# bornhack_stoplicht_ws2812_smd_405_cap_r1.net
KiCad netlist of a schematic drawn in EAGLE
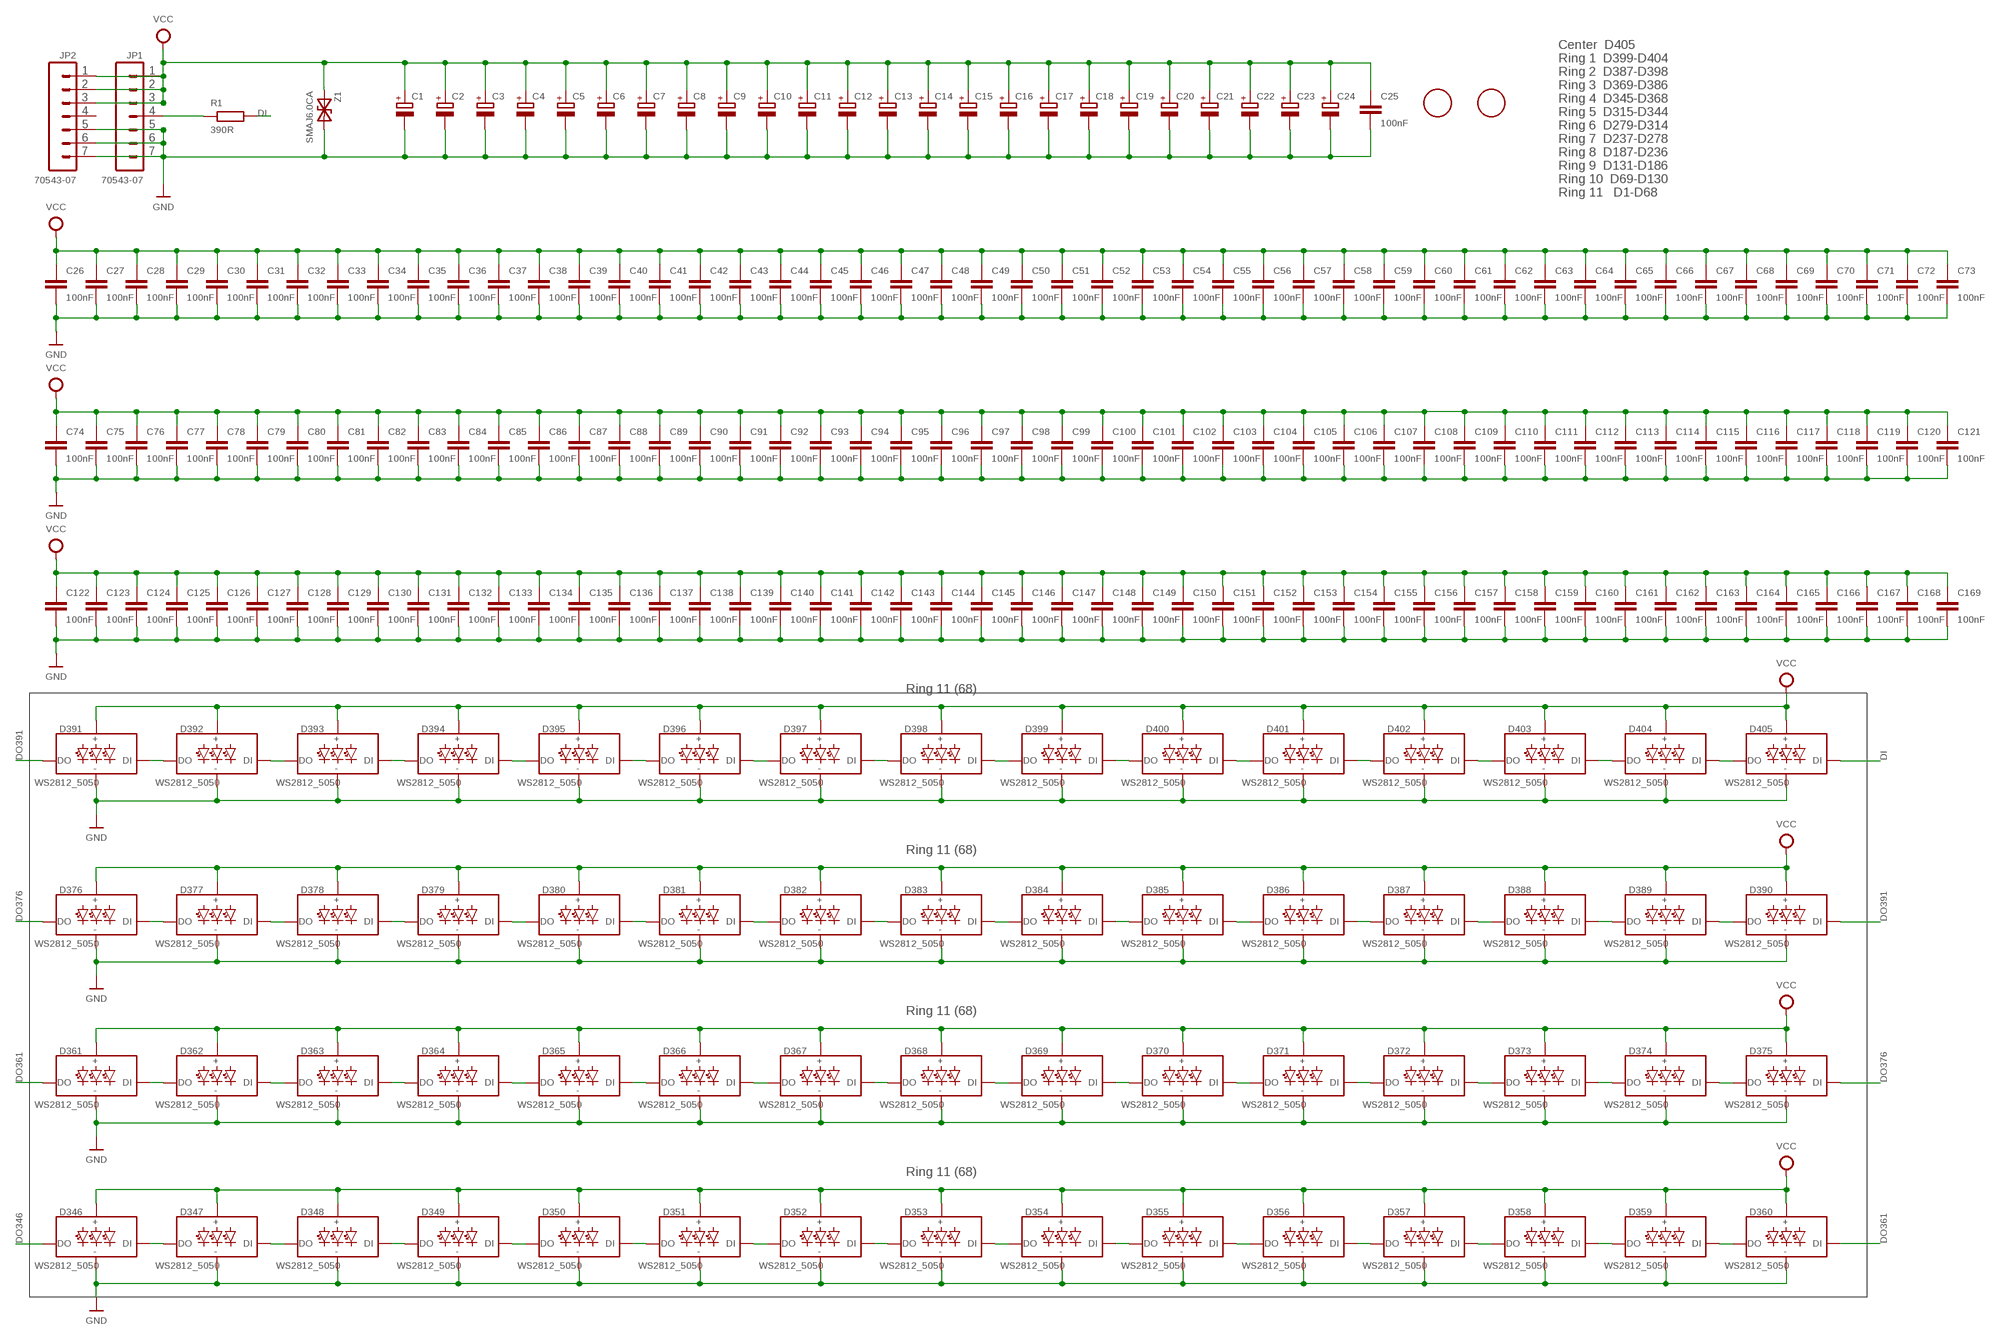
[diagram p0: schematic, sheet 1]
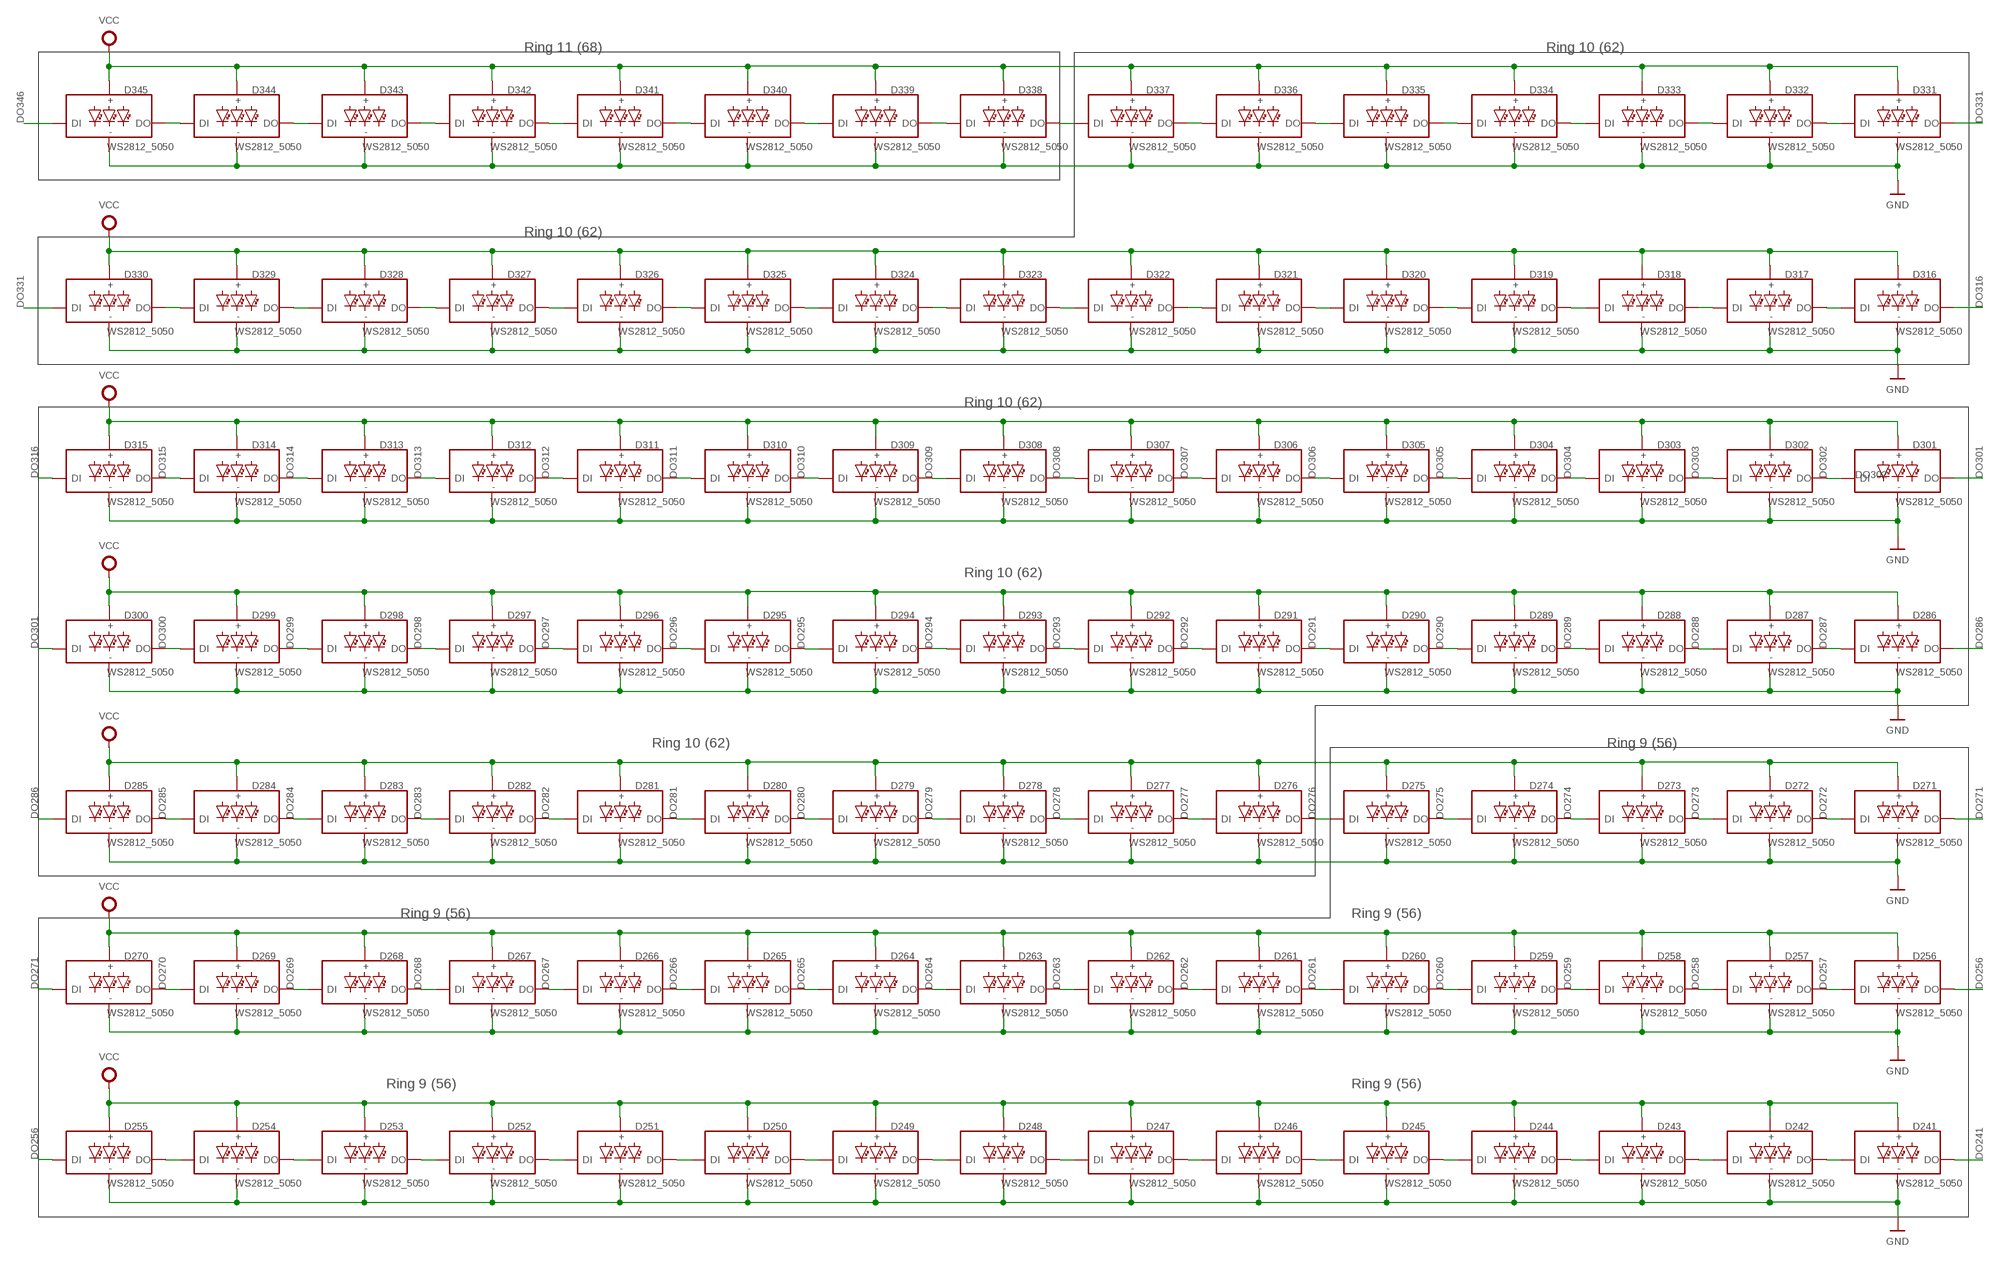
[diagram p1: schematic, sheet 2]
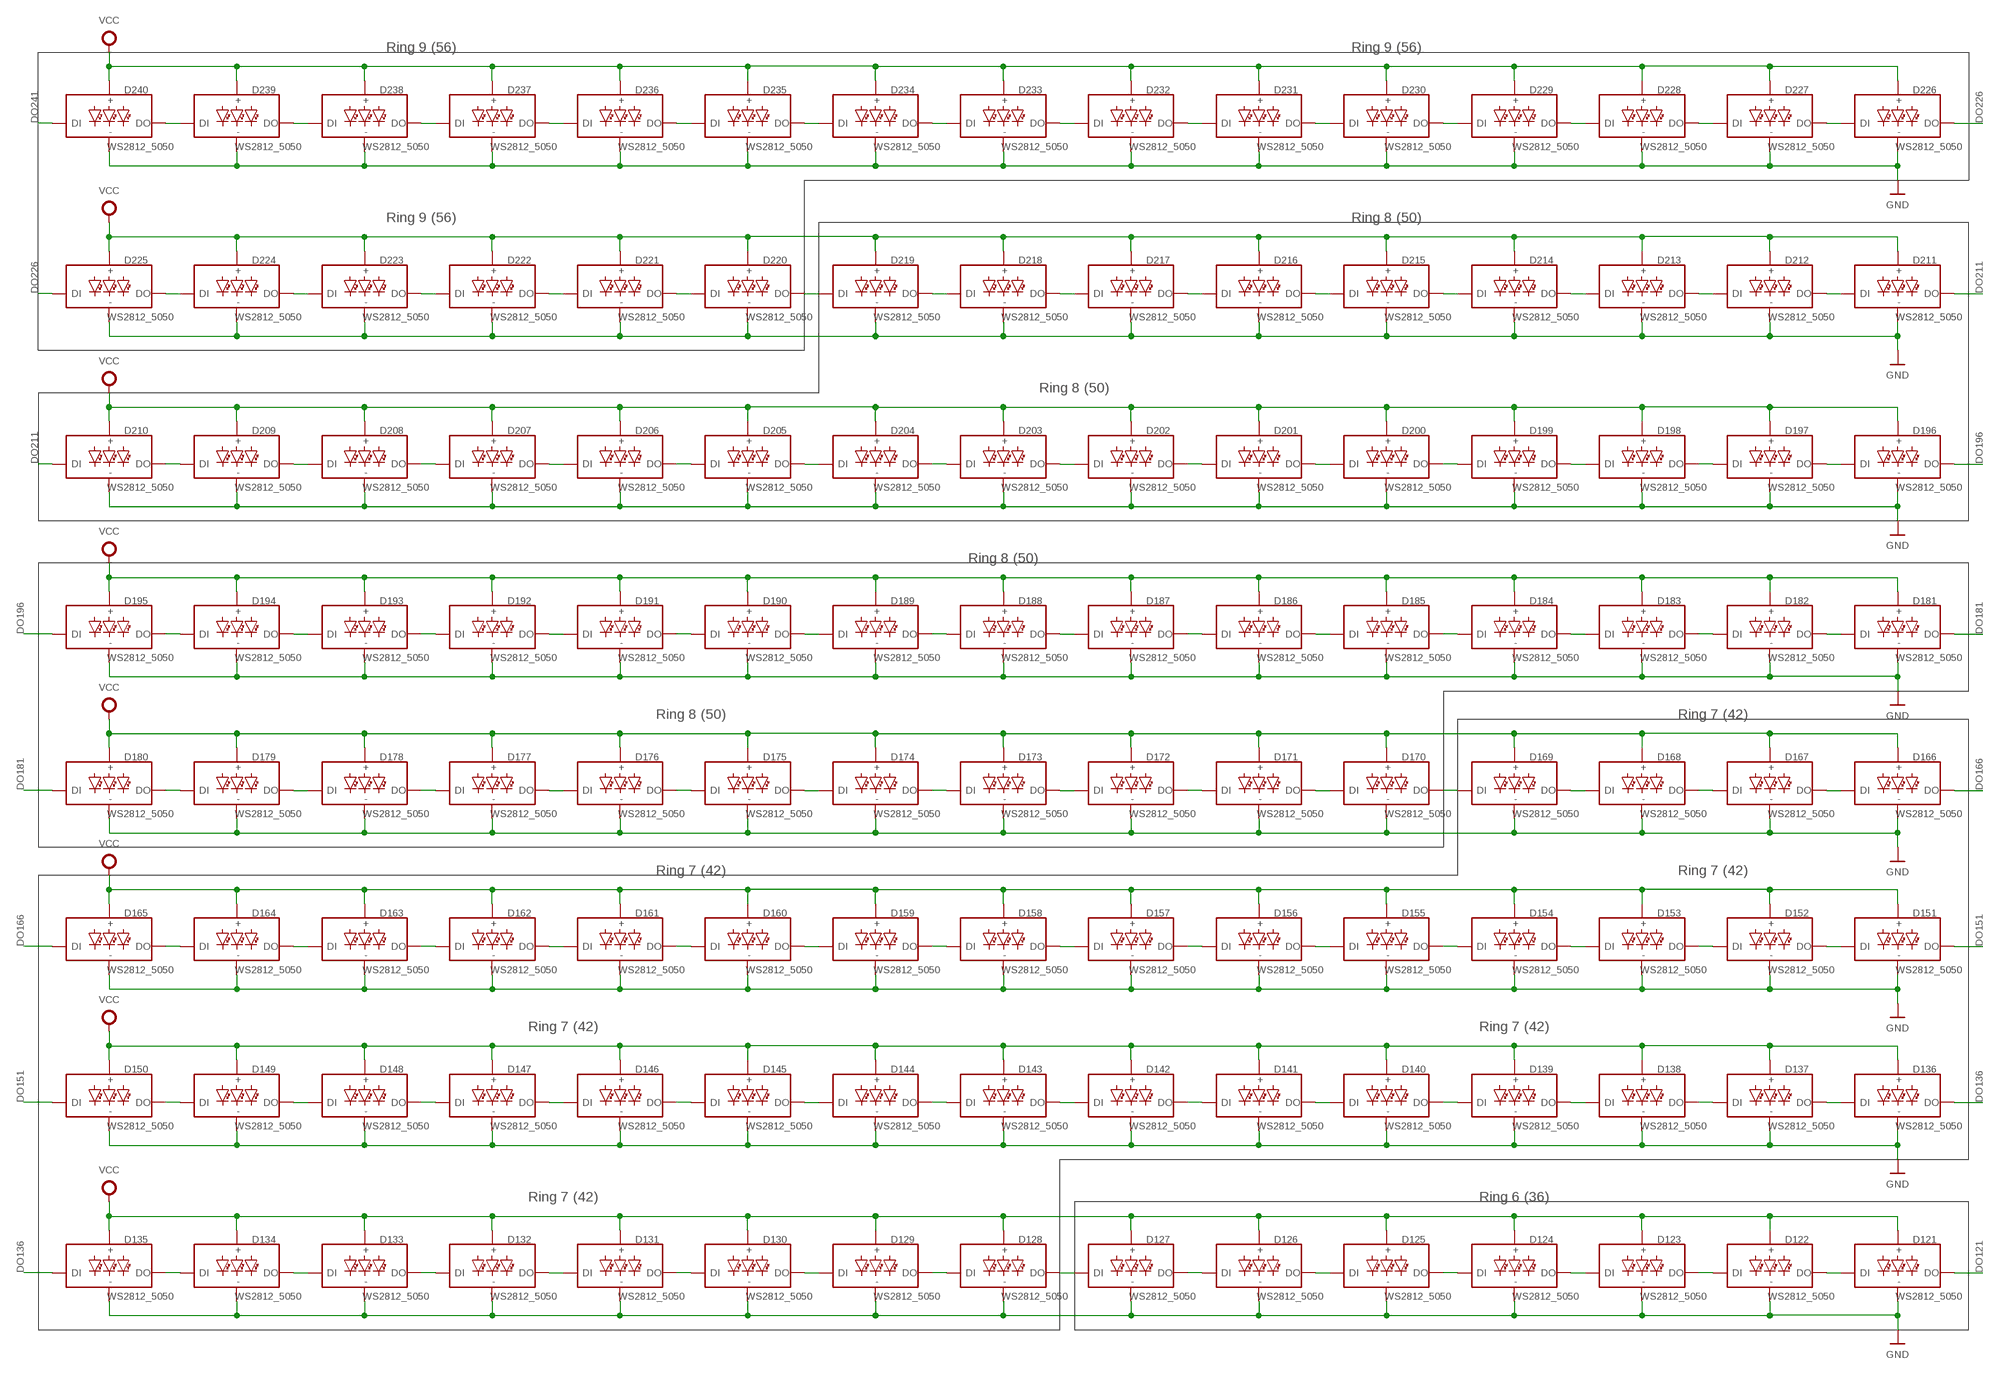
[diagram p2: schematic, sheet 3]
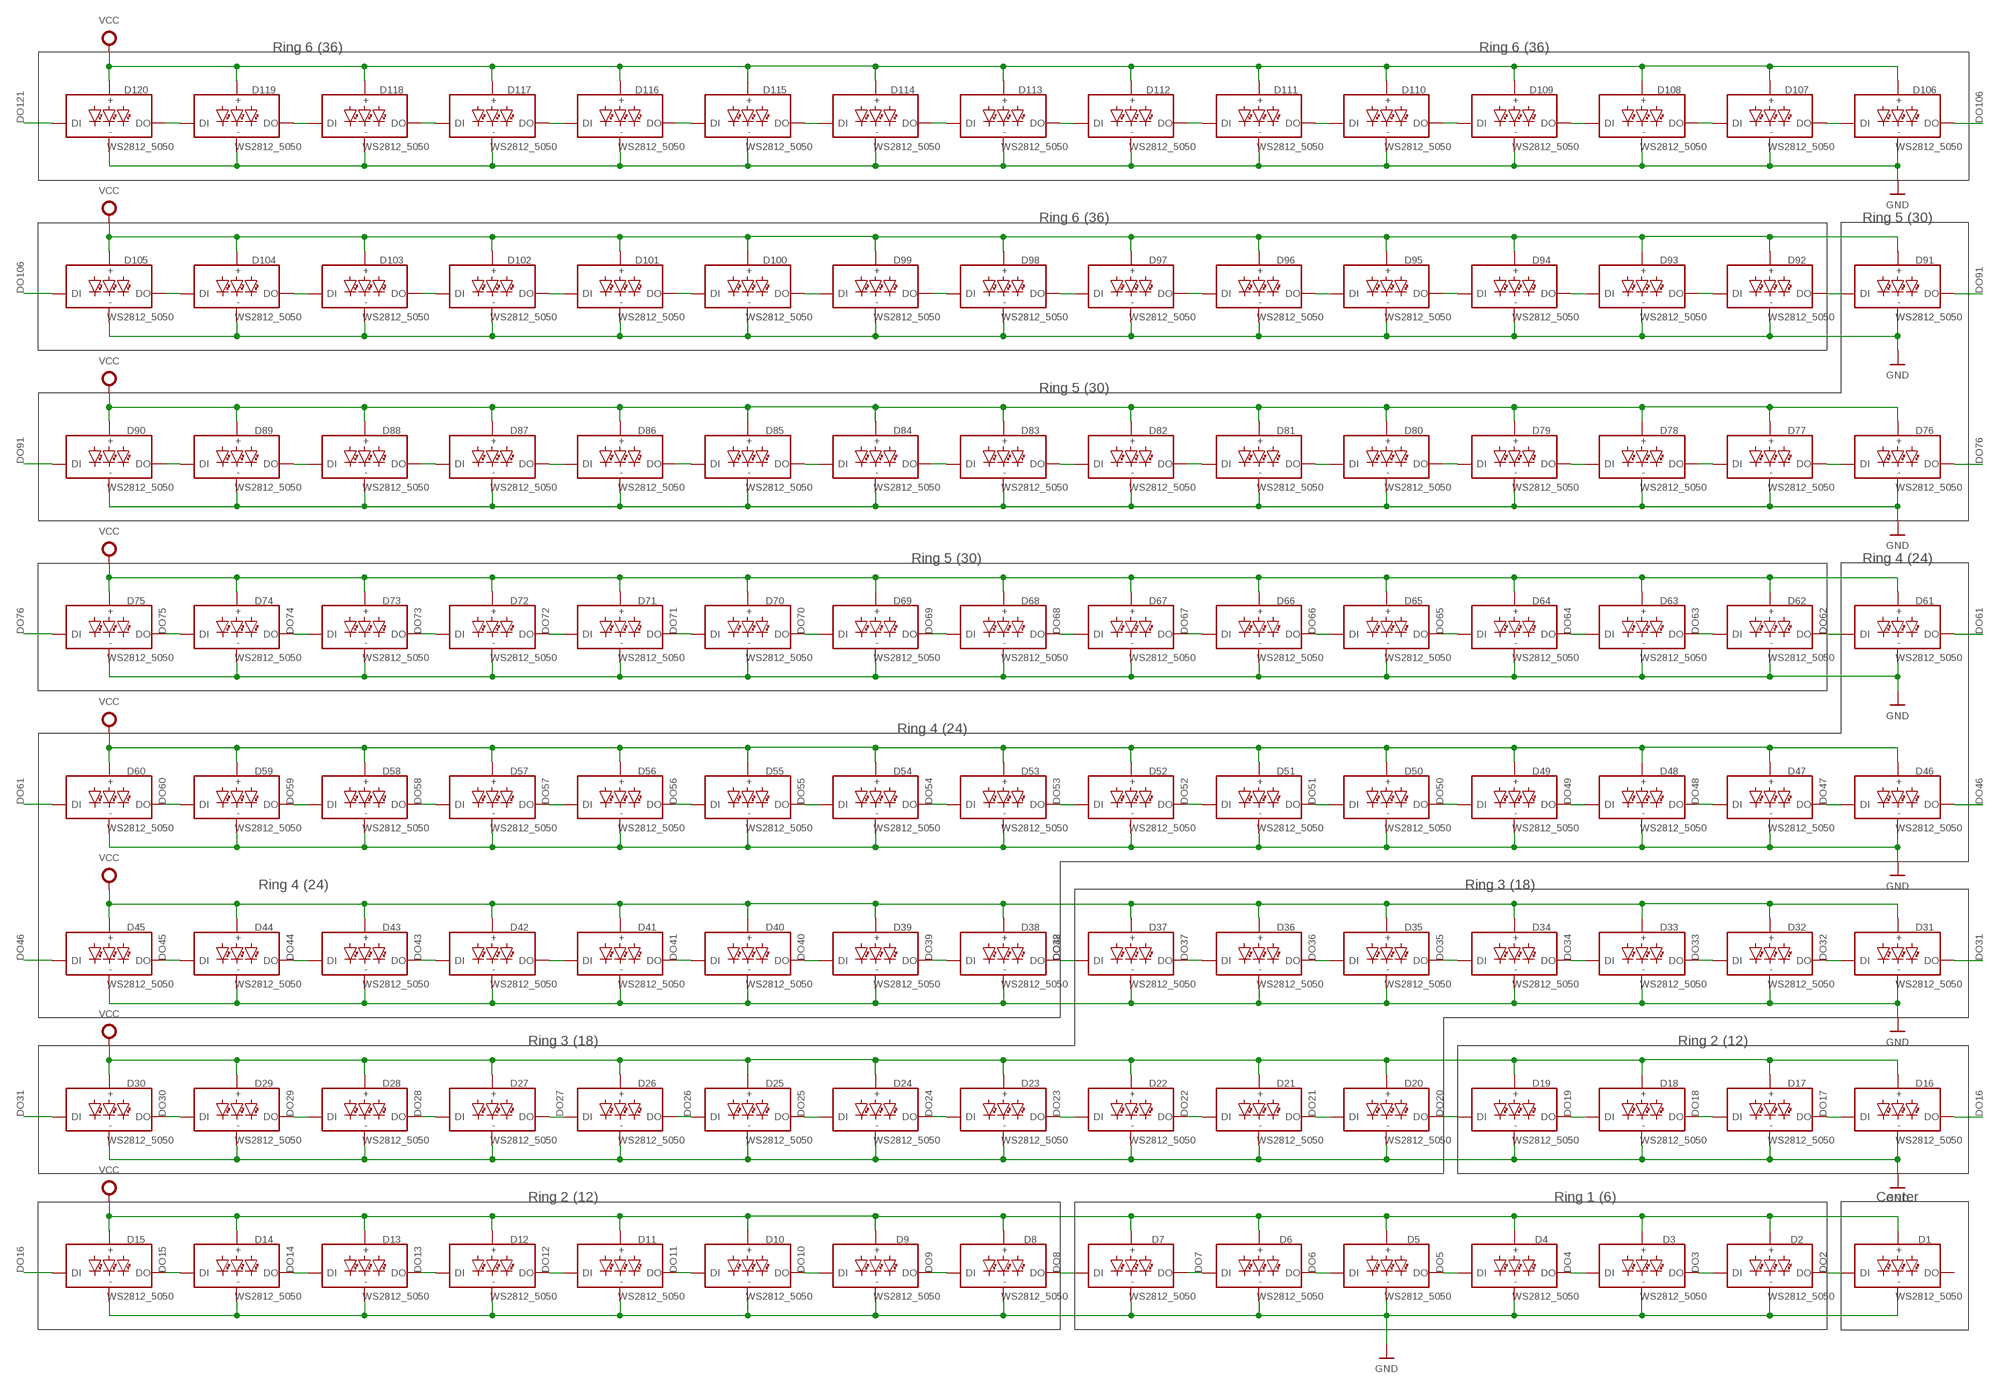
[diagram p3: schematic, sheet 4]

(export (version "E")
  (design (tool "Eeschema 10.0.6"))
  (components
    (comp (ref "D121")
      (value "WS2812_5050")
      (footprint "eagle-import:WS2812-5X5-4PIN")
      (libsource (lib "eagle-import") (part "led-rs_WS2812_5050"))
    )
    (comp (ref "D122")
      (value "WS2812_5050")
      (footprint "eagle-import:WS2812-5X5-4PIN")
      (libsource (lib "eagle-import") (part "led-rs_WS2812_5050"))
    )
    (comp (ref "D123")
      (value "WS2812_5050")
      (footprint "eagle-import:WS2812-5X5-4PIN")
      (libsource (lib "eagle-import") (part "led-rs_WS2812_5050"))
    )
    (comp (ref "D124")
      (value "WS2812_5050")
      (footprint "eagle-import:WS2812-5X5-4PIN")
      (libsource (lib "eagle-import") (part "led-rs_WS2812_5050"))
    )
    (comp (ref "D125")
      (value "WS2812_5050")
      (footprint "eagle-import:WS2812-5X5-4PIN")
      (libsource (lib "eagle-import") (part "led-rs_WS2812_5050"))
    )
    (comp (ref "D126")
      (value "WS2812_5050")
      (footprint "eagle-import:WS2812-5X5-4PIN")
      (libsource (lib "eagle-import") (part "led-rs_WS2812_5050"))
    )
    (comp (ref "D127")
      (value "WS2812_5050")
      (footprint "eagle-import:WS2812-5X5-4PIN")
      (libsource (lib "eagle-import") (part "led-rs_WS2812_5050"))
    )
    (comp (ref "D128")
      (value "WS2812_5050")
      (footprint "eagle-import:WS2812-5X5-4PIN")
      (libsource (lib "eagle-import") (part "led-rs_WS2812_5050"))
    )
    (comp (ref "D129")
      (value "WS2812_5050")
      (footprint "eagle-import:WS2812-5X5-4PIN")
      (libsource (lib "eagle-import") (part "led-rs_WS2812_5050"))
    )
    (comp (ref "D130")
      (value "WS2812_5050")
      (footprint "eagle-import:WS2812-5X5-4PIN")
      (libsource (lib "eagle-import") (part "led-rs_WS2812_5050"))
    )
    (comp (ref "D131")
      (value "WS2812_5050")
      (footprint "eagle-import:WS2812-5X5-4PIN")
      (libsource (lib "eagle-import") (part "led-rs_WS2812_5050"))
    )
    (comp (ref "D132")
      (value "WS2812_5050")
      (footprint "eagle-import:WS2812-5X5-4PIN")
      (libsource (lib "eagle-import") (part "led-rs_WS2812_5050"))
    )
    (comp (ref "D133")
      (value "WS2812_5050")
      (footprint "eagle-import:WS2812-5X5-4PIN")
      (libsource (lib "eagle-import") (part "led-rs_WS2812_5050"))
    )
    (comp (ref "D134")
      (value "WS2812_5050")
      (footprint "eagle-import:WS2812-5X5-4PIN")
      (libsource (lib "eagle-import") (part "led-rs_WS2812_5050"))
    )
    (comp (ref "D135")
      (value "WS2812_5050")
      (footprint "eagle-import:WS2812-5X5-4PIN")
      (libsource (lib "eagle-import") (part "led-rs_WS2812_5050"))
    )
    (comp (ref "D136")
      (value "WS2812_5050")
      (footprint "eagle-import:WS2812-5X5-4PIN")
      (libsource (lib "eagle-import") (part "led-rs_WS2812_5050"))
    )
    (comp (ref "D137")
      (value "WS2812_5050")
      (footprint "eagle-import:WS2812-5X5-4PIN")
      (libsource (lib "eagle-import") (part "led-rs_WS2812_5050"))
    )
    (comp (ref "D138")
      (value "WS2812_5050")
      (footprint "eagle-import:WS2812-5X5-4PIN")
      (libsource (lib "eagle-import") (part "led-rs_WS2812_5050"))
    )
    (comp (ref "D139")
      (value "WS2812_5050")
      (footprint "eagle-import:WS2812-5X5-4PIN")
      (libsource (lib "eagle-import") (part "led-rs_WS2812_5050"))
    )
    (comp (ref "D140")
      (value "WS2812_5050")
      (footprint "eagle-import:WS2812-5X5-4PIN")
      (libsource (lib "eagle-import") (part "led-rs_WS2812_5050"))
    )
    (comp (ref "D141")
      (value "WS2812_5050")
      (footprint "eagle-import:WS2812-5X5-4PIN")
      (libsource (lib "eagle-import") (part "led-rs_WS2812_5050"))
    )
    (comp (ref "D142")
      (value "WS2812_5050")
      (footprint "eagle-import:WS2812-5X5-4PIN")
      (libsource (lib "eagle-import") (part "led-rs_WS2812_5050"))
    )
    (comp (ref "D143")
      (value "WS2812_5050")
      (footprint "eagle-import:WS2812-5X5-4PIN")
      (libsource (lib "eagle-import") (part "led-rs_WS2812_5050"))
    )
    (comp (ref "D144")
      (value "WS2812_5050")
      (footprint "eagle-import:WS2812-5X5-4PIN")
      (libsource (lib "eagle-import") (part "led-rs_WS2812_5050"))
    )
    (comp (ref "D145")
      (value "WS2812_5050")
      (footprint "eagle-import:WS2812-5X5-4PIN")
      (libsource (lib "eagle-import") (part "led-rs_WS2812_5050"))
    )
    (comp (ref "D146")
      (value "WS2812_5050")
      (footprint "eagle-import:WS2812-5X5-4PIN")
      (libsource (lib "eagle-import") (part "led-rs_WS2812_5050"))
    )
    (comp (ref "D147")
      (value "WS2812_5050")
      (footprint "eagle-import:WS2812-5X5-4PIN")
      (libsource (lib "eagle-import") (part "led-rs_WS2812_5050"))
    )
    (comp (ref "D148")
      (value "WS2812_5050")
      (footprint "eagle-import:WS2812-5X5-4PIN")
      (libsource (lib "eagle-import") (part "led-rs_WS2812_5050"))
    )
    (comp (ref "D149")
      (value "WS2812_5050")
      (footprint "eagle-import:WS2812-5X5-4PIN")
      (libsource (lib "eagle-import") (part "led-rs_WS2812_5050"))
    )
    (comp (ref "D150")
      (value "WS2812_5050")
      (footprint "eagle-import:WS2812-5X5-4PIN")
      (libsource (lib "eagle-import") (part "led-rs_WS2812_5050"))
    )
    (comp (ref "D151")
      (value "WS2812_5050")
      (footprint "eagle-import:WS2812-5X5-4PIN")
      (libsource (lib "eagle-import") (part "led-rs_WS2812_5050"))
    )
    (comp (ref "D152")
      (value "WS2812_5050")
      (footprint "eagle-import:WS2812-5X5-4PIN")
      (libsource (lib "eagle-import") (part "led-rs_WS2812_5050"))
    )
    (comp (ref "D153")
      (value "WS2812_5050")
      (footprint "eagle-import:WS2812-5X5-4PIN")
      (libsource (lib "eagle-import") (part "led-rs_WS2812_5050"))
    )
    (comp (ref "D154")
      (value "WS2812_5050")
      (footprint "eagle-import:WS2812-5X5-4PIN")
      (libsource (lib "eagle-import") (part "led-rs_WS2812_5050"))
    )
    (comp (ref "D155")
      (value "WS2812_5050")
      (footprint "eagle-import:WS2812-5X5-4PIN")
      (libsource (lib "eagle-import") (part "led-rs_WS2812_5050"))
    )
    (comp (ref "D156")
      (value "WS2812_5050")
      (footprint "eagle-import:WS2812-5X5-4PIN")
      (libsource (lib "eagle-import") (part "led-rs_WS2812_5050"))
    )
    (comp (ref "D157")
      (value "WS2812_5050")
      (footprint "eagle-import:WS2812-5X5-4PIN")
      (libsource (lib "eagle-import") (part "led-rs_WS2812_5050"))
    )
    (comp (ref "D158")
      (value "WS2812_5050")
      (footprint "eagle-import:WS2812-5X5-4PIN")
      (libsource (lib "eagle-import") (part "led-rs_WS2812_5050"))
    )
    (comp (ref "D159")
      (value "WS2812_5050")
      (footprint "eagle-import:WS2812-5X5-4PIN")
      (libsource (lib "eagle-import") (part "led-rs_WS2812_5050"))
    )
    (comp (ref "D160")
      (value "WS2812_5050")
      (footprint "eagle-import:WS2812-5X5-4PIN")
      (libsource (lib "eagle-import") (part "led-rs_WS2812_5050"))
    )
    (comp (ref "D161")
      (value "WS2812_5050")
      (footprint "eagle-import:WS2812-5X5-4PIN")
      (libsource (lib "eagle-import") (part "led-rs_WS2812_5050"))
    )
    (comp (ref "D162")
      (value "WS2812_5050")
      (footprint "eagle-import:WS2812-5X5-4PIN")
      (libsource (lib "eagle-import") (part "led-rs_WS2812_5050"))
    )
    (comp (ref "D163")
      (value "WS2812_5050")
      (footprint "eagle-import:WS2812-5X5-4PIN")
      (libsource (lib "eagle-import") (part "led-rs_WS2812_5050"))
    )
    (comp (ref "D164")
      (value "WS2812_5050")
      (footprint "eagle-import:WS2812-5X5-4PIN")
      (libsource (lib "eagle-import") (part "led-rs_WS2812_5050"))
    )
    (comp (ref "D165")
      (value "WS2812_5050")
      (footprint "eagle-import:WS2812-5X5-4PIN")
      (libsource (lib "eagle-import") (part "led-rs_WS2812_5050"))
    )
    (comp (ref "D166")
      (value "WS2812_5050")
      (footprint "eagle-import:WS2812-5X5-4PIN")
      (libsource (lib "eagle-import") (part "led-rs_WS2812_5050"))
    )
    (comp (ref "D167")
      (value "WS2812_5050")
      (footprint "eagle-import:WS2812-5X5-4PIN")
      (libsource (lib "eagle-import") (part "led-rs_WS2812_5050"))
    )
    (comp (ref "D168")
      (value "WS2812_5050")
      (footprint "eagle-import:WS2812-5X5-4PIN")
      (libsource (lib "eagle-import") (part "led-rs_WS2812_5050"))
    )
    (comp (ref "D169")
      (value "WS2812_5050")
      (footprint "eagle-import:WS2812-5X5-4PIN")
      (libsource (lib "eagle-import") (part "led-rs_WS2812_5050"))
    )
    (comp (ref "D170")
      (value "WS2812_5050")
      (footprint "eagle-import:WS2812-5X5-4PIN")
      (libsource (lib "eagle-import") (part "led-rs_WS2812_5050"))
    )
    (comp (ref "D171")
      (value "WS2812_5050")
      (footprint "eagle-import:WS2812-5X5-4PIN")
      (libsource (lib "eagle-import") (part "led-rs_WS2812_5050"))
    )
    (comp (ref "D172")
      (value "WS2812_5050")
      (footprint "eagle-import:WS2812-5X5-4PIN")
      (libsource (lib "eagle-import") (part "led-rs_WS2812_5050"))
    )
    (comp (ref "D173")
      (value "WS2812_5050")
      (footprint "eagle-import:WS2812-5X5-4PIN")
      (libsource (lib "eagle-import") (part "led-rs_WS2812_5050"))
    )
    (comp (ref "D174")
      (value "WS2812_5050")
      (footprint "eagle-import:WS2812-5X5-4PIN")
      (libsource (lib "eagle-import") (part "led-rs_WS2812_5050"))
    )
    (comp (ref "D175")
      (value "WS2812_5050")
      (footprint "eagle-import:WS2812-5X5-4PIN")
      (libsource (lib "eagle-import") (part "led-rs_WS2812_5050"))
    )
    (comp (ref "D176")
      (value "WS2812_5050")
      (footprint "eagle-import:WS2812-5X5-4PIN")
      (libsource (lib "eagle-import") (part "led-rs_WS2812_5050"))
    )
    (comp (ref "D177")
      (value "WS2812_5050")
      (footprint "eagle-import:WS2812-5X5-4PIN")
      (libsource (lib "eagle-import") (part "led-rs_WS2812_5050"))
    )
    (comp (ref "D178")
      (value "WS2812_5050")
      (footprint "eagle-import:WS2812-5X5-4PIN")
      (libsource (lib "eagle-import") (part "led-rs_WS2812_5050"))
    )
    (comp (ref "D179")
      (value "WS2812_5050")
      (footprint "eagle-import:WS2812-5X5-4PIN")
      (libsource (lib "eagle-import") (part "led-rs_WS2812_5050"))
    )
    (comp (ref "D180")
      (value "WS2812_5050")
      (footprint "eagle-import:WS2812-5X5-4PIN")
      (libsource (lib "eagle-import") (part "led-rs_WS2812_5050"))
    )
    (comp (ref "D181")
      (value "WS2812_5050")
      (footprint "eagle-import:WS2812-5X5-4PIN")
      (libsource (lib "eagle-import") (part "led-rs_WS2812_5050"))
    )
    (comp (ref "D182")
      (value "WS2812_5050")
      (footprint "eagle-import:WS2812-5X5-4PIN")
      (libsource (lib "eagle-import") (part "led-rs_WS2812_5050"))
    )
    (comp (ref "D183")
      (value "WS2812_5050")
      (footprint "eagle-import:WS2812-5X5-4PIN")
      (libsource (lib "eagle-import") (part "led-rs_WS2812_5050"))
    )
    (comp (ref "D184")
      (value "WS2812_5050")
      (footprint "eagle-import:WS2812-5X5-4PIN")
      (libsource (lib "eagle-import") (part "led-rs_WS2812_5050"))
    )
    (comp (ref "D185")
      (value "WS2812_5050")
      (footprint "eagle-import:WS2812-5X5-4PIN")
      (libsource (lib "eagle-import") (part "led-rs_WS2812_5050"))
    )
    (comp (ref "D186")
      (value "WS2812_5050")
      (footprint "eagle-import:WS2812-5X5-4PIN")
      (libsource (lib "eagle-import") (part "led-rs_WS2812_5050"))
    )
    (comp (ref "D187")
      (value "WS2812_5050")
      (footprint "eagle-import:WS2812-5X5-4PIN")
      (libsource (lib "eagle-import") (part "led-rs_WS2812_5050"))
    )
    (comp (ref "D188")
      (value "WS2812_5050")
      (footprint "eagle-import:WS2812-5X5-4PIN")
      (libsource (lib "eagle-import") (part "led-rs_WS2812_5050"))
    )
    (comp (ref "D189")
      (value "WS2812_5050")
      (footprint "eagle-import:WS2812-5X5-4PIN")
      (libsource (lib "eagle-import") (part "led-rs_WS2812_5050"))
    )
    (comp (ref "D190")
      (value "WS2812_5050")
      (footprint "eagle-import:WS2812-5X5-4PIN")
      (libsource (lib "eagle-import") (part "led-rs_WS2812_5050"))
    )
    (comp (ref "D191")
      (value "WS2812_5050")
      (footprint "eagle-import:WS2812-5X5-4PIN")
      (libsource (lib "eagle-import") (part "led-rs_WS2812_5050"))
    )
    (comp (ref "D192")
      (value "WS2812_5050")
      (footprint "eagle-import:WS2812-5X5-4PIN")
      (libsource (lib "eagle-import") (part "led-rs_WS2812_5050"))
    )
    (comp (ref "D193")
      (value "WS2812_5050")
      (footprint "eagle-import:WS2812-5X5-4PIN")
      (libsource (lib "eagle-import") (part "led-rs_WS2812_5050"))
    )
    (comp (ref "D194")
      (value "WS2812_5050")
      (footprint "eagle-import:WS2812-5X5-4PIN")
      (libsource (lib "eagle-import") (part "led-rs_WS2812_5050"))
    )
    (comp (ref "D195")
      (value "WS2812_5050")
      (footprint "eagle-import:WS2812-5X5-4PIN")
      (libsource (lib "eagle-import") (part "led-rs_WS2812_5050"))
    )
    (comp (ref "D196")
      (value "WS2812_5050")
      (footprint "eagle-import:WS2812-5X5-4PIN")
      (libsource (lib "eagle-import") (part "led-rs_WS2812_5050"))
    )
    (comp (ref "D197")
      (value "WS2812_5050")
      (footprint "eagle-import:WS2812-5X5-4PIN")
      (libsource (lib "eagle-import") (part "led-rs_WS2812_5050"))
    )
    (comp (ref "D198")
      (value "WS2812_5050")
      (footprint "eagle-import:WS2812-5X5-4PIN")
      (libsource (lib "eagle-import") (part "led-rs_WS2812_5050"))
    )
    (comp (ref "D199")
      (value "WS2812_5050")
      (footprint "eagle-import:WS2812-5X5-4PIN")
      (libsource (lib "eagle-import") (part "led-rs_WS2812_5050"))
    )
    (comp (ref "D200")
      (value "WS2812_5050")
      (footprint "eagle-import:WS2812-5X5-4PIN")
      (libsource (lib "eagle-import") (part "led-rs_WS2812_5050"))
    )
    (comp (ref "D201")
      (value "WS2812_5050")
      (footprint "eagle-import:WS2812-5X5-4PIN")
      (libsource (lib "eagle-import") (part "led-rs_WS2812_5050"))
    )
    (comp (ref "D202")
      (value "WS2812_5050")
      (footprint "eagle-import:WS2812-5X5-4PIN")
      (libsource (lib "eagle-import") (part "led-rs_WS2812_5050"))
    )
    (comp (ref "D203")
      (value "WS2812_5050")
      (footprint "eagle-import:WS2812-5X5-4PIN")
      (libsource (lib "eagle-import") (part "led-rs_WS2812_5050"))
    )
    (comp (ref "D204")
      (value "WS2812_5050")
      (footprint "eagle-import:WS2812-5X5-4PIN")
      (libsource (lib "eagle-import") (part "led-rs_WS2812_5050"))
    )
    (comp (ref "D205")
      (value "WS2812_5050")
      (footprint "eagle-import:WS2812-5X5-4PIN")
      (libsource (lib "eagle-import") (part "led-rs_WS2812_5050"))
    )
    (comp (ref "D206")
      (value "WS2812_5050")
      (footprint "eagle-import:WS2812-5X5-4PIN")
      (libsource (lib "eagle-import") (part "led-rs_WS2812_5050"))
    )
    (comp (ref "D207")
      (value "WS2812_5050")
      (footprint "eagle-import:WS2812-5X5-4PIN")
      (libsource (lib "eagle-import") (part "led-rs_WS2812_5050"))
    )
    (comp (ref "D208")
      (value "WS2812_5050")
      (footprint "eagle-import:WS2812-5X5-4PIN")
      (libsource (lib "eagle-import") (part "led-rs_WS2812_5050"))
    )
    (comp (ref "D209")
      (value "WS2812_5050")
      (footprint "eagle-import:WS2812-5X5-4PIN")
      (libsource (lib "eagle-import") (part "led-rs_WS2812_5050"))
    )
    (comp (ref "D210")
      (value "WS2812_5050")
      (footprint "eagle-import:WS2812-5X5-4PIN")
      (libsource (lib "eagle-import") (part "led-rs_WS2812_5050"))
    )
    (comp (ref "D211")
      (value "WS2812_5050")
      (footprint "eagle-import:WS2812-5X5-4PIN")
      (libsource (lib "eagle-import") (part "led-rs_WS2812_5050"))
    )
    (comp (ref "D212")
      (value "WS2812_5050")
      (footprint "eagle-import:WS2812-5X5-4PIN")
      (libsource (lib "eagle-import") (part "led-rs_WS2812_5050"))
    )
    (comp (ref "D213")
      (value "WS2812_5050")
      (footprint "eagle-import:WS2812-5X5-4PIN")
      (libsource (lib "eagle-import") (part "led-rs_WS2812_5050"))
    )
    (comp (ref "D214")
      (value "WS2812_5050")
      (footprint "eagle-import:WS2812-5X5-4PIN")
      (libsource (lib "eagle-import") (part "led-rs_WS2812_5050"))
    )
    (comp (ref "D215")
      (value "WS2812_5050")
      (footprint "eagle-import:WS2812-5X5-4PIN")
      (libsource (lib "eagle-import") (part "led-rs_WS2812_5050"))
    )
    (comp (ref "D216")
      (value "WS2812_5050")
      (footprint "eagle-import:WS2812-5X5-4PIN")
      (libsource (lib "eagle-import") (part "led-rs_WS2812_5050"))
    )
    (comp (ref "D217")
      (value "WS2812_5050")
      (footprint "eagle-import:WS2812-5X5-4PIN")
      (libsource (lib "eagle-import") (part "led-rs_WS2812_5050"))
    )
    (comp (ref "D218")
      (value "WS2812_5050")
      (footprint "eagle-import:WS2812-5X5-4PIN")
      (libsource (lib "eagle-import") (part "led-rs_WS2812_5050"))
    )
    (comp (ref "D219")
      (value "WS2812_5050")
      (footprint "eagle-import:WS2812-5X5-4PIN")
      (libsource (lib "eagle-import") (part "led-rs_WS2812_5050"))
    )
    (comp (ref "D220")
      (value "WS2812_5050")
      (footprint "eagle-import:WS2812-5X5-4PIN")
      (libsource (lib "eagle-import") (part "led-rs_WS2812_5050"))
    )
    (comp (ref "D221")
      (value "WS2812_5050")
      (footprint "eagle-import:WS2812-5X5-4PIN")
      (libsource (lib "eagle-import") (part "led-rs_WS2812_5050"))
    )
    (comp (ref "D222")
      (value "WS2812_5050")
      (footprint "eagle-import:WS2812-5X5-4PIN")
      (libsource (lib "eagle-import") (part "led-rs_WS2812_5050"))
    )
    (comp (ref "D223")
      (value "WS2812_5050")
      (footprint "eagle-import:WS2812-5X5-4PIN")
      (libsource (lib "eagle-import") (part "led-rs_WS2812_5050"))
    )
    (comp (ref "D224")
      (value "WS2812_5050")
      (footprint "eagle-import:WS2812-5X5-4PIN")
      (libsource (lib "eagle-import") (part "led-rs_WS2812_5050"))
    )
    (comp (ref "D225")
      (value "WS2812_5050")
      (footprint "eagle-import:WS2812-5X5-4PIN")
      (libsource (lib "eagle-import") (part "led-rs_WS2812_5050"))
    )
    (comp (ref "D226")
      (value "WS2812_5050")
      (footprint "eagle-import:WS2812-5X5-4PIN")
      (libsource (lib "eagle-import") (part "led-rs_WS2812_5050"))
    )
    (comp (ref "D227")
      (value "WS2812_5050")
      (footprint "eagle-import:WS2812-5X5-4PIN")
      (libsource (lib "eagle-import") (part "led-rs_WS2812_5050"))
    )
    (comp (ref "D228")
      (value "WS2812_5050")
      (footprint "eagle-import:WS2812-5X5-4PIN")
      (libsource (lib "eagle-import") (part "led-rs_WS2812_5050"))
    )
    (comp (ref "D229")
      (value "WS2812_5050")
      (footprint "eagle-import:WS2812-5X5-4PIN")
      (libsource (lib "eagle-import") (part "led-rs_WS2812_5050"))
    )
    (comp (ref "D230")
      (value "WS2812_5050")
      (footprint "eagle-import:WS2812-5X5-4PIN")
      (libsource (lib "eagle-import") (part "led-rs_WS2812_5050"))
    )
    (comp (ref "D231")
      (value "WS2812_5050")
      (footprint "eagle-import:WS2812-5X5-4PIN")
      (libsource (lib "eagle-import") (part "led-rs_WS2812_5050"))
    )
    (comp (ref "D232")
      (value "WS2812_5050")
      (footprint "eagle-import:WS2812-5X5-4PIN")
      (libsource (lib "eagle-import") (part "led-rs_WS2812_5050"))
    )
    (comp (ref "D233")
      (value "WS2812_5050")
      (footprint "eagle-import:WS2812-5X5-4PIN")
      (libsource (lib "eagle-import") (part "led-rs_WS2812_5050"))
    )
    (comp (ref "D234")
      (value "WS2812_5050")
      (footprint "eagle-import:WS2812-5X5-4PIN")
      (libsource (lib "eagle-import") (part "led-rs_WS2812_5050"))
    )
    (comp (ref "D235")
      (value "WS2812_5050")
      (footprint "eagle-import:WS2812-5X5-4PIN")
      (libsource (lib "eagle-import") (part "led-rs_WS2812_5050"))
    )
    (comp (ref "D236")
      (value "WS2812_5050")
      (footprint "eagle-import:WS2812-5X5-4PIN")
      (libsource (lib "eagle-import") (part "led-rs_WS2812_5050"))
    )
    (comp (ref "D237")
      (value "WS2812_5050")
      (footprint "eagle-import:WS2812-5X5-4PIN")
      (libsource (lib "eagle-import") (part "led-rs_WS2812_5050"))
    )
    (comp (ref "D238")
      (value "WS2812_5050")
      (footprint "eagle-import:WS2812-5X5-4PIN")
      (libsource (lib "eagle-import") (part "led-rs_WS2812_5050"))
    )
    (comp (ref "D239")
      (value "WS2812_5050")
      (footprint "eagle-import:WS2812-5X5-4PIN")
      (libsource (lib "eagle-import") (part "led-rs_WS2812_5050"))
    )
    (comp (ref "D240")
      (value "WS2812_5050")
      (footprint "eagle-import:WS2812-5X5-4PIN")
      (libsource (lib "eagle-import") (part "led-rs_WS2812_5050"))
    )
    (comp (ref "D241")
      (value "WS2812_5050")
      (footprint "eagle-import:WS2812-5X5-4PIN")
      (libsource (lib "eagle-import") (part "led-rs_WS2812_5050"))
    )
    (comp (ref "D242")
      (value "WS2812_5050")
      (footprint "eagle-import:WS2812-5X5-4PIN")
      (libsource (lib "eagle-import") (part "led-rs_WS2812_5050"))
    )
    (comp (ref "D243")
      (value "WS2812_5050")
      (footprint "eagle-import:WS2812-5X5-4PIN")
      (libsource (lib "eagle-import") (part "led-rs_WS2812_5050"))
    )
    (comp (ref "D244")
      (value "WS2812_5050")
      (footprint "eagle-import:WS2812-5X5-4PIN")
      (libsource (lib "eagle-import") (part "led-rs_WS2812_5050"))
    )
    (comp (ref "D245")
      (value "WS2812_5050")
      (footprint "eagle-import:WS2812-5X5-4PIN")
      (libsource (lib "eagle-import") (part "led-rs_WS2812_5050"))
    )
    (comp (ref "D246")
      (value "WS2812_5050")
      (footprint "eagle-import:WS2812-5X5-4PIN")
      (libsource (lib "eagle-import") (part "led-rs_WS2812_5050"))
    )
    (comp (ref "D247")
      (value "WS2812_5050")
      (footprint "eagle-import:WS2812-5X5-4PIN")
      (libsource (lib "eagle-import") (part "led-rs_WS2812_5050"))
    )
    (comp (ref "D248")
      (value "WS2812_5050")
      (footprint "eagle-import:WS2812-5X5-4PIN")
      (libsource (lib "eagle-import") (part "led-rs_WS2812_5050"))
    )
    (comp (ref "D249")
      (value "WS2812_5050")
      (footprint "eagle-import:WS2812-5X5-4PIN")
      (libsource (lib "eagle-import") (part "led-rs_WS2812_5050"))
    )
    (comp (ref "D250")
      (value "WS2812_5050")
      (footprint "eagle-import:WS2812-5X5-4PIN")
      (libsource (lib "eagle-import") (part "led-rs_WS2812_5050"))
    )
    (comp (ref "D251")
      (value "WS2812_5050")
      (footprint "eagle-import:WS2812-5X5-4PIN")
      (libsource (lib "eagle-import") (part "led-rs_WS2812_5050"))
    )
    (comp (ref "D252")
      (value "WS2812_5050")
      (footprint "eagle-import:WS2812-5X5-4PIN")
      (libsource (lib "eagle-import") (part "led-rs_WS2812_5050"))
    )
    (comp (ref "D253")
      (value "WS2812_5050")
      (footprint "eagle-import:WS2812-5X5-4PIN")
      (libsource (lib "eagle-import") (part "led-rs_WS2812_5050"))
    )
    (comp (ref "D254")
      (value "WS2812_5050")
      (footprint "eagle-import:WS2812-5X5-4PIN")
      (libsource (lib "eagle-import") (part "led-rs_WS2812_5050"))
    )
    (comp (ref "D255")
      (value "WS2812_5050")
      (footprint "eagle-import:WS2812-5X5-4PIN")
      (libsource (lib "eagle-import") (part "led-rs_WS2812_5050"))
    )
    (comp (ref "D256")
      (value "WS2812_5050")
      (footprint "eagle-import:WS2812-5X5-4PIN")
      (libsource (lib "eagle-import") (part "led-rs_WS2812_5050"))
    )
    (comp (ref "D257")
      (value "WS2812_5050")
      (footprint "eagle-import:WS2812-5X5-4PIN")
      (libsource (lib "eagle-import") (part "led-rs_WS2812_5050"))
    )
    (comp (ref "D258")
      (value "WS2812_5050")
      (footprint "eagle-import:WS2812-5X5-4PIN")
      (libsource (lib "eagle-import") (part "led-rs_WS2812_5050"))
    )
    (comp (ref "D259")
      (value "WS2812_5050")
      (footprint "eagle-import:WS2812-5X5-4PIN")
      (libsource (lib "eagle-import") (part "led-rs_WS2812_5050"))
    )
    (comp (ref "D260")
      (value "WS2812_5050")
      (footprint "eagle-import:WS2812-5X5-4PIN")
      (libsource (lib "eagle-import") (part "led-rs_WS2812_5050"))
    )
    (comp (ref "D261")
      (value "WS2812_5050")
      (footprint "eagle-import:WS2812-5X5-4PIN")
      (libsource (lib "eagle-import") (part "led-rs_WS2812_5050"))
    )
    (comp (ref "D262")
      (value "WS2812_5050")
      (footprint "eagle-import:WS2812-5X5-4PIN")
      (libsource (lib "eagle-import") (part "led-rs_WS2812_5050"))
    )
    (comp (ref "D263")
      (value "WS2812_5050")
      (footprint "eagle-import:WS2812-5X5-4PIN")
      (libsource (lib "eagle-import") (part "led-rs_WS2812_5050"))
    )
    (comp (ref "D264")
      (value "WS2812_5050")
      (footprint "eagle-import:WS2812-5X5-4PIN")
      (libsource (lib "eagle-import") (part "led-rs_WS2812_5050"))
    )
    (comp (ref "D265")
      (value "WS2812_5050")
      (footprint "eagle-import:WS2812-5X5-4PIN")
      (libsource (lib "eagle-import") (part "led-rs_WS2812_5050"))
    )
    (comp (ref "D266")
      (value "WS2812_5050")
      (footprint "eagle-import:WS2812-5X5-4PIN")
      (libsource (lib "eagle-import") (part "led-rs_WS2812_5050"))
    )
    (comp (ref "D267")
      (value "WS2812_5050")
      (footprint "eagle-import:WS2812-5X5-4PIN")
      (libsource (lib "eagle-import") (part "led-rs_WS2812_5050"))
    )
    (comp (ref "D268")
      (value "WS2812_5050")
      (footprint "eagle-import:WS2812-5X5-4PIN")
      (libsource (lib "eagle-import") (part "led-rs_WS2812_5050"))
    )
    (comp (ref "D269")
      (value "WS2812_5050")
      (footprint "eagle-import:WS2812-5X5-4PIN")
      (libsource (lib "eagle-import") (part "led-rs_WS2812_5050"))
    )
    (comp (ref "D270")
      (value "WS2812_5050")
      (footprint "eagle-import:WS2812-5X5-4PIN")
      (libsource (lib "eagle-import") (part "led-rs_WS2812_5050"))
    )
    (comp (ref "D271")
      (value "WS2812_5050")
      (footprint "eagle-import:WS2812-5X5-4PIN")
      (libsource (lib "eagle-import") (part "led-rs_WS2812_5050"))
    )
    (comp (ref "D272")
      (value "WS2812_5050")
      (footprint "eagle-import:WS2812-5X5-4PIN")
      (libsource (lib "eagle-import") (part "led-rs_WS2812_5050"))
    )
    (comp (ref "D273")
      (value "WS2812_5050")
      (footprint "eagle-import:WS2812-5X5-4PIN")
      (libsource (lib "eagle-import") (part "led-rs_WS2812_5050"))
    )
    (comp (ref "D274")
      (value "WS2812_5050")
      (footprint "eagle-import:WS2812-5X5-4PIN")
      (libsource (lib "eagle-import") (part "led-rs_WS2812_5050"))
    )
    (comp (ref "D275")
      (value "WS2812_5050")
      (footprint "eagle-import:WS2812-5X5-4PIN")
      (libsource (lib "eagle-import") (part "led-rs_WS2812_5050"))
    )
    (comp (ref "D276")
      (value "WS2812_5050")
      (footprint "eagle-import:WS2812-5X5-4PIN")
      (libsource (lib "eagle-import") (part "led-rs_WS2812_5050"))
    )
    (comp (ref "D277")
      (value "WS2812_5050")
      (footprint "eagle-import:WS2812-5X5-4PIN")
      (libsource (lib "eagle-import") (part "led-rs_WS2812_5050"))
    )
    (comp (ref "D278")
      (value "WS2812_5050")
      (footprint "eagle-import:WS2812-5X5-4PIN")
      (libsource (lib "eagle-import") (part "led-rs_WS2812_5050"))
    )
    (comp (ref "D279")
      (value "WS2812_5050")
      (footprint "eagle-import:WS2812-5X5-4PIN")
      (libsource (lib "eagle-import") (part "led-rs_WS2812_5050"))
    )
    (comp (ref "D280")
      (value "WS2812_5050")
      (footprint "eagle-import:WS2812-5X5-4PIN")
      (libsource (lib "eagle-import") (part "led-rs_WS2812_5050"))
    )
    (comp (ref "D281")
      (value "WS2812_5050")
      (footprint "eagle-import:WS2812-5X5-4PIN")
      (libsource (lib "eagle-import") (part "led-rs_WS2812_5050"))
    )
    (comp (ref "D282")
      (value "WS2812_5050")
      (footprint "eagle-import:WS2812-5X5-4PIN")
      (libsource (lib "eagle-import") (part "led-rs_WS2812_5050"))
    )
    (comp (ref "D283")
      (value "WS2812_5050")
      (footprint "eagle-import:WS2812-5X5-4PIN")
      (libsource (lib "eagle-import") (part "led-rs_WS2812_5050"))
    )
    (comp (ref "D284")
      (value "WS2812_5050")
      (footprint "eagle-import:WS2812-5X5-4PIN")
      (libsource (lib "eagle-import") (part "led-rs_WS2812_5050"))
    )
    (comp (ref "D285")
      (value "WS2812_5050")
      (footprint "eagle-import:WS2812-5X5-4PIN")
      (libsource (lib "eagle-import") (part "led-rs_WS2812_5050"))
    )
    (comp (ref "D286")
      (value "WS2812_5050")
      (footprint "eagle-import:WS2812-5X5-4PIN")
      (libsource (lib "eagle-import") (part "led-rs_WS2812_5050"))
    )
    (comp (ref "D287")
      (value "WS2812_5050")
      (footprint "eagle-import:WS2812-5X5-4PIN")
      (libsource (lib "eagle-import") (part "led-rs_WS2812_5050"))
    )
    (comp (ref "D288")
      (value "WS2812_5050")
      (footprint "eagle-import:WS2812-5X5-4PIN")
      (libsource (lib "eagle-import") (part "led-rs_WS2812_5050"))
    )
    (comp (ref "D289")
      (value "WS2812_5050")
      (footprint "eagle-import:WS2812-5X5-4PIN")
      (libsource (lib "eagle-import") (part "led-rs_WS2812_5050"))
    )
    (comp (ref "D290")
      (value "WS2812_5050")
      (footprint "eagle-import:WS2812-5X5-4PIN")
      (libsource (lib "eagle-import") (part "led-rs_WS2812_5050"))
    )
    (comp (ref "D291")
      (value "WS2812_5050")
      (footprint "eagle-import:WS2812-5X5-4PIN")
      (libsource (lib "eagle-import") (part "led-rs_WS2812_5050"))
    )
    (comp (ref "D292")
      (value "WS2812_5050")
      (footprint "eagle-import:WS2812-5X5-4PIN")
      (libsource (lib "eagle-import") (part "led-rs_WS2812_5050"))
    )
    (comp (ref "D293")
      (value "WS2812_5050")
      (footprint "eagle-import:WS2812-5X5-4PIN")
      (libsource (lib "eagle-import") (part "led-rs_WS2812_5050"))
    )
    (comp (ref "D294")
      (value "WS2812_5050")
      (footprint "eagle-import:WS2812-5X5-4PIN")
      (libsource (lib "eagle-import") (part "led-rs_WS2812_5050"))
    )
    (comp (ref "D295")
      (value "WS2812_5050")
      (footprint "eagle-import:WS2812-5X5-4PIN")
      (libsource (lib "eagle-import") (part "led-rs_WS2812_5050"))
    )
    (comp (ref "D296")
      (value "WS2812_5050")
      (footprint "eagle-import:WS2812-5X5-4PIN")
      (libsource (lib "eagle-import") (part "led-rs_WS2812_5050"))
    )
    (comp (ref "D297")
      (value "WS2812_5050")
      (footprint "eagle-import:WS2812-5X5-4PIN")
      (libsource (lib "eagle-import") (part "led-rs_WS2812_5050"))
    )
    (comp (ref "D298")
      (value "WS2812_5050")
      (footprint "eagle-import:WS2812-5X5-4PIN")
      (libsource (lib "eagle-import") (part "led-rs_WS2812_5050"))
    )
    (comp (ref "D299")
      (value "WS2812_5050")
      (footprint "eagle-import:WS2812-5X5-4PIN")
      (libsource (lib "eagle-import") (part "led-rs_WS2812_5050"))
    )
    (comp (ref "D300")
      (value "WS2812_5050")
      (footprint "eagle-import:WS2812-5X5-4PIN")
      (libsource (lib "eagle-import") (part "led-rs_WS2812_5050"))
    )
    (comp (ref "D301")
      (value "WS2812_5050")
      (footprint "eagle-import:WS2812-5X5-4PIN")
      (libsource (lib "eagle-import") (part "led-rs_WS2812_5050"))
    )
    (comp (ref "D302")
      (value "WS2812_5050")
      (footprint "eagle-import:WS2812-5X5-4PIN")
      (libsource (lib "eagle-import") (part "led-rs_WS2812_5050"))
    )
    (comp (ref "D303")
      (value "WS2812_5050")
      (footprint "eagle-import:WS2812-5X5-4PIN")
      (libsource (lib "eagle-import") (part "led-rs_WS2812_5050"))
    )
    (comp (ref "D304")
      (value "WS2812_5050")
      (footprint "eagle-import:WS2812-5X5-4PIN")
      (libsource (lib "eagle-import") (part "led-rs_WS2812_5050"))
    )
    (comp (ref "D305")
      (value "WS2812_5050")
      (footprint "eagle-import:WS2812-5X5-4PIN")
      (libsource (lib "eagle-import") (part "led-rs_WS2812_5050"))
    )
    (comp (ref "D306")
      (value "WS2812_5050")
      (footprint "eagle-import:WS2812-5X5-4PIN")
      (libsource (lib "eagle-import") (part "led-rs_WS2812_5050"))
    )
    (comp (ref "D307")
      (value "WS2812_5050")
      (footprint "eagle-import:WS2812-5X5-4PIN")
      (libsource (lib "eagle-import") (part "led-rs_WS2812_5050"))
    )
    (comp (ref "D308")
      (value "WS2812_5050")
      (footprint "eagle-import:WS2812-5X5-4PIN")
      (libsource (lib "eagle-import") (part "led-rs_WS2812_5050"))
    )
    (comp (ref "D309")
      (value "WS2812_5050")
      (footprint "eagle-import:WS2812-5X5-4PIN")
      (libsource (lib "eagle-import") (part "led-rs_WS2812_5050"))
    )
    (comp (ref "D310")
      (value "WS2812_5050")
      (footprint "eagle-import:WS2812-5X5-4PIN")
      (libsource (lib "eagle-import") (part "led-rs_WS2812_5050"))
    )
    (comp (ref "D311")
      (value "WS2812_5050")
      (footprint "eagle-import:WS2812-5X5-4PIN")
      (libsource (lib "eagle-import") (part "led-rs_WS2812_5050"))
    )
    (comp (ref "D312")
      (value "WS2812_5050")
      (footprint "eagle-import:WS2812-5X5-4PIN")
      (libsource (lib "eagle-import") (part "led-rs_WS2812_5050"))
    )
    (comp (ref "D313")
      (value "WS2812_5050")
      (footprint "eagle-import:WS2812-5X5-4PIN")
      (libsource (lib "eagle-import") (part "led-rs_WS2812_5050"))
    )
    (comp (ref "D314")
      (value "WS2812_5050")
      (footprint "eagle-import:WS2812-5X5-4PIN")
      (libsource (lib "eagle-import") (part "led-rs_WS2812_5050"))
    )
    (comp (ref "D315")
      (value "WS2812_5050")
      (footprint "eagle-import:WS2812-5X5-4PIN")
      (libsource (lib "eagle-import") (part "led-rs_WS2812_5050"))
    )
    (comp (ref "D316")
      (value "WS2812_5050")
      (footprint "eagle-import:WS2812-5X5-4PIN")
      (libsource (lib "eagle-import") (part "led-rs_WS2812_5050"))
    )
    (comp (ref "D317")
      (value "WS2812_5050")
      (footprint "eagle-import:WS2812-5X5-4PIN")
      (libsource (lib "eagle-import") (part "led-rs_WS2812_5050"))
    )
    (comp (ref "D318")
      (value "WS2812_5050")
      (footprint "eagle-import:WS2812-5X5-4PIN")
      (libsource (lib "eagle-import") (part "led-rs_WS2812_5050"))
    )
    (comp (ref "D319")
      (value "WS2812_5050")
      (footprint "eagle-import:WS2812-5X5-4PIN")
      (libsource (lib "eagle-import") (part "led-rs_WS2812_5050"))
    )
    (comp (ref "D320")
      (value "WS2812_5050")
      (footprint "eagle-import:WS2812-5X5-4PIN")
      (libsource (lib "eagle-import") (part "led-rs_WS2812_5050"))
    )
    (comp (ref "D321")
      (value "WS2812_5050")
      (footprint "eagle-import:WS2812-5X5-4PIN")
      (libsource (lib "eagle-import") (part "led-rs_WS2812_5050"))
    )
    (comp (ref "D322")
      (value "WS2812_5050")
      (footprint "eagle-import:WS2812-5X5-4PIN")
      (libsource (lib "eagle-import") (part "led-rs_WS2812_5050"))
    )
    (comp (ref "D323")
      (value "WS2812_5050")
      (footprint "eagle-import:WS2812-5X5-4PIN")
      (libsource (lib "eagle-import") (part "led-rs_WS2812_5050"))
    )
    (comp (ref "D324")
      (value "WS2812_5050")
      (footprint "eagle-import:WS2812-5X5-4PIN")
      (libsource (lib "eagle-import") (part "led-rs_WS2812_5050"))
    )
    (comp (ref "D325")
      (value "WS2812_5050")
      (footprint "eagle-import:WS2812-5X5-4PIN")
      (libsource (lib "eagle-import") (part "led-rs_WS2812_5050"))
    )
    (comp (ref "D326")
      (value "WS2812_5050")
      (footprint "eagle-import:WS2812-5X5-4PIN")
      (libsource (lib "eagle-import") (part "led-rs_WS2812_5050"))
    )
    (comp (ref "D327")
      (value "WS2812_5050")
      (footprint "eagle-import:WS2812-5X5-4PIN")
      (libsource (lib "eagle-import") (part "led-rs_WS2812_5050"))
    )
    (comp (ref "D328")
      (value "WS2812_5050")
      (footprint "eagle-import:WS2812-5X5-4PIN")
      (libsource (lib "eagle-import") (part "led-rs_WS2812_5050"))
    )
    (comp (ref "D329")
      (value "WS2812_5050")
      (footprint "eagle-import:WS2812-5X5-4PIN")
      (libsource (lib "eagle-import") (part "led-rs_WS2812_5050"))
    )
    (comp (ref "D330")
      (value "WS2812_5050")
      (footprint "eagle-import:WS2812-5X5-4PIN")
      (libsource (lib "eagle-import") (part "led-rs_WS2812_5050"))
    )
    (comp (ref "D331")
      (value "WS2812_5050")
      (footprint "eagle-import:WS2812-5X5-4PIN")
      (libsource (lib "eagle-import") (part "led-rs_WS2812_5050"))
    )
    (comp (ref "D332")
      (value "WS2812_5050")
      (footprint "eagle-import:WS2812-5X5-4PIN")
      (libsource (lib "eagle-import") (part "led-rs_WS2812_5050"))
    )
    (comp (ref "D333")
      (value "WS2812_5050")
      (footprint "eagle-import:WS2812-5X5-4PIN")
      (libsource (lib "eagle-import") (part "led-rs_WS2812_5050"))
    )
    (comp (ref "D334")
      (value "WS2812_5050")
      (footprint "eagle-import:WS2812-5X5-4PIN")
      (libsource (lib "eagle-import") (part "led-rs_WS2812_5050"))
    )
    (comp (ref "D335")
      (value "WS2812_5050")
      (footprint "eagle-import:WS2812-5X5-4PIN")
      (libsource (lib "eagle-import") (part "led-rs_WS2812_5050"))
    )
    (comp (ref "D336")
      (value "WS2812_5050")
      (footprint "eagle-import:WS2812-5X5-4PIN")
      (libsource (lib "eagle-import") (part "led-rs_WS2812_5050"))
    )
    (comp (ref "D337")
      (value "WS2812_5050")
      (footprint "eagle-import:WS2812-5X5-4PIN")
      (libsource (lib "eagle-import") (part "led-rs_WS2812_5050"))
    )
    (comp (ref "D338")
      (value "WS2812_5050")
      (footprint "eagle-import:WS2812-5X5-4PIN")
      (libsource (lib "eagle-import") (part "led-rs_WS2812_5050"))
    )
    (comp (ref "D339")
      (value "WS2812_5050")
      (footprint "eagle-import:WS2812-5X5-4PIN")
      (libsource (lib "eagle-import") (part "led-rs_WS2812_5050"))
    )
    (comp (ref "D340")
      (value "WS2812_5050")
      (footprint "eagle-import:WS2812-5X5-4PIN")
      (libsource (lib "eagle-import") (part "led-rs_WS2812_5050"))
    )
    (comp (ref "D341")
      (value "WS2812_5050")
      (footprint "eagle-import:WS2812-5X5-4PIN")
      (libsource (lib "eagle-import") (part "led-rs_WS2812_5050"))
    )
    (comp (ref "D342")
      (value "WS2812_5050")
      (footprint "eagle-import:WS2812-5X5-4PIN")
      (libsource (lib "eagle-import") (part "led-rs_WS2812_5050"))
    )
    (comp (ref "D343")
      (value "WS2812_5050")
      (footprint "eagle-import:WS2812-5X5-4PIN")
      (libsource (lib "eagle-import") (part "led-rs_WS2812_5050"))
    )
    (comp (ref "D344")
      (value "WS2812_5050")
      (footprint "eagle-import:WS2812-5X5-4PIN")
      (libsource (lib "eagle-import") (part "led-rs_WS2812_5050"))
    )
    (comp (ref "D345")
      (value "WS2812_5050")
      (footprint "eagle-import:WS2812-5X5-4PIN")
      (libsource (lib "eagle-import") (part "led-rs_WS2812_5050"))
    )
    (comp (ref "D1")
      (value "WS2812_5050")
      (footprint "eagle-import:WS2812-5X5-4PIN")
      (libsource (lib "eagle-import") (part "led-rs_WS2812_5050"))
    )
    (comp (ref "D2")
      (value "WS2812_5050")
      (footprint "eagle-import:WS2812-5X5-4PIN")
      (libsource (lib "eagle-import") (part "led-rs_WS2812_5050"))
    )
    (comp (ref "D3")
      (value "WS2812_5050")
      (footprint "eagle-import:WS2812-5X5-4PIN")
      (libsource (lib "eagle-import") (part "led-rs_WS2812_5050"))
    )
    (comp (ref "D4")
      (value "WS2812_5050")
      (footprint "eagle-import:WS2812-5X5-4PIN")
      (libsource (lib "eagle-import") (part "led-rs_WS2812_5050"))
    )
    (comp (ref "D5")
      (value "WS2812_5050")
      (footprint "eagle-import:WS2812-5X5-4PIN")
      (libsource (lib "eagle-import") (part "led-rs_WS2812_5050"))
    )
    (comp (ref "D6")
      (value "WS2812_5050")
      (footprint "eagle-import:WS2812-5X5-4PIN")
      (libsource (lib "eagle-import") (part "led-rs_WS2812_5050"))
    )
    (comp (ref "D7")
      (value "WS2812_5050")
      (footprint "eagle-import:WS2812-5X5-4PIN")
      (libsource (lib "eagle-import") (part "led-rs_WS2812_5050"))
    )
    (comp (ref "D8")
      (value "WS2812_5050")
      (footprint "eagle-import:WS2812-5X5-4PIN")
      (libsource (lib "eagle-import") (part "led-rs_WS2812_5050"))
    )
    (comp (ref "D9")
      (value "WS2812_5050")
      (footprint "eagle-import:WS2812-5X5-4PIN")
      (libsource (lib "eagle-import") (part "led-rs_WS2812_5050"))
    )
    (comp (ref "D10")
      (value "WS2812_5050")
      (footprint "eagle-import:WS2812-5X5-4PIN")
      (libsource (lib "eagle-import") (part "led-rs_WS2812_5050"))
    )
    (comp (ref "D11")
      (value "WS2812_5050")
      (footprint "eagle-import:WS2812-5X5-4PIN")
      (libsource (lib "eagle-import") (part "led-rs_WS2812_5050"))
    )
    (comp (ref "D12")
      (value "WS2812_5050")
      (footprint "eagle-import:WS2812-5X5-4PIN")
      (libsource (lib "eagle-import") (part "led-rs_WS2812_5050"))
    )
    (comp (ref "D13")
      (value "WS2812_5050")
      (footprint "eagle-import:WS2812-5X5-4PIN")
      (libsource (lib "eagle-import") (part "led-rs_WS2812_5050"))
    )
    (comp (ref "D14")
      (value "WS2812_5050")
      (footprint "eagle-import:WS2812-5X5-4PIN")
      (libsource (lib "eagle-import") (part "led-rs_WS2812_5050"))
    )
    (comp (ref "D15")
      (value "WS2812_5050")
      (footprint "eagle-import:WS2812-5X5-4PIN")
      (libsource (lib "eagle-import") (part "led-rs_WS2812_5050"))
    )
    (comp (ref "D16")
      (value "WS2812_5050")
      (footprint "eagle-import:WS2812-5X5-4PIN")
      (libsource (lib "eagle-import") (part "led-rs_WS2812_5050"))
    )
    (comp (ref "D17")
      (value "WS2812_5050")
      (footprint "eagle-import:WS2812-5X5-4PIN")
      (libsource (lib "eagle-import") (part "led-rs_WS2812_5050"))
    )
    (comp (ref "D18")
      (value "WS2812_5050")
      (footprint "eagle-import:WS2812-5X5-4PIN")
      (libsource (lib "eagle-import") (part "led-rs_WS2812_5050"))
    )
    (comp (ref "D19")
      (value "WS2812_5050")
      (footprint "eagle-import:WS2812-5X5-4PIN")
      (libsource (lib "eagle-import") (part "led-rs_WS2812_5050"))
    )
    (comp (ref "D20")
      (value "WS2812_5050")
      (footprint "eagle-import:WS2812-5X5-4PIN")
      (libsource (lib "eagle-import") (part "led-rs_WS2812_5050"))
    )
    (comp (ref "D21")
      (value "WS2812_5050")
      (footprint "eagle-import:WS2812-5X5-4PIN")
      (libsource (lib "eagle-import") (part "led-rs_WS2812_5050"))
    )
    (comp (ref "D22")
      (value "WS2812_5050")
      (footprint "eagle-import:WS2812-5X5-4PIN")
      (libsource (lib "eagle-import") (part "led-rs_WS2812_5050"))
    )
    (comp (ref "D23")
      (value "WS2812_5050")
      (footprint "eagle-import:WS2812-5X5-4PIN")
      (libsource (lib "eagle-import") (part "led-rs_WS2812_5050"))
    )
    (comp (ref "D24")
      (value "WS2812_5050")
      (footprint "eagle-import:WS2812-5X5-4PIN")
      (libsource (lib "eagle-import") (part "led-rs_WS2812_5050"))
    )
    (comp (ref "D25")
      (value "WS2812_5050")
      (footprint "eagle-import:WS2812-5X5-4PIN")
      (libsource (lib "eagle-import") (part "led-rs_WS2812_5050"))
    )
    (comp (ref "D26")
      (value "WS2812_5050")
      (footprint "eagle-import:WS2812-5X5-4PIN")
      (libsource (lib "eagle-import") (part "led-rs_WS2812_5050"))
    )
    (comp (ref "D27")
      (value "WS2812_5050")
      (footprint "eagle-import:WS2812-5X5-4PIN")
      (libsource (lib "eagle-import") (part "led-rs_WS2812_5050"))
    )
    (comp (ref "D28")
      (value "WS2812_5050")
      (footprint "eagle-import:WS2812-5X5-4PIN")
      (libsource (lib "eagle-import") (part "led-rs_WS2812_5050"))
    )
    (comp (ref "D29")
      (value "WS2812_5050")
      (footprint "eagle-import:WS2812-5X5-4PIN")
      (libsource (lib "eagle-import") (part "led-rs_WS2812_5050"))
    )
    (comp (ref "D30")
      (value "WS2812_5050")
      (footprint "eagle-import:WS2812-5X5-4PIN")
      (libsource (lib "eagle-import") (part "led-rs_WS2812_5050"))
    )
    (comp (ref "D31")
      (value "WS2812_5050")
      (footprint "eagle-import:WS2812-5X5-4PIN")
      (libsource (lib "eagle-import") (part "led-rs_WS2812_5050"))
    )
    (comp (ref "D32")
      (value "WS2812_5050")
      (footprint "eagle-import:WS2812-5X5-4PIN")
      (libsource (lib "eagle-import") (part "led-rs_WS2812_5050"))
    )
    (comp (ref "D33")
      (value "WS2812_5050")
      (footprint "eagle-import:WS2812-5X5-4PIN")
      (libsource (lib "eagle-import") (part "led-rs_WS2812_5050"))
    )
    (comp (ref "D34")
      (value "WS2812_5050")
      (footprint "eagle-import:WS2812-5X5-4PIN")
      (libsource (lib "eagle-import") (part "led-rs_WS2812_5050"))
    )
    (comp (ref "D35")
      (value "WS2812_5050")
      (footprint "eagle-import:WS2812-5X5-4PIN")
      (libsource (lib "eagle-import") (part "led-rs_WS2812_5050"))
    )
    (comp (ref "D36")
      (value "WS2812_5050")
      (footprint "eagle-import:WS2812-5X5-4PIN")
      (libsource (lib "eagle-import") (part "led-rs_WS2812_5050"))
    )
    (comp (ref "D37")
      (value "WS2812_5050")
      (footprint "eagle-import:WS2812-5X5-4PIN")
      (libsource (lib "eagle-import") (part "led-rs_WS2812_5050"))
    )
    (comp (ref "D38")
      (value "WS2812_5050")
      (footprint "eagle-import:WS2812-5X5-4PIN")
      (libsource (lib "eagle-import") (part "led-rs_WS2812_5050"))
    )
    (comp (ref "D39")
      (value "WS2812_5050")
      (footprint "eagle-import:WS2812-5X5-4PIN")
      (libsource (lib "eagle-import") (part "led-rs_WS2812_5050"))
    )
    (comp (ref "D40")
      (value "WS2812_5050")
      (footprint "eagle-import:WS2812-5X5-4PIN")
      (libsource (lib "eagle-import") (part "led-rs_WS2812_5050"))
    )
    (comp (ref "D41")
      (value "WS2812_5050")
      (footprint "eagle-import:WS2812-5X5-4PIN")
      (libsource (lib "eagle-import") (part "led-rs_WS2812_5050"))
    )
    (comp (ref "D42")
      (value "WS2812_5050")
      (footprint "eagle-import:WS2812-5X5-4PIN")
      (libsource (lib "eagle-import") (part "led-rs_WS2812_5050"))
    )
    (comp (ref "D43")
      (value "WS2812_5050")
      (footprint "eagle-import:WS2812-5X5-4PIN")
      (libsource (lib "eagle-import") (part "led-rs_WS2812_5050"))
    )
    (comp (ref "D44")
      (value "WS2812_5050")
      (footprint "eagle-import:WS2812-5X5-4PIN")
      (libsource (lib "eagle-import") (part "led-rs_WS2812_5050"))
    )
    (comp (ref "D45")
      (value "WS2812_5050")
      (footprint "eagle-import:WS2812-5X5-4PIN")
      (libsource (lib "eagle-import") (part "led-rs_WS2812_5050"))
    )
    (comp (ref "D46")
      (value "WS2812_5050")
      (footprint "eagle-import:WS2812-5X5-4PIN")
      (libsource (lib "eagle-import") (part "led-rs_WS2812_5050"))
    )
    (comp (ref "D47")
      (value "WS2812_5050")
      (footprint "eagle-import:WS2812-5X5-4PIN")
      (libsource (lib "eagle-import") (part "led-rs_WS2812_5050"))
    )
    (comp (ref "D48")
      (value "WS2812_5050")
      (footprint "eagle-import:WS2812-5X5-4PIN")
      (libsource (lib "eagle-import") (part "led-rs_WS2812_5050"))
    )
    (comp (ref "D49")
      (value "WS2812_5050")
      (footprint "eagle-import:WS2812-5X5-4PIN")
      (libsource (lib "eagle-import") (part "led-rs_WS2812_5050"))
    )
    (comp (ref "D50")
      (value "WS2812_5050")
      (footprint "eagle-import:WS2812-5X5-4PIN")
      (libsource (lib "eagle-import") (part "led-rs_WS2812_5050"))
    )
    (comp (ref "D51")
      (value "WS2812_5050")
      (footprint "eagle-import:WS2812-5X5-4PIN")
      (libsource (lib "eagle-import") (part "led-rs_WS2812_5050"))
    )
    (comp (ref "D52")
      (value "WS2812_5050")
      (footprint "eagle-import:WS2812-5X5-4PIN")
      (libsource (lib "eagle-import") (part "led-rs_WS2812_5050"))
    )
    (comp (ref "D53")
      (value "WS2812_5050")
      (footprint "eagle-import:WS2812-5X5-4PIN")
      (libsource (lib "eagle-import") (part "led-rs_WS2812_5050"))
    )
    (comp (ref "D54")
      (value "WS2812_5050")
      (footprint "eagle-import:WS2812-5X5-4PIN")
      (libsource (lib "eagle-import") (part "led-rs_WS2812_5050"))
    )
    (comp (ref "D55")
      (value "WS2812_5050")
      (footprint "eagle-import:WS2812-5X5-4PIN")
      (libsource (lib "eagle-import") (part "led-rs_WS2812_5050"))
    )
    (comp (ref "D56")
      (value "WS2812_5050")
      (footprint "eagle-import:WS2812-5X5-4PIN")
      (libsource (lib "eagle-import") (part "led-rs_WS2812_5050"))
    )
    (comp (ref "D57")
      (value "WS2812_5050")
      (footprint "eagle-import:WS2812-5X5-4PIN")
      (libsource (lib "eagle-import") (part "led-rs_WS2812_5050"))
    )
    (comp (ref "D58")
      (value "WS2812_5050")
      (footprint "eagle-import:WS2812-5X5-4PIN")
      (libsource (lib "eagle-import") (part "led-rs_WS2812_5050"))
    )
    (comp (ref "D59")
      (value "WS2812_5050")
      (footprint "eagle-import:WS2812-5X5-4PIN")
      (libsource (lib "eagle-import") (part "led-rs_WS2812_5050"))
    )
    (comp (ref "D60")
      (value "WS2812_5050")
      (footprint "eagle-import:WS2812-5X5-4PIN")
      (libsource (lib "eagle-import") (part "led-rs_WS2812_5050"))
    )
    (comp (ref "D61")
      (value "WS2812_5050")
      (footprint "eagle-import:WS2812-5X5-4PIN")
      (libsource (lib "eagle-import") (part "led-rs_WS2812_5050"))
    )
    (comp (ref "D62")
      (value "WS2812_5050")
      (footprint "eagle-import:WS2812-5X5-4PIN")
      (libsource (lib "eagle-import") (part "led-rs_WS2812_5050"))
    )
    (comp (ref "D63")
      (value "WS2812_5050")
      (footprint "eagle-import:WS2812-5X5-4PIN")
      (libsource (lib "eagle-import") (part "led-rs_WS2812_5050"))
    )
    (comp (ref "D64")
      (value "WS2812_5050")
      (footprint "eagle-import:WS2812-5X5-4PIN")
      (libsource (lib "eagle-import") (part "led-rs_WS2812_5050"))
    )
    (comp (ref "D65")
      (value "WS2812_5050")
      (footprint "eagle-import:WS2812-5X5-4PIN")
      (libsource (lib "eagle-import") (part "led-rs_WS2812_5050"))
    )
    (comp (ref "D66")
      (value "WS2812_5050")
      (footprint "eagle-import:WS2812-5X5-4PIN")
      (libsource (lib "eagle-import") (part "led-rs_WS2812_5050"))
    )
    (comp (ref "D67")
      (value "WS2812_5050")
      (footprint "eagle-import:WS2812-5X5-4PIN")
      (libsource (lib "eagle-import") (part "led-rs_WS2812_5050"))
    )
    (comp (ref "D68")
      (value "WS2812_5050")
      (footprint "eagle-import:WS2812-5X5-4PIN")
      (libsource (lib "eagle-import") (part "led-rs_WS2812_5050"))
    )
    (comp (ref "D69")
      (value "WS2812_5050")
      (footprint "eagle-import:WS2812-5X5-4PIN")
      (libsource (lib "eagle-import") (part "led-rs_WS2812_5050"))
    )
    (comp (ref "D70")
      (value "WS2812_5050")
      (footprint "eagle-import:WS2812-5X5-4PIN")
      (libsource (lib "eagle-import") (part "led-rs_WS2812_5050"))
    )
    (comp (ref "D71")
      (value "WS2812_5050")
      (footprint "eagle-import:WS2812-5X5-4PIN")
      (libsource (lib "eagle-import") (part "led-rs_WS2812_5050"))
    )
    (comp (ref "D72")
      (value "WS2812_5050")
      (footprint "eagle-import:WS2812-5X5-4PIN")
      (libsource (lib "eagle-import") (part "led-rs_WS2812_5050"))
    )
    (comp (ref "D73")
      (value "WS2812_5050")
      (footprint "eagle-import:WS2812-5X5-4PIN")
      (libsource (lib "eagle-import") (part "led-rs_WS2812_5050"))
    )
    (comp (ref "D74")
      (value "WS2812_5050")
      (footprint "eagle-import:WS2812-5X5-4PIN")
      (libsource (lib "eagle-import") (part "led-rs_WS2812_5050"))
    )
    (comp (ref "D75")
      (value "WS2812_5050")
      (footprint "eagle-import:WS2812-5X5-4PIN")
      (libsource (lib "eagle-import") (part "led-rs_WS2812_5050"))
    )
    (comp (ref "D76")
      (value "WS2812_5050")
      (footprint "eagle-import:WS2812-5X5-4PIN")
      (libsource (lib "eagle-import") (part "led-rs_WS2812_5050"))
    )
    (comp (ref "D77")
      (value "WS2812_5050")
      (footprint "eagle-import:WS2812-5X5-4PIN")
      (libsource (lib "eagle-import") (part "led-rs_WS2812_5050"))
    )
    (comp (ref "D78")
      (value "WS2812_5050")
      (footprint "eagle-import:WS2812-5X5-4PIN")
      (libsource (lib "eagle-import") (part "led-rs_WS2812_5050"))
    )
    (comp (ref "D79")
      (value "WS2812_5050")
      (footprint "eagle-import:WS2812-5X5-4PIN")
      (libsource (lib "eagle-import") (part "led-rs_WS2812_5050"))
    )
    (comp (ref "D80")
      (value "WS2812_5050")
      (footprint "eagle-import:WS2812-5X5-4PIN")
      (libsource (lib "eagle-import") (part "led-rs_WS2812_5050"))
    )
    (comp (ref "D81")
      (value "WS2812_5050")
      (footprint "eagle-import:WS2812-5X5-4PIN")
      (libsource (lib "eagle-import") (part "led-rs_WS2812_5050"))
    )
    (comp (ref "D82")
      (value "WS2812_5050")
      (footprint "eagle-import:WS2812-5X5-4PIN")
      (libsource (lib "eagle-import") (part "led-rs_WS2812_5050"))
    )
    (comp (ref "D83")
      (value "WS2812_5050")
      (footprint "eagle-import:WS2812-5X5-4PIN")
      (libsource (lib "eagle-import") (part "led-rs_WS2812_5050"))
    )
    (comp (ref "D84")
      (value "WS2812_5050")
      (footprint "eagle-import:WS2812-5X5-4PIN")
      (libsource (lib "eagle-import") (part "led-rs_WS2812_5050"))
    )
    (comp (ref "D85")
      (value "WS2812_5050")
      (footprint "eagle-import:WS2812-5X5-4PIN")
      (libsource (lib "eagle-import") (part "led-rs_WS2812_5050"))
    )
    (comp (ref "D86")
      (value "WS2812_5050")
      (footprint "eagle-import:WS2812-5X5-4PIN")
      (libsource (lib "eagle-import") (part "led-rs_WS2812_5050"))
    )
    (comp (ref "D87")
      (value "WS2812_5050")
      (footprint "eagle-import:WS2812-5X5-4PIN")
      (libsource (lib "eagle-import") (part "led-rs_WS2812_5050"))
    )
    (comp (ref "D88")
      (value "WS2812_5050")
      (footprint "eagle-import:WS2812-5X5-4PIN")
      (libsource (lib "eagle-import") (part "led-rs_WS2812_5050"))
    )
    (comp (ref "D89")
      (value "WS2812_5050")
      (footprint "eagle-import:WS2812-5X5-4PIN")
      (libsource (lib "eagle-import") (part "led-rs_WS2812_5050"))
    )
    (comp (ref "D90")
      (value "WS2812_5050")
      (footprint "eagle-import:WS2812-5X5-4PIN")
      (libsource (lib "eagle-import") (part "led-rs_WS2812_5050"))
    )
    (comp (ref "D91")
      (value "WS2812_5050")
      (footprint "eagle-import:WS2812-5X5-4PIN")
      (libsource (lib "eagle-import") (part "led-rs_WS2812_5050"))
    )
    (comp (ref "D92")
      (value "WS2812_5050")
      (footprint "eagle-import:WS2812-5X5-4PIN")
      (libsource (lib "eagle-import") (part "led-rs_WS2812_5050"))
    )
    (comp (ref "D93")
      (value "WS2812_5050")
      (footprint "eagle-import:WS2812-5X5-4PIN")
      (libsource (lib "eagle-import") (part "led-rs_WS2812_5050"))
    )
    (comp (ref "D94")
      (value "WS2812_5050")
      (footprint "eagle-import:WS2812-5X5-4PIN")
      (libsource (lib "eagle-import") (part "led-rs_WS2812_5050"))
    )
    (comp (ref "D95")
      (value "WS2812_5050")
      (footprint "eagle-import:WS2812-5X5-4PIN")
      (libsource (lib "eagle-import") (part "led-rs_WS2812_5050"))
    )
    (comp (ref "D96")
      (value "WS2812_5050")
      (footprint "eagle-import:WS2812-5X5-4PIN")
      (libsource (lib "eagle-import") (part "led-rs_WS2812_5050"))
    )
    (comp (ref "D97")
      (value "WS2812_5050")
      (footprint "eagle-import:WS2812-5X5-4PIN")
      (libsource (lib "eagle-import") (part "led-rs_WS2812_5050"))
    )
    (comp (ref "D98")
      (value "WS2812_5050")
      (footprint "eagle-import:WS2812-5X5-4PIN")
      (libsource (lib "eagle-import") (part "led-rs_WS2812_5050"))
    )
    (comp (ref "D99")
      (value "WS2812_5050")
      (footprint "eagle-import:WS2812-5X5-4PIN")
      (libsource (lib "eagle-import") (part "led-rs_WS2812_5050"))
    )
    (comp (ref "D100")
      (value "WS2812_5050")
      (footprint "eagle-import:WS2812-5X5-4PIN")
      (libsource (lib "eagle-import") (part "led-rs_WS2812_5050"))
    )
    (comp (ref "D101")
      (value "WS2812_5050")
      (footprint "eagle-import:WS2812-5X5-4PIN")
      (libsource (lib "eagle-import") (part "led-rs_WS2812_5050"))
    )
    (comp (ref "D102")
      (value "WS2812_5050")
      (footprint "eagle-import:WS2812-5X5-4PIN")
      (libsource (lib "eagle-import") (part "led-rs_WS2812_5050"))
    )
    (comp (ref "D103")
      (value "WS2812_5050")
      (footprint "eagle-import:WS2812-5X5-4PIN")
      (libsource (lib "eagle-import") (part "led-rs_WS2812_5050"))
    )
    (comp (ref "D104")
      (value "WS2812_5050")
      (footprint "eagle-import:WS2812-5X5-4PIN")
      (libsource (lib "eagle-import") (part "led-rs_WS2812_5050"))
    )
    (comp (ref "D105")
      (value "WS2812_5050")
      (footprint "eagle-import:WS2812-5X5-4PIN")
      (libsource (lib "eagle-import") (part "led-rs_WS2812_5050"))
    )
    (comp (ref "D106")
      (value "WS2812_5050")
      (footprint "eagle-import:WS2812-5X5-4PIN")
      (libsource (lib "eagle-import") (part "led-rs_WS2812_5050"))
    )
    (comp (ref "D107")
      (value "WS2812_5050")
      (footprint "eagle-import:WS2812-5X5-4PIN")
      (libsource (lib "eagle-import") (part "led-rs_WS2812_5050"))
    )
    (comp (ref "D108")
      (value "WS2812_5050")
      (footprint "eagle-import:WS2812-5X5-4PIN")
      (libsource (lib "eagle-import") (part "led-rs_WS2812_5050"))
    )
    (comp (ref "D109")
      (value "WS2812_5050")
      (footprint "eagle-import:WS2812-5X5-4PIN")
      (libsource (lib "eagle-import") (part "led-rs_WS2812_5050"))
    )
    (comp (ref "D110")
      (value "WS2812_5050")
      (footprint "eagle-import:WS2812-5X5-4PIN")
      (libsource (lib "eagle-import") (part "led-rs_WS2812_5050"))
    )
    (comp (ref "D111")
      (value "WS2812_5050")
      (footprint "eagle-import:WS2812-5X5-4PIN")
      (libsource (lib "eagle-import") (part "led-rs_WS2812_5050"))
    )
    (comp (ref "D112")
      (value "WS2812_5050")
      (footprint "eagle-import:WS2812-5X5-4PIN")
      (libsource (lib "eagle-import") (part "led-rs_WS2812_5050"))
    )
    (comp (ref "D113")
      (value "WS2812_5050")
      (footprint "eagle-import:WS2812-5X5-4PIN")
      (libsource (lib "eagle-import") (part "led-rs_WS2812_5050"))
    )
    (comp (ref "D114")
      (value "WS2812_5050")
      (footprint "eagle-import:WS2812-5X5-4PIN")
      (libsource (lib "eagle-import") (part "led-rs_WS2812_5050"))
    )
    (comp (ref "D115")
      (value "WS2812_5050")
      (footprint "eagle-import:WS2812-5X5-4PIN")
      (libsource (lib "eagle-import") (part "led-rs_WS2812_5050"))
    )
    (comp (ref "D116")
      (value "WS2812_5050")
      (footprint "eagle-import:WS2812-5X5-4PIN")
      (libsource (lib "eagle-import") (part "led-rs_WS2812_5050"))
    )
    (comp (ref "D117")
      (value "WS2812_5050")
      (footprint "eagle-import:WS2812-5X5-4PIN")
      (libsource (lib "eagle-import") (part "led-rs_WS2812_5050"))
    )
    (comp (ref "D118")
      (value "WS2812_5050")
      (footprint "eagle-import:WS2812-5X5-4PIN")
      (libsource (lib "eagle-import") (part "led-rs_WS2812_5050"))
    )
    (comp (ref "D119")
      (value "WS2812_5050")
      (footprint "eagle-import:WS2812-5X5-4PIN")
      (libsource (lib "eagle-import") (part "led-rs_WS2812_5050"))
    )
    (comp (ref "D120")
      (value "WS2812_5050")
      (footprint "eagle-import:WS2812-5X5-4PIN")
      (libsource (lib "eagle-import") (part "led-rs_WS2812_5050"))
    )
    (comp (ref "C1")
      (value "CPOL-EUE2.5-6")
      (footprint "eagle-import:E2,5-6")
      (libsource (lib "eagle-import") (part "CPOL-EUE2.5-6"))
    )
    (comp (ref "C2")
      (value "CPOL-EUE2.5-6")
      (footprint "eagle-import:E2,5-6")
      (libsource (lib "eagle-import") (part "CPOL-EUE2.5-6"))
    )
    (comp (ref "C3")
      (value "CPOL-EUE2.5-6")
      (footprint "eagle-import:E2,5-6")
      (libsource (lib "eagle-import") (part "CPOL-EUE2.5-6"))
    )
    (comp (ref "C4")
      (value "CPOL-EUE2.5-6")
      (footprint "eagle-import:E2,5-6")
      (libsource (lib "eagle-import") (part "CPOL-EUE2.5-6"))
    )
    (comp (ref "C5")
      (value "CPOL-EUE2.5-6")
      (footprint "eagle-import:E2,5-6")
      (libsource (lib "eagle-import") (part "CPOL-EUE2.5-6"))
    )
    (comp (ref "C6")
      (value "CPOL-EUE2.5-6")
      (footprint "eagle-import:E2,5-6")
      (libsource (lib "eagle-import") (part "CPOL-EUE2.5-6"))
    )
    (comp (ref "C7")
      (value "CPOL-EUE2.5-6")
      (footprint "eagle-import:E2,5-6")
      (libsource (lib "eagle-import") (part "CPOL-EUE2.5-6"))
    )
    (comp (ref "C8")
      (value "CPOL-EUE2.5-6")
      (footprint "eagle-import:E2,5-6")
      (libsource (lib "eagle-import") (part "CPOL-EUE2.5-6"))
    )
    (comp (ref "C9")
      (value "CPOL-EUE2.5-6")
      (footprint "eagle-import:E2,5-6")
      (libsource (lib "eagle-import") (part "CPOL-EUE2.5-6"))
    )
    (comp (ref "C10")
      (value "CPOL-EUE2.5-6")
      (footprint "eagle-import:E2,5-6")
      (libsource (lib "eagle-import") (part "CPOL-EUE2.5-6"))
    )
    (comp (ref "C11")
      (value "CPOL-EUE2.5-6")
      (footprint "eagle-import:E2,5-6")
      (libsource (lib "eagle-import") (part "CPOL-EUE2.5-6"))
    )
    (comp (ref "C12")
      (value "CPOL-EUE2.5-6")
      (footprint "eagle-import:E2,5-6")
      (libsource (lib "eagle-import") (part "CPOL-EUE2.5-6"))
    )
    (comp (ref "C13")
      (value "CPOL-EUE2.5-6")
      (footprint "eagle-import:E2,5-6")
      (libsource (lib "eagle-import") (part "CPOL-EUE2.5-6"))
    )
    (comp (ref "C14")
      (value "CPOL-EUE2.5-6")
      (footprint "eagle-import:E2,5-6")
      (libsource (lib "eagle-import") (part "CPOL-EUE2.5-6"))
    )
    (comp (ref "C15")
      (value "CPOL-EUE2.5-6")
      (footprint "eagle-import:E2,5-6")
      (libsource (lib "eagle-import") (part "CPOL-EUE2.5-6"))
    )
    (comp (ref "C16")
      (value "CPOL-EUE2.5-6")
      (footprint "eagle-import:E2,5-6")
      (libsource (lib "eagle-import") (part "CPOL-EUE2.5-6"))
    )
    (comp (ref "C17")
      (value "CPOL-EUE2.5-6")
      (footprint "eagle-import:E2,5-6")
      (libsource (lib "eagle-import") (part "CPOL-EUE2.5-6"))
    )
    (comp (ref "C18")
      (value "CPOL-EUE2.5-6")
      (footprint "eagle-import:E2,5-6")
      (libsource (lib "eagle-import") (part "CPOL-EUE2.5-6"))
    )
    (comp (ref "C19")
      (value "CPOL-EUE2.5-6")
      (footprint "eagle-import:E2,5-6")
      (libsource (lib "eagle-import") (part "CPOL-EUE2.5-6"))
    )
    (comp (ref "C20")
      (value "CPOL-EUE2.5-6")
      (footprint "eagle-import:E2,5-6")
      (libsource (lib "eagle-import") (part "CPOL-EUE2.5-6"))
    )
    (comp (ref "C21")
      (value "CPOL-EUE2.5-6")
      (footprint "eagle-import:E2,5-6")
      (libsource (lib "eagle-import") (part "CPOL-EUE2.5-6"))
    )
    (comp (ref "C22")
      (value "CPOL-EUE2.5-6")
      (footprint "eagle-import:E2,5-6")
      (libsource (lib "eagle-import") (part "CPOL-EUE2.5-6"))
    )
    (comp (ref "C23")
      (value "CPOL-EUE2.5-6")
      (footprint "eagle-import:E2,5-6")
      (libsource (lib "eagle-import") (part "CPOL-EUE2.5-6"))
    )
    (comp (ref "C24")
      (value "CPOL-EUE2.5-6")
      (footprint "eagle-import:E2,5-6")
      (libsource (lib "eagle-import") (part "CPOL-EUE2.5-6"))
    )
    (comp (ref "C25")
      (value "100nF")
      (footprint "eagle-import:C0603K")
      (libsource (lib "eagle-import") (part "C-EUC0603K"))
    )
    (comp (ref "C26")
      (value "100nF")
      (footprint "eagle-import:C0603K")
      (libsource (lib "eagle-import") (part "C-EUC0603K"))
    )
    (comp (ref "C27")
      (value "100nF")
      (footprint "eagle-import:C0603K")
      (libsource (lib "eagle-import") (part "C-EUC0603K"))
    )
    (comp (ref "C28")
      (value "100nF")
      (footprint "eagle-import:C0603K")
      (libsource (lib "eagle-import") (part "C-EUC0603K"))
    )
    (comp (ref "C29")
      (value "100nF")
      (footprint "eagle-import:C0603K")
      (libsource (lib "eagle-import") (part "C-EUC0603K"))
    )
    (comp (ref "C30")
      (value "100nF")
      (footprint "eagle-import:C0603K")
      (libsource (lib "eagle-import") (part "C-EUC0603K"))
    )
    (comp (ref "C31")
      (value "100nF")
      (footprint "eagle-import:C0603K")
      (libsource (lib "eagle-import") (part "C-EUC0603K"))
    )
    (comp (ref "C32")
      (value "100nF")
      (footprint "eagle-import:C0603K")
      (libsource (lib "eagle-import") (part "C-EUC0603K"))
    )
    (comp (ref "C33")
      (value "100nF")
      (footprint "eagle-import:C0603K")
      (libsource (lib "eagle-import") (part "C-EUC0603K"))
    )
    (comp (ref "C34")
      (value "100nF")
      (footprint "eagle-import:C0603K")
      (libsource (lib "eagle-import") (part "C-EUC0603K"))
    )
    (comp (ref "C35")
      (value "100nF")
      (footprint "eagle-import:C0603K")
      (libsource (lib "eagle-import") (part "C-EUC0603K"))
    )
    (comp (ref "C36")
      (value "100nF")
      (footprint "eagle-import:C0603K")
      (libsource (lib "eagle-import") (part "C-EUC0603K"))
    )
    (comp (ref "C37")
      (value "100nF")
      (footprint "eagle-import:C0603K")
      (libsource (lib "eagle-import") (part "C-EUC0603K"))
    )
    (comp (ref "C38")
      (value "100nF")
      (footprint "eagle-import:C0603K")
      (libsource (lib "eagle-import") (part "C-EUC0603K"))
    )
    (comp (ref "C39")
      (value "100nF")
      (footprint "eagle-import:C0603K")
      (libsource (lib "eagle-import") (part "C-EUC0603K"))
    )
    (comp (ref "C40")
      (value "100nF")
      (footprint "eagle-import:C0603K")
      (libsource (lib "eagle-import") (part "C-EUC0603K"))
    )
    (comp (ref "C41")
      (value "100nF")
      (footprint "eagle-import:C0603K")
      (libsource (lib "eagle-import") (part "C-EUC0603K"))
    )
    (comp (ref "C42")
      (value "100nF")
      (footprint "eagle-import:C0603K")
      (libsource (lib "eagle-import") (part "C-EUC0603K"))
    )
    (comp (ref "C43")
      (value "100nF")
      (footprint "eagle-import:C0603K")
      (libsource (lib "eagle-import") (part "C-EUC0603K"))
    )
    (comp (ref "C44")
      (value "100nF")
      (footprint "eagle-import:C0603K")
      (libsource (lib "eagle-import") (part "C-EUC0603K"))
    )
    (comp (ref "C45")
      (value "100nF")
      (footprint "eagle-import:C0603K")
      (libsource (lib "eagle-import") (part "C-EUC0603K"))
    )
    (comp (ref "C46")
      (value "100nF")
      (footprint "eagle-import:C0603K")
      (libsource (lib "eagle-import") (part "C-EUC0603K"))
    )
    (comp (ref "C47")
      (value "100nF")
      (footprint "eagle-import:C0603K")
      (libsource (lib "eagle-import") (part "C-EUC0603K"))
    )
    (comp (ref "C48")
      (value "100nF")
      (footprint "eagle-import:C0603K")
      (libsource (lib "eagle-import") (part "C-EUC0603K"))
    )
    (comp (ref "C49")
      (value "100nF")
      (footprint "eagle-import:C0603K")
      (libsource (lib "eagle-import") (part "C-EUC0603K"))
    )
    (comp (ref "C50")
      (value "100nF")
      (footprint "eagle-import:C0603K")
      (libsource (lib "eagle-import") (part "C-EUC0603K"))
    )
    (comp (ref "C51")
      (value "100nF")
      (footprint "eagle-import:C0603K")
      (libsource (lib "eagle-import") (part "C-EUC0603K"))
    )
    (comp (ref "C52")
      (value "100nF")
      (footprint "eagle-import:C0603K")
      (libsource (lib "eagle-import") (part "C-EUC0603K"))
    )
    (comp (ref "C53")
      (value "100nF")
      (footprint "eagle-import:C0603K")
      (libsource (lib "eagle-import") (part "C-EUC0603K"))
    )
    (comp (ref "C54")
      (value "100nF")
      (footprint "eagle-import:C0603K")
      (libsource (lib "eagle-import") (part "C-EUC0603K"))
    )
    (comp (ref "C55")
      (value "100nF")
      (footprint "eagle-import:C0603K")
      (libsource (lib "eagle-import") (part "C-EUC0603K"))
    )
    (comp (ref "C56")
      (value "100nF")
      (footprint "eagle-import:C0603K")
      (libsource (lib "eagle-import") (part "C-EUC0603K"))
    )
    (comp (ref "C57")
      (value "100nF")
      (footprint "eagle-import:C0603K")
      (libsource (lib "eagle-import") (part "C-EUC0603K"))
    )
    (comp (ref "C58")
      (value "100nF")
      (footprint "eagle-import:C0603K")
      (libsource (lib "eagle-import") (part "C-EUC0603K"))
    )
    (comp (ref "C59")
      (value "100nF")
      (footprint "eagle-import:C0603K")
      (libsource (lib "eagle-import") (part "C-EUC0603K"))
    )
    (comp (ref "C60")
      (value "100nF")
      (footprint "eagle-import:C0603K")
      (libsource (lib "eagle-import") (part "C-EUC0603K"))
    )
    (comp (ref "C61")
      (value "100nF")
      (footprint "eagle-import:C0603K")
      (libsource (lib "eagle-import") (part "C-EUC0603K"))
    )
    (comp (ref "C62")
      (value "100nF")
      (footprint "eagle-import:C0603K")
      (libsource (lib "eagle-import") (part "C-EUC0603K"))
    )
    (comp (ref "C63")
      (value "100nF")
      (footprint "eagle-import:C0603K")
      (libsource (lib "eagle-import") (part "C-EUC0603K"))
    )
    (comp (ref "C64")
      (value "100nF")
      (footprint "eagle-import:C0603K")
      (libsource (lib "eagle-import") (part "C-EUC0603K"))
    )
    (comp (ref "C65")
      (value "100nF")
      (footprint "eagle-import:C0603K")
      (libsource (lib "eagle-import") (part "C-EUC0603K"))
    )
    (comp (ref "C66")
      (value "100nF")
      (footprint "eagle-import:C0603K")
      (libsource (lib "eagle-import") (part "C-EUC0603K"))
    )
    (comp (ref "C67")
      (value "100nF")
      (footprint "eagle-import:C0603K")
      (libsource (lib "eagle-import") (part "C-EUC0603K"))
    )
    (comp (ref "C68")
      (value "100nF")
      (footprint "eagle-import:C0603K")
      (libsource (lib "eagle-import") (part "C-EUC0603K"))
    )
    (comp (ref "C69")
      (value "100nF")
      (footprint "eagle-import:C0603K")
      (libsource (lib "eagle-import") (part "C-EUC0603K"))
    )
    (comp (ref "C70")
      (value "100nF")
      (footprint "eagle-import:C0603K")
      (libsource (lib "eagle-import") (part "C-EUC0603K"))
    )
    (comp (ref "C71")
      (value "100nF")
      (footprint "eagle-import:C0603K")
      (libsource (lib "eagle-import") (part "C-EUC0603K"))
    )
    (comp (ref "C72")
      (value "100nF")
      (footprint "eagle-import:C0603K")
      (libsource (lib "eagle-import") (part "C-EUC0603K"))
    )
    (comp (ref "C73")
      (value "100nF")
      (footprint "eagle-import:C0603K")
      (libsource (lib "eagle-import") (part "C-EUC0603K"))
    )
    (comp (ref "C74")
      (value "100nF")
      (footprint "eagle-import:C0603K")
      (libsource (lib "eagle-import") (part "C-EUC0603K"))
    )
    (comp (ref "C75")
      (value "100nF")
      (footprint "eagle-import:C0603K")
      (libsource (lib "eagle-import") (part "C-EUC0603K"))
    )
    (comp (ref "C76")
      (value "100nF")
      (footprint "eagle-import:C0603K")
      (libsource (lib "eagle-import") (part "C-EUC0603K"))
    )
    (comp (ref "C77")
      (value "100nF")
      (footprint "eagle-import:C0603K")
      (libsource (lib "eagle-import") (part "C-EUC0603K"))
    )
    (comp (ref "C78")
      (value "100nF")
      (footprint "eagle-import:C0603K")
      (libsource (lib "eagle-import") (part "C-EUC0603K"))
    )
    (comp (ref "C79")
      (value "100nF")
      (footprint "eagle-import:C0603K")
      (libsource (lib "eagle-import") (part "C-EUC0603K"))
    )
    (comp (ref "C80")
      (value "100nF")
      (footprint "eagle-import:C0603K")
      (libsource (lib "eagle-import") (part "C-EUC0603K"))
    )
    (comp (ref "C81")
      (value "100nF")
      (footprint "eagle-import:C0603K")
      (libsource (lib "eagle-import") (part "C-EUC0603K"))
    )
    (comp (ref "C82")
      (value "100nF")
      (footprint "eagle-import:C0603K")
      (libsource (lib "eagle-import") (part "C-EUC0603K"))
    )
    (comp (ref "C83")
      (value "100nF")
      (footprint "eagle-import:C0603K")
      (libsource (lib "eagle-import") (part "C-EUC0603K"))
    )
    (comp (ref "C84")
      (value "100nF")
      (footprint "eagle-import:C0603K")
      (libsource (lib "eagle-import") (part "C-EUC0603K"))
    )
    (comp (ref "C85")
      (value "100nF")
      (footprint "eagle-import:C0603K")
      (libsource (lib "eagle-import") (part "C-EUC0603K"))
    )
    (comp (ref "C86")
      (value "100nF")
      (footprint "eagle-import:C0603K")
      (libsource (lib "eagle-import") (part "C-EUC0603K"))
    )
    (comp (ref "C87")
      (value "100nF")
      (footprint "eagle-import:C0603K")
      (libsource (lib "eagle-import") (part "C-EUC0603K"))
    )
    (comp (ref "C88")
      (value "100nF")
      (footprint "eagle-import:C0603K")
      (libsource (lib "eagle-import") (part "C-EUC0603K"))
    )
    (comp (ref "C89")
      (value "100nF")
      (footprint "eagle-import:C0603K")
      (libsource (lib "eagle-import") (part "C-EUC0603K"))
    )
    (comp (ref "C90")
      (value "100nF")
      (footprint "eagle-import:C0603K")
      (libsource (lib "eagle-import") (part "C-EUC0603K"))
    )
    (comp (ref "C91")
      (value "100nF")
      (footprint "eagle-import:C0603K")
      (libsource (lib "eagle-import") (part "C-EUC0603K"))
    )
    (comp (ref "C92")
      (value "100nF")
      (footprint "eagle-import:C0603K")
      (libsource (lib "eagle-import") (part "C-EUC0603K"))
    )
    (comp (ref "C93")
      (value "100nF")
      (footprint "eagle-import:C0603K")
      (libsource (lib "eagle-import") (part "C-EUC0603K"))
    )
    (comp (ref "C94")
      (value "100nF")
      (footprint "eagle-import:C0603K")
      (libsource (lib "eagle-import") (part "C-EUC0603K"))
    )
    (comp (ref "C95")
      (value "100nF")
      (footprint "eagle-import:C0603K")
      (libsource (lib "eagle-import") (part "C-EUC0603K"))
    )
    (comp (ref "C96")
      (value "100nF")
      (footprint "eagle-import:C0603K")
      (libsource (lib "eagle-import") (part "C-EUC0603K"))
    )
    (comp (ref "C97")
      (value "100nF")
      (footprint "eagle-import:C0603K")
      (libsource (lib "eagle-import") (part "C-EUC0603K"))
    )
    (comp (ref "C98")
      (value "100nF")
      (footprint "eagle-import:C0603K")
      (libsource (lib "eagle-import") (part "C-EUC0603K"))
    )
    (comp (ref "C99")
      (value "100nF")
      (footprint "eagle-import:C0603K")
      (libsource (lib "eagle-import") (part "C-EUC0603K"))
    )
    (comp (ref "C100")
      (value "100nF")
      (footprint "eagle-import:C0603K")
      (libsource (lib "eagle-import") (part "C-EUC0603K"))
    )
    (comp (ref "C101")
      (value "100nF")
      (footprint "eagle-import:C0603K")
      (libsource (lib "eagle-import") (part "C-EUC0603K"))
    )
    (comp (ref "C102")
      (value "100nF")
      (footprint "eagle-import:C0603K")
      (libsource (lib "eagle-import") (part "C-EUC0603K"))
    )
    (comp (ref "C103")
      (value "100nF")
      (footprint "eagle-import:C0603K")
      (libsource (lib "eagle-import") (part "C-EUC0603K"))
    )
    (comp (ref "C104")
      (value "100nF")
      (footprint "eagle-import:C0603K")
      (libsource (lib "eagle-import") (part "C-EUC0603K"))
    )
    (comp (ref "C105")
      (value "100nF")
      (footprint "eagle-import:C0603K")
      (libsource (lib "eagle-import") (part "C-EUC0603K"))
    )
    (comp (ref "C106")
      (value "100nF")
      (footprint "eagle-import:C0603K")
      (libsource (lib "eagle-import") (part "C-EUC0603K"))
    )
    (comp (ref "C107")
      (value "100nF")
      (footprint "eagle-import:C0603K")
      (libsource (lib "eagle-import") (part "C-EUC0603K"))
    )
    (comp (ref "C108")
      (value "100nF")
      (footprint "eagle-import:C0603K")
      (libsource (lib "eagle-import") (part "C-EUC0603K"))
    )
    (comp (ref "C109")
      (value "100nF")
      (footprint "eagle-import:C0603K")
      (libsource (lib "eagle-import") (part "C-EUC0603K"))
    )
    (comp (ref "C110")
      (value "100nF")
      (footprint "eagle-import:C0603K")
      (libsource (lib "eagle-import") (part "C-EUC0603K"))
    )
    (comp (ref "C111")
      (value "100nF")
      (footprint "eagle-import:C0603K")
      (libsource (lib "eagle-import") (part "C-EUC0603K"))
    )
    (comp (ref "C112")
      (value "100nF")
      (footprint "eagle-import:C0603K")
      (libsource (lib "eagle-import") (part "C-EUC0603K"))
    )
    (comp (ref "C113")
      (value "100nF")
      (footprint "eagle-import:C0603K")
      (libsource (lib "eagle-import") (part "C-EUC0603K"))
    )
    (comp (ref "C114")
      (value "100nF")
      (footprint "eagle-import:C0603K")
      (libsource (lib "eagle-import") (part "C-EUC0603K"))
    )
    (comp (ref "C115")
      (value "100nF")
      (footprint "eagle-import:C0603K")
      (libsource (lib "eagle-import") (part "C-EUC0603K"))
    )
    (comp (ref "C116")
      (value "100nF")
      (footprint "eagle-import:C0603K")
      (libsource (lib "eagle-import") (part "C-EUC0603K"))
    )
    (comp (ref "C117")
      (value "100nF")
      (footprint "eagle-import:C0603K")
      (libsource (lib "eagle-import") (part "C-EUC0603K"))
    )
    (comp (ref "C118")
      (value "100nF")
      (footprint "eagle-import:C0603K")
      (libsource (lib "eagle-import") (part "C-EUC0603K"))
    )
    (comp (ref "C119")
      (value "100nF")
      (footprint "eagle-import:C0603K")
      (libsource (lib "eagle-import") (part "C-EUC0603K"))
    )
    (comp (ref "C120")
      (value "100nF")
      (footprint "eagle-import:C0603K")
      (libsource (lib "eagle-import") (part "C-EUC0603K"))
    )
    (comp (ref "C121")
      (value "100nF")
      (footprint "eagle-import:C0603K")
      (libsource (lib "eagle-import") (part "C-EUC0603K"))
    )
    (comp (ref "C122")
      (value "100nF")
      (footprint "eagle-import:C0603K")
      (libsource (lib "eagle-import") (part "C-EUC0603K"))
    )
    (comp (ref "C123")
      (value "100nF")
      (footprint "eagle-import:C0603K")
      (libsource (lib "eagle-import") (part "C-EUC0603K"))
    )
    (comp (ref "C124")
      (value "100nF")
      (footprint "eagle-import:C0603K")
      (libsource (lib "eagle-import") (part "C-EUC0603K"))
    )
    (comp (ref "C125")
      (value "100nF")
      (footprint "eagle-import:C0603K")
      (libsource (lib "eagle-import") (part "C-EUC0603K"))
    )
    (comp (ref "C126")
      (value "100nF")
      (footprint "eagle-import:C0603K")
      (libsource (lib "eagle-import") (part "C-EUC0603K"))
    )
    (comp (ref "C127")
      (value "100nF")
      (footprint "eagle-import:C0603K")
      (libsource (lib "eagle-import") (part "C-EUC0603K"))
    )
    (comp (ref "C128")
      (value "100nF")
      (footprint "eagle-import:C0603K")
      (libsource (lib "eagle-import") (part "C-EUC0603K"))
    )
    (comp (ref "C129")
      (value "100nF")
      (footprint "eagle-import:C0603K")
      (libsource (lib "eagle-import") (part "C-EUC0603K"))
    )
    (comp (ref "C130")
      (value "100nF")
      (footprint "eagle-import:C0603K")
      (libsource (lib "eagle-import") (part "C-EUC0603K"))
    )
    (comp (ref "C131")
      (value "100nF")
      (footprint "eagle-import:C0603K")
      (libsource (lib "eagle-import") (part "C-EUC0603K"))
    )
    (comp (ref "C132")
      (value "100nF")
      (footprint "eagle-import:C0603K")
      (libsource (lib "eagle-import") (part "C-EUC0603K"))
    )
    (comp (ref "C133")
      (value "100nF")
      (footprint "eagle-import:C0603K")
      (libsource (lib "eagle-import") (part "C-EUC0603K"))
    )
    (comp (ref "C134")
      (value "100nF")
      (footprint "eagle-import:C0603K")
      (libsource (lib "eagle-import") (part "C-EUC0603K"))
    )
    (comp (ref "C135")
      (value "100nF")
      (footprint "eagle-import:C0603K")
      (libsource (lib "eagle-import") (part "C-EUC0603K"))
    )
    (comp (ref "C136")
      (value "100nF")
      (footprint "eagle-import:C0603K")
      (libsource (lib "eagle-import") (part "C-EUC0603K"))
    )
    (comp (ref "C137")
      (value "100nF")
      (footprint "eagle-import:C0603K")
      (libsource (lib "eagle-import") (part "C-EUC0603K"))
    )
    (comp (ref "C138")
      (value "100nF")
      (footprint "eagle-import:C0603K")
      (libsource (lib "eagle-import") (part "C-EUC0603K"))
    )
    (comp (ref "C139")
      (value "100nF")
      (footprint "eagle-import:C0603K")
      (libsource (lib "eagle-import") (part "C-EUC0603K"))
    )
    (comp (ref "C140")
      (value "100nF")
      (footprint "eagle-import:C0603K")
      (libsource (lib "eagle-import") (part "C-EUC0603K"))
    )
    (comp (ref "C141")
      (value "100nF")
      (footprint "eagle-import:C0603K")
      (libsource (lib "eagle-import") (part "C-EUC0603K"))
    )
    (comp (ref "C142")
      (value "100nF")
      (footprint "eagle-import:C0603K")
      (libsource (lib "eagle-import") (part "C-EUC0603K"))
    )
    (comp (ref "C143")
      (value "100nF")
      (footprint "eagle-import:C0603K")
      (libsource (lib "eagle-import") (part "C-EUC0603K"))
    )
    (comp (ref "C144")
      (value "100nF")
      (footprint "eagle-import:C0603K")
      (libsource (lib "eagle-import") (part "C-EUC0603K"))
    )
    (comp (ref "C145")
      (value "100nF")
      (footprint "eagle-import:C0603K")
      (libsource (lib "eagle-import") (part "C-EUC0603K"))
    )
    (comp (ref "C146")
      (value "100nF")
      (footprint "eagle-import:C0603K")
      (libsource (lib "eagle-import") (part "C-EUC0603K"))
    )
    (comp (ref "C147")
      (value "100nF")
      (footprint "eagle-import:C0603K")
      (libsource (lib "eagle-import") (part "C-EUC0603K"))
    )
    (comp (ref "C148")
      (value "100nF")
      (footprint "eagle-import:C0603K")
      (libsource (lib "eagle-import") (part "C-EUC0603K"))
    )
    (comp (ref "C149")
      (value "100nF")
      (footprint "eagle-import:C0603K")
      (libsource (lib "eagle-import") (part "C-EUC0603K"))
    )
    (comp (ref "C150")
      (value "100nF")
      (footprint "eagle-import:C0603K")
      (libsource (lib "eagle-import") (part "C-EUC0603K"))
    )
    (comp (ref "C151")
      (value "100nF")
      (footprint "eagle-import:C0603K")
      (libsource (lib "eagle-import") (part "C-EUC0603K"))
    )
    (comp (ref "C152")
      (value "100nF")
      (footprint "eagle-import:C0603K")
      (libsource (lib "eagle-import") (part "C-EUC0603K"))
    )
    (comp (ref "C153")
      (value "100nF")
      (footprint "eagle-import:C0603K")
      (libsource (lib "eagle-import") (part "C-EUC0603K"))
    )
    (comp (ref "C154")
      (value "100nF")
      (footprint "eagle-import:C0603K")
      (libsource (lib "eagle-import") (part "C-EUC0603K"))
    )
    (comp (ref "C155")
      (value "100nF")
      (footprint "eagle-import:C0603K")
      (libsource (lib "eagle-import") (part "C-EUC0603K"))
    )
    (comp (ref "C156")
      (value "100nF")
      (footprint "eagle-import:C0603K")
      (libsource (lib "eagle-import") (part "C-EUC0603K"))
    )
    (comp (ref "C157")
      (value "100nF")
      (footprint "eagle-import:C0603K")
      (libsource (lib "eagle-import") (part "C-EUC0603K"))
    )
    (comp (ref "C158")
      (value "100nF")
      (footprint "eagle-import:C0603K")
      (libsource (lib "eagle-import") (part "C-EUC0603K"))
    )
    (comp (ref "C159")
      (value "100nF")
      (footprint "eagle-import:C0603K")
      (libsource (lib "eagle-import") (part "C-EUC0603K"))
    )
    (comp (ref "C160")
      (value "100nF")
      (footprint "eagle-import:C0603K")
      (libsource (lib "eagle-import") (part "C-EUC0603K"))
    )
    (comp (ref "C161")
      (value "100nF")
      (footprint "eagle-import:C0603K")
      (libsource (lib "eagle-import") (part "C-EUC0603K"))
    )
    (comp (ref "C162")
      (value "100nF")
      (footprint "eagle-import:C0603K")
      (libsource (lib "eagle-import") (part "C-EUC0603K"))
    )
    (comp (ref "C163")
      (value "100nF")
      (footprint "eagle-import:C0603K")
      (libsource (lib "eagle-import") (part "C-EUC0603K"))
    )
    (comp (ref "C164")
      (value "100nF")
      (footprint "eagle-import:C0603K")
      (libsource (lib "eagle-import") (part "C-EUC0603K"))
    )
    (comp (ref "C165")
      (value "100nF")
      (footprint "eagle-import:C0603K")
      (libsource (lib "eagle-import") (part "C-EUC0603K"))
    )
    (comp (ref "C166")
      (value "100nF")
      (footprint "eagle-import:C0603K")
      (libsource (lib "eagle-import") (part "C-EUC0603K"))
    )
    (comp (ref "C167")
      (value "100nF")
      (footprint "eagle-import:C0603K")
      (libsource (lib "eagle-import") (part "C-EUC0603K"))
    )
    (comp (ref "C168")
      (value "100nF")
      (footprint "eagle-import:C0603K")
      (libsource (lib "eagle-import") (part "C-EUC0603K"))
    )
    (comp (ref "C169")
      (value "100nF")
      (footprint "eagle-import:C0603K")
      (libsource (lib "eagle-import") (part "C-EUC0603K"))
    )
    (comp (ref "D346")
      (value "WS2812_5050")
      (footprint "eagle-import:WS2812-5X5-4PIN")
      (libsource (lib "eagle-import") (part "led-rs_WS2812_5050"))
    )
    (comp (ref "D347")
      (value "WS2812_5050")
      (footprint "eagle-import:WS2812-5X5-4PIN")
      (libsource (lib "eagle-import") (part "led-rs_WS2812_5050"))
    )
    (comp (ref "D348")
      (value "WS2812_5050")
      (footprint "eagle-import:WS2812-5X5-4PIN")
      (libsource (lib "eagle-import") (part "led-rs_WS2812_5050"))
    )
    (comp (ref "D349")
      (value "WS2812_5050")
      (footprint "eagle-import:WS2812-5X5-4PIN")
      (libsource (lib "eagle-import") (part "led-rs_WS2812_5050"))
    )
    (comp (ref "D350")
      (value "WS2812_5050")
      (footprint "eagle-import:WS2812-5X5-4PIN")
      (libsource (lib "eagle-import") (part "led-rs_WS2812_5050"))
    )
    (comp (ref "D351")
      (value "WS2812_5050")
      (footprint "eagle-import:WS2812-5X5-4PIN")
      (libsource (lib "eagle-import") (part "led-rs_WS2812_5050"))
    )
    (comp (ref "D352")
      (value "WS2812_5050")
      (footprint "eagle-import:WS2812-5X5-4PIN")
      (libsource (lib "eagle-import") (part "led-rs_WS2812_5050"))
    )
    (comp (ref "D353")
      (value "WS2812_5050")
      (footprint "eagle-import:WS2812-5X5-4PIN")
      (libsource (lib "eagle-import") (part "led-rs_WS2812_5050"))
    )
    (comp (ref "D354")
      (value "WS2812_5050")
      (footprint "eagle-import:WS2812-5X5-4PIN")
      (libsource (lib "eagle-import") (part "led-rs_WS2812_5050"))
    )
    (comp (ref "D355")
      (value "WS2812_5050")
      (footprint "eagle-import:WS2812-5X5-4PIN")
      (libsource (lib "eagle-import") (part "led-rs_WS2812_5050"))
    )
    (comp (ref "D356")
      (value "WS2812_5050")
      (footprint "eagle-import:WS2812-5X5-4PIN")
      (libsource (lib "eagle-import") (part "led-rs_WS2812_5050"))
    )
    (comp (ref "D357")
      (value "WS2812_5050")
      (footprint "eagle-import:WS2812-5X5-4PIN")
      (libsource (lib "eagle-import") (part "led-rs_WS2812_5050"))
    )
    (comp (ref "D358")
      (value "WS2812_5050")
      (footprint "eagle-import:WS2812-5X5-4PIN")
      (libsource (lib "eagle-import") (part "led-rs_WS2812_5050"))
    )
    (comp (ref "D359")
      (value "WS2812_5050")
      (footprint "eagle-import:WS2812-5X5-4PIN")
      (libsource (lib "eagle-import") (part "led-rs_WS2812_5050"))
    )
    (comp (ref "D360")
      (value "WS2812_5050")
      (footprint "eagle-import:WS2812-5X5-4PIN")
      (libsource (lib "eagle-import") (part "led-rs_WS2812_5050"))
    )
    (comp (ref "D361")
      (value "WS2812_5050")
      (footprint "eagle-import:WS2812-5X5-4PIN")
      (libsource (lib "eagle-import") (part "led-rs_WS2812_5050"))
    )
    (comp (ref "D362")
      (value "WS2812_5050")
      (footprint "eagle-import:WS2812-5X5-4PIN")
      (libsource (lib "eagle-import") (part "led-rs_WS2812_5050"))
    )
    (comp (ref "D363")
      (value "WS2812_5050")
      (footprint "eagle-import:WS2812-5X5-4PIN")
      (libsource (lib "eagle-import") (part "led-rs_WS2812_5050"))
    )
    (comp (ref "D364")
      (value "WS2812_5050")
      (footprint "eagle-import:WS2812-5X5-4PIN")
      (libsource (lib "eagle-import") (part "led-rs_WS2812_5050"))
    )
    (comp (ref "D365")
      (value "WS2812_5050")
      (footprint "eagle-import:WS2812-5X5-4PIN")
      (libsource (lib "eagle-import") (part "led-rs_WS2812_5050"))
    )
    (comp (ref "D366")
      (value "WS2812_5050")
      (footprint "eagle-import:WS2812-5X5-4PIN")
      (libsource (lib "eagle-import") (part "led-rs_WS2812_5050"))
    )
    (comp (ref "D367")
      (value "WS2812_5050")
      (footprint "eagle-import:WS2812-5X5-4PIN")
      (libsource (lib "eagle-import") (part "led-rs_WS2812_5050"))
    )
    (comp (ref "D368")
      (value "WS2812_5050")
      (footprint "eagle-import:WS2812-5X5-4PIN")
      (libsource (lib "eagle-import") (part "led-rs_WS2812_5050"))
    )
    (comp (ref "D369")
      (value "WS2812_5050")
      (footprint "eagle-import:WS2812-5X5-4PIN")
      (libsource (lib "eagle-import") (part "led-rs_WS2812_5050"))
    )
    (comp (ref "D370")
      (value "WS2812_5050")
      (footprint "eagle-import:WS2812-5X5-4PIN")
      (libsource (lib "eagle-import") (part "led-rs_WS2812_5050"))
    )
    (comp (ref "D371")
      (value "WS2812_5050")
      (footprint "eagle-import:WS2812-5X5-4PIN")
      (libsource (lib "eagle-import") (part "led-rs_WS2812_5050"))
    )
    (comp (ref "D372")
      (value "WS2812_5050")
      (footprint "eagle-import:WS2812-5X5-4PIN")
      (libsource (lib "eagle-import") (part "led-rs_WS2812_5050"))
    )
    (comp (ref "D373")
      (value "WS2812_5050")
      (footprint "eagle-import:WS2812-5X5-4PIN")
      (libsource (lib "eagle-import") (part "led-rs_WS2812_5050"))
    )
    (comp (ref "D374")
      (value "WS2812_5050")
      (footprint "eagle-import:WS2812-5X5-4PIN")
      (libsource (lib "eagle-import") (part "led-rs_WS2812_5050"))
    )
    (comp (ref "D375")
      (value "WS2812_5050")
      (footprint "eagle-import:WS2812-5X5-4PIN")
      (libsource (lib "eagle-import") (part "led-rs_WS2812_5050"))
    )
    (comp (ref "D376")
      (value "WS2812_5050")
      (footprint "eagle-import:WS2812-5X5-4PIN")
      (libsource (lib "eagle-import") (part "led-rs_WS2812_5050"))
    )
    (comp (ref "D377")
      (value "WS2812_5050")
      (footprint "eagle-import:WS2812-5X5-4PIN")
      (libsource (lib "eagle-import") (part "led-rs_WS2812_5050"))
    )
    (comp (ref "D378")
      (value "WS2812_5050")
      (footprint "eagle-import:WS2812-5X5-4PIN")
      (libsource (lib "eagle-import") (part "led-rs_WS2812_5050"))
    )
    (comp (ref "D379")
      (value "WS2812_5050")
      (footprint "eagle-import:WS2812-5X5-4PIN")
      (libsource (lib "eagle-import") (part "led-rs_WS2812_5050"))
    )
    (comp (ref "D380")
      (value "WS2812_5050")
      (footprint "eagle-import:WS2812-5X5-4PIN")
      (libsource (lib "eagle-import") (part "led-rs_WS2812_5050"))
    )
    (comp (ref "D381")
      (value "WS2812_5050")
      (footprint "eagle-import:WS2812-5X5-4PIN")
      (libsource (lib "eagle-import") (part "led-rs_WS2812_5050"))
    )
    (comp (ref "D382")
      (value "WS2812_5050")
      (footprint "eagle-import:WS2812-5X5-4PIN")
      (libsource (lib "eagle-import") (part "led-rs_WS2812_5050"))
    )
    (comp (ref "D383")
      (value "WS2812_5050")
      (footprint "eagle-import:WS2812-5X5-4PIN")
      (libsource (lib "eagle-import") (part "led-rs_WS2812_5050"))
    )
    (comp (ref "D384")
      (value "WS2812_5050")
      (footprint "eagle-import:WS2812-5X5-4PIN")
      (libsource (lib "eagle-import") (part "led-rs_WS2812_5050"))
    )
    (comp (ref "D385")
      (value "WS2812_5050")
      (footprint "eagle-import:WS2812-5X5-4PIN")
      (libsource (lib "eagle-import") (part "led-rs_WS2812_5050"))
    )
    (comp (ref "D386")
      (value "WS2812_5050")
      (footprint "eagle-import:WS2812-5X5-4PIN")
      (libsource (lib "eagle-import") (part "led-rs_WS2812_5050"))
    )
    (comp (ref "D387")
      (value "WS2812_5050")
      (footprint "eagle-import:WS2812-5X5-4PIN")
      (libsource (lib "eagle-import") (part "led-rs_WS2812_5050"))
    )
    (comp (ref "D388")
      (value "WS2812_5050")
      (footprint "eagle-import:WS2812-5X5-4PIN")
      (libsource (lib "eagle-import") (part "led-rs_WS2812_5050"))
    )
    (comp (ref "D389")
      (value "WS2812_5050")
      (footprint "eagle-import:WS2812-5X5-4PIN")
      (libsource (lib "eagle-import") (part "led-rs_WS2812_5050"))
    )
    (comp (ref "D390")
      (value "WS2812_5050")
      (footprint "eagle-import:WS2812-5X5-4PIN")
      (libsource (lib "eagle-import") (part "led-rs_WS2812_5050"))
    )
    (comp (ref "D391")
      (value "WS2812_5050")
      (footprint "eagle-import:WS2812-5X5-4PIN")
      (libsource (lib "eagle-import") (part "led-rs_WS2812_5050"))
    )
    (comp (ref "D392")
      (value "WS2812_5050")
      (footprint "eagle-import:WS2812-5X5-4PIN")
      (libsource (lib "eagle-import") (part "led-rs_WS2812_5050"))
    )
    (comp (ref "D393")
      (value "WS2812_5050")
      (footprint "eagle-import:WS2812-5X5-4PIN")
      (libsource (lib "eagle-import") (part "led-rs_WS2812_5050"))
    )
    (comp (ref "D394")
      (value "WS2812_5050")
      (footprint "eagle-import:WS2812-5X5-4PIN")
      (libsource (lib "eagle-import") (part "led-rs_WS2812_5050"))
    )
    (comp (ref "D395")
      (value "WS2812_5050")
      (footprint "eagle-import:WS2812-5X5-4PIN")
      (libsource (lib "eagle-import") (part "led-rs_WS2812_5050"))
    )
    (comp (ref "D396")
      (value "WS2812_5050")
      (footprint "eagle-import:WS2812-5X5-4PIN")
      (libsource (lib "eagle-import") (part "led-rs_WS2812_5050"))
    )
    (comp (ref "D397")
      (value "WS2812_5050")
      (footprint "eagle-import:WS2812-5X5-4PIN")
      (libsource (lib "eagle-import") (part "led-rs_WS2812_5050"))
    )
    (comp (ref "D398")
      (value "WS2812_5050")
      (footprint "eagle-import:WS2812-5X5-4PIN")
      (libsource (lib "eagle-import") (part "led-rs_WS2812_5050"))
    )
    (comp (ref "D399")
      (value "WS2812_5050")
      (footprint "eagle-import:WS2812-5X5-4PIN")
      (libsource (lib "eagle-import") (part "led-rs_WS2812_5050"))
    )
    (comp (ref "D400")
      (value "WS2812_5050")
      (footprint "eagle-import:WS2812-5X5-4PIN")
      (libsource (lib "eagle-import") (part "led-rs_WS2812_5050"))
    )
    (comp (ref "D401")
      (value "WS2812_5050")
      (footprint "eagle-import:WS2812-5X5-4PIN")
      (libsource (lib "eagle-import") (part "led-rs_WS2812_5050"))
    )
    (comp (ref "D402")
      (value "WS2812_5050")
      (footprint "eagle-import:WS2812-5X5-4PIN")
      (libsource (lib "eagle-import") (part "led-rs_WS2812_5050"))
    )
    (comp (ref "D403")
      (value "WS2812_5050")
      (footprint "eagle-import:WS2812-5X5-4PIN")
      (libsource (lib "eagle-import") (part "led-rs_WS2812_5050"))
    )
    (comp (ref "D404")
      (value "WS2812_5050")
      (footprint "eagle-import:WS2812-5X5-4PIN")
      (libsource (lib "eagle-import") (part "led-rs_WS2812_5050"))
    )
    (comp (ref "D405")
      (value "WS2812_5050")
      (footprint "eagle-import:WS2812-5X5-4PIN")
      (libsource (lib "eagle-import") (part "led-rs_WS2812_5050"))
    )
    (comp (ref "JP1")
      (value "70543-07")
      (footprint "eagle-import:70543-07")
      (libsource (lib "eagle-import") (part "70543-07"))
    )
    (comp (ref "JP2")
      (value "70543-07")
      (footprint "eagle-import:70543-07")
      (libsource (lib "eagle-import") (part "70543-07"))
    )
    (comp (ref "R1")
      (value "390R")
      (footprint "eagle-import:R0805")
      (libsource (lib "eagle-import") (part "R-EUR0805"))
    )
    (comp (ref "U2")
      (value "FIDUCIAL")
      (footprint "eagle-import:FIDUCIAL_1MM")
      (libsource (lib "eagle-import") (part "FIDUCIAL"))
    )
    (comp (ref "U4")
      (value "FIDUCIAL")
      (footprint "eagle-import:FIDUCIAL_1MM")
      (libsource (lib "eagle-import") (part "FIDUCIAL"))
    )
    (comp (ref "Z1")
      (value "SMAJ6.0CA")
      (footprint "eagle-import:DO214AC")
      (libsource (lib "eagle-import") (part "SMAJCA6.0"))
    )
  )
  (nets
    (net (code "1") (name "DI") (class "Default")
      (node (ref "D405") (pin "DI") (pinfunction "DI_DI") (pintype "input"))
      (node (ref "R1") (pin "2") (pinfunction "2_2") (pintype "passive"))
    )
    (net (code "2") (name "DO2") (class "Default")
      (node (ref "D1") (pin "DI") (pinfunction "DI_DI") (pintype "input"))
      (node (ref "D2") (pin "DO") (pinfunction "DO_DO") (pintype "output"))
    )
    (net (code "3") (name "DO3") (class "Default")
      (node (ref "D2") (pin "DI") (pinfunction "DI_DI") (pintype "input"))
      (node (ref "D3") (pin "DO") (pinfunction "DO_DO") (pintype "output"))
    )
    (net (code "4") (name "DO4") (class "Default")
      (node (ref "D3") (pin "DI") (pinfunction "DI_DI") (pintype "input"))
      (node (ref "D4") (pin "DO") (pinfunction "DO_DO") (pintype "output"))
    )
    (net (code "5") (name "DO5") (class "Default")
      (node (ref "D4") (pin "DI") (pinfunction "DI_DI") (pintype "input"))
      (node (ref "D5") (pin "DO") (pinfunction "DO_DO") (pintype "output"))
    )
    (net (code "6") (name "DO6") (class "Default")
      (node (ref "D5") (pin "DI") (pinfunction "DI_DI") (pintype "input"))
      (node (ref "D6") (pin "DO") (pinfunction "DO_DO") (pintype "output"))
    )
    (net (code "7") (name "DO7") (class "Default")
      (node (ref "D6") (pin "DI") (pinfunction "DI_DI") (pintype "input"))
      (node (ref "D7") (pin "DO") (pinfunction "DO_DO") (pintype "output"))
    )
    (net (code "8") (name "DO8") (class "Default")
      (node (ref "D7") (pin "DI") (pinfunction "DI_DI") (pintype "input"))
      (node (ref "D8") (pin "DO") (pinfunction "DO_DO") (pintype "output"))
    )
    (net (code "9") (name "DO9") (class "Default")
      (node (ref "D8") (pin "DI") (pinfunction "DI_DI") (pintype "input"))
      (node (ref "D9") (pin "DO") (pinfunction "DO_DO") (pintype "output"))
    )
    (net (code "10") (name "DO10") (class "Default")
      (node (ref "D10") (pin "DO") (pinfunction "DO_DO") (pintype "output"))
      (node (ref "D9") (pin "DI") (pinfunction "DI_DI") (pintype "input"))
    )
    (net (code "11") (name "DO11") (class "Default")
      (node (ref "D10") (pin "DI") (pinfunction "DI_DI") (pintype "input"))
      (node (ref "D11") (pin "DO") (pinfunction "DO_DO") (pintype "output"))
    )
    (net (code "12") (name "DO12") (class "Default")
      (node (ref "D11") (pin "DI") (pinfunction "DI_DI") (pintype "input"))
      (node (ref "D12") (pin "DO") (pinfunction "DO_DO") (pintype "output"))
    )
    (net (code "13") (name "DO13") (class "Default")
      (node (ref "D12") (pin "DI") (pinfunction "DI_DI") (pintype "input"))
      (node (ref "D13") (pin "DO") (pinfunction "DO_DO") (pintype "output"))
    )
    (net (code "14") (name "DO14") (class "Default")
      (node (ref "D13") (pin "DI") (pinfunction "DI_DI") (pintype "input"))
      (node (ref "D14") (pin "DO") (pinfunction "DO_DO") (pintype "output"))
    )
    (net (code "15") (name "DO15") (class "Default")
      (node (ref "D14") (pin "DI") (pinfunction "DI_DI") (pintype "input"))
      (node (ref "D15") (pin "DO") (pinfunction "DO_DO") (pintype "output"))
    )
    (net (code "16") (name "DO16") (class "Default")
      (node (ref "D15") (pin "DI") (pinfunction "DI_DI") (pintype "input"))
      (node (ref "D16") (pin "DO") (pinfunction "DO_DO") (pintype "output"))
    )
    (net (code "17") (name "DO17") (class "Default")
      (node (ref "D16") (pin "DI") (pinfunction "DI_DI") (pintype "input"))
      (node (ref "D17") (pin "DO") (pinfunction "DO_DO") (pintype "output"))
    )
    (net (code "18") (name "DO18") (class "Default")
      (node (ref "D17") (pin "DI") (pinfunction "DI_DI") (pintype "input"))
      (node (ref "D18") (pin "DO") (pinfunction "DO_DO") (pintype "output"))
    )
    (net (code "19") (name "DO19") (class "Default")
      (node (ref "D18") (pin "DI") (pinfunction "DI_DI") (pintype "input"))
      (node (ref "D19") (pin "DO") (pinfunction "DO_DO") (pintype "output"))
    )
    (net (code "20") (name "DO20") (class "Default")
      (node (ref "D19") (pin "DI") (pinfunction "DI_DI") (pintype "input"))
      (node (ref "D20") (pin "DO") (pinfunction "DO_DO") (pintype "output"))
    )
    (net (code "21") (name "DO21") (class "Default")
      (node (ref "D20") (pin "DI") (pinfunction "DI_DI") (pintype "input"))
      (node (ref "D21") (pin "DO") (pinfunction "DO_DO") (pintype "output"))
    )
    (net (code "22") (name "DO22") (class "Default")
      (node (ref "D21") (pin "DI") (pinfunction "DI_DI") (pintype "input"))
      (node (ref "D22") (pin "DO") (pinfunction "DO_DO") (pintype "output"))
    )
    (net (code "23") (name "DO23") (class "Default")
      (node (ref "D22") (pin "DI") (pinfunction "DI_DI") (pintype "input"))
      (node (ref "D23") (pin "DO") (pinfunction "DO_DO") (pintype "output"))
    )
    (net (code "24") (name "DO24") (class "Default")
      (node (ref "D23") (pin "DI") (pinfunction "DI_DI") (pintype "input"))
      (node (ref "D24") (pin "DO") (pinfunction "DO_DO") (pintype "output"))
    )
    (net (code "25") (name "DO25") (class "Default")
      (node (ref "D24") (pin "DI") (pinfunction "DI_DI") (pintype "input"))
      (node (ref "D25") (pin "DO") (pinfunction "DO_DO") (pintype "output"))
    )
    (net (code "26") (name "DO26") (class "Default")
      (node (ref "D25") (pin "DI") (pinfunction "DI_DI") (pintype "input"))
      (node (ref "D26") (pin "DO") (pinfunction "DO_DO") (pintype "output"))
    )
    (net (code "27") (name "DO27") (class "Default")
      (node (ref "D26") (pin "DI") (pinfunction "DI_DI") (pintype "input"))
      (node (ref "D27") (pin "DO") (pinfunction "DO_DO") (pintype "output"))
    )
    (net (code "28") (name "DO28") (class "Default")
      (node (ref "D27") (pin "DI") (pinfunction "DI_DI") (pintype "input"))
      (node (ref "D28") (pin "DO") (pinfunction "DO_DO") (pintype "output"))
    )
    (net (code "29") (name "DO29") (class "Default")
      (node (ref "D28") (pin "DI") (pinfunction "DI_DI") (pintype "input"))
      (node (ref "D29") (pin "DO") (pinfunction "DO_DO") (pintype "output"))
    )
    (net (code "30") (name "DO30") (class "Default")
      (node (ref "D29") (pin "DI") (pinfunction "DI_DI") (pintype "input"))
      (node (ref "D30") (pin "DO") (pinfunction "DO_DO") (pintype "output"))
    )
    (net (code "31") (name "DO31") (class "Default")
      (node (ref "D30") (pin "DI") (pinfunction "DI_DI") (pintype "input"))
      (node (ref "D31") (pin "DO") (pinfunction "DO_DO") (pintype "output"))
    )
    (net (code "32") (name "DO32") (class "Default")
      (node (ref "D31") (pin "DI") (pinfunction "DI_DI") (pintype "input"))
      (node (ref "D32") (pin "DO") (pinfunction "DO_DO") (pintype "output"))
    )
    (net (code "33") (name "DO33") (class "Default")
      (node (ref "D32") (pin "DI") (pinfunction "DI_DI") (pintype "input"))
      (node (ref "D33") (pin "DO") (pinfunction "DO_DO") (pintype "output"))
    )
    (net (code "34") (name "DO34") (class "Default")
      (node (ref "D33") (pin "DI") (pinfunction "DI_DI") (pintype "input"))
      (node (ref "D34") (pin "DO") (pinfunction "DO_DO") (pintype "output"))
    )
    (net (code "35") (name "DO35") (class "Default")
      (node (ref "D34") (pin "DI") (pinfunction "DI_DI") (pintype "input"))
      (node (ref "D35") (pin "DO") (pinfunction "DO_DO") (pintype "output"))
    )
    (net (code "36") (name "DO36") (class "Default")
      (node (ref "D35") (pin "DI") (pinfunction "DI_DI") (pintype "input"))
      (node (ref "D36") (pin "DO") (pinfunction "DO_DO") (pintype "output"))
    )
    (net (code "37") (name "DO37") (class "Default")
      (node (ref "D36") (pin "DI") (pinfunction "DI_DI") (pintype "input"))
      (node (ref "D37") (pin "DO") (pinfunction "DO_DO") (pintype "output"))
    )
    (net (code "38") (name "DO38") (class "Default")
      (node (ref "D37") (pin "DI") (pinfunction "DI_DI") (pintype "input"))
      (node (ref "D38") (pin "DO") (pinfunction "DO_DO") (pintype "output"))
    )
    (net (code "39") (name "DO39") (class "Default")
      (node (ref "D38") (pin "DI") (pinfunction "DI_DI") (pintype "input"))
      (node (ref "D39") (pin "DO") (pinfunction "DO_DO") (pintype "output"))
    )
    (net (code "40") (name "DO40") (class "Default")
      (node (ref "D39") (pin "DI") (pinfunction "DI_DI") (pintype "input"))
      (node (ref "D40") (pin "DO") (pinfunction "DO_DO") (pintype "output"))
    )
    (net (code "41") (name "DO41") (class "Default")
      (node (ref "D40") (pin "DI") (pinfunction "DI_DI") (pintype "input"))
      (node (ref "D41") (pin "DO") (pinfunction "DO_DO") (pintype "output"))
    )
    (net (code "42") (name "DO42") (class "Default")
      (node (ref "D41") (pin "DI") (pinfunction "DI_DI") (pintype "input"))
      (node (ref "D42") (pin "DO") (pinfunction "DO_DO") (pintype "output"))
    )
    (net (code "43") (name "DO43") (class "Default")
      (node (ref "D42") (pin "DI") (pinfunction "DI_DI") (pintype "input"))
      (node (ref "D43") (pin "DO") (pinfunction "DO_DO") (pintype "output"))
    )
    (net (code "44") (name "DO44") (class "Default")
      (node (ref "D43") (pin "DI") (pinfunction "DI_DI") (pintype "input"))
      (node (ref "D44") (pin "DO") (pinfunction "DO_DO") (pintype "output"))
    )
    (net (code "45") (name "DO45") (class "Default")
      (node (ref "D44") (pin "DI") (pinfunction "DI_DI") (pintype "input"))
      (node (ref "D45") (pin "DO") (pinfunction "DO_DO") (pintype "output"))
    )
    (net (code "46") (name "DO46") (class "Default")
      (node (ref "D45") (pin "DI") (pinfunction "DI_DI") (pintype "input"))
      (node (ref "D46") (pin "DO") (pinfunction "DO_DO") (pintype "output"))
    )
    (net (code "47") (name "DO47") (class "Default")
      (node (ref "D46") (pin "DI") (pinfunction "DI_DI") (pintype "input"))
      (node (ref "D47") (pin "DO") (pinfunction "DO_DO") (pintype "output"))
    )
    (net (code "48") (name "DO48") (class "Default")
      (node (ref "D47") (pin "DI") (pinfunction "DI_DI") (pintype "input"))
      (node (ref "D48") (pin "DO") (pinfunction "DO_DO") (pintype "output"))
    )
    (net (code "49") (name "DO49") (class "Default")
      (node (ref "D48") (pin "DI") (pinfunction "DI_DI") (pintype "input"))
      (node (ref "D49") (pin "DO") (pinfunction "DO_DO") (pintype "output"))
    )
    (net (code "50") (name "DO50") (class "Default")
      (node (ref "D49") (pin "DI") (pinfunction "DI_DI") (pintype "input"))
      (node (ref "D50") (pin "DO") (pinfunction "DO_DO") (pintype "output"))
    )
    (net (code "51") (name "DO51") (class "Default")
      (node (ref "D50") (pin "DI") (pinfunction "DI_DI") (pintype "input"))
      (node (ref "D51") (pin "DO") (pinfunction "DO_DO") (pintype "output"))
    )
    (net (code "52") (name "DO52") (class "Default")
      (node (ref "D51") (pin "DI") (pinfunction "DI_DI") (pintype "input"))
      (node (ref "D52") (pin "DO") (pinfunction "DO_DO") (pintype "output"))
    )
    (net (code "53") (name "DO53") (class "Default")
      (node (ref "D52") (pin "DI") (pinfunction "DI_DI") (pintype "input"))
      (node (ref "D53") (pin "DO") (pinfunction "DO_DO") (pintype "output"))
    )
    (net (code "54") (name "DO54") (class "Default")
      (node (ref "D53") (pin "DI") (pinfunction "DI_DI") (pintype "input"))
      (node (ref "D54") (pin "DO") (pinfunction "DO_DO") (pintype "output"))
    )
    (net (code "55") (name "DO55") (class "Default")
      (node (ref "D54") (pin "DI") (pinfunction "DI_DI") (pintype "input"))
      (node (ref "D55") (pin "DO") (pinfunction "DO_DO") (pintype "output"))
    )
    (net (code "56") (name "DO56") (class "Default")
      (node (ref "D55") (pin "DI") (pinfunction "DI_DI") (pintype "input"))
      (node (ref "D56") (pin "DO") (pinfunction "DO_DO") (pintype "output"))
    )
    (net (code "57") (name "DO57") (class "Default")
      (node (ref "D56") (pin "DI") (pinfunction "DI_DI") (pintype "input"))
      (node (ref "D57") (pin "DO") (pinfunction "DO_DO") (pintype "output"))
    )
    (net (code "58") (name "DO58") (class "Default")
      (node (ref "D57") (pin "DI") (pinfunction "DI_DI") (pintype "input"))
      (node (ref "D58") (pin "DO") (pinfunction "DO_DO") (pintype "output"))
    )
    (net (code "59") (name "DO59") (class "Default")
      (node (ref "D58") (pin "DI") (pinfunction "DI_DI") (pintype "input"))
      (node (ref "D59") (pin "DO") (pinfunction "DO_DO") (pintype "output"))
    )
    (net (code "60") (name "DO60") (class "Default")
      (node (ref "D59") (pin "DI") (pinfunction "DI_DI") (pintype "input"))
      (node (ref "D60") (pin "DO") (pinfunction "DO_DO") (pintype "output"))
    )
    (net (code "61") (name "DO61") (class "Default")
      (node (ref "D60") (pin "DI") (pinfunction "DI_DI") (pintype "input"))
      (node (ref "D61") (pin "DO") (pinfunction "DO_DO") (pintype "output"))
    )
    (net (code "62") (name "DO62") (class "Default")
      (node (ref "D61") (pin "DI") (pinfunction "DI_DI") (pintype "input"))
      (node (ref "D62") (pin "DO") (pinfunction "DO_DO") (pintype "output"))
    )
    (net (code "63") (name "DO63") (class "Default")
      (node (ref "D62") (pin "DI") (pinfunction "DI_DI") (pintype "input"))
      (node (ref "D63") (pin "DO") (pinfunction "DO_DO") (pintype "output"))
    )
    (net (code "64") (name "DO64") (class "Default")
      (node (ref "D63") (pin "DI") (pinfunction "DI_DI") (pintype "input"))
      (node (ref "D64") (pin "DO") (pinfunction "DO_DO") (pintype "output"))
    )
    (net (code "65") (name "DO65") (class "Default")
      (node (ref "D64") (pin "DI") (pinfunction "DI_DI") (pintype "input"))
      (node (ref "D65") (pin "DO") (pinfunction "DO_DO") (pintype "output"))
    )
    (net (code "66") (name "DO66") (class "Default")
      (node (ref "D65") (pin "DI") (pinfunction "DI_DI") (pintype "input"))
      (node (ref "D66") (pin "DO") (pinfunction "DO_DO") (pintype "output"))
    )
    (net (code "67") (name "DO67") (class "Default")
      (node (ref "D66") (pin "DI") (pinfunction "DI_DI") (pintype "input"))
      (node (ref "D67") (pin "DO") (pinfunction "DO_DO") (pintype "output"))
    )
    (net (code "68") (name "DO68") (class "Default")
      (node (ref "D67") (pin "DI") (pinfunction "DI_DI") (pintype "input"))
      (node (ref "D68") (pin "DO") (pinfunction "DO_DO") (pintype "output"))
    )
    (net (code "69") (name "DO69") (class "Default")
      (node (ref "D68") (pin "DI") (pinfunction "DI_DI") (pintype "input"))
      (node (ref "D69") (pin "DO") (pinfunction "DO_DO") (pintype "output"))
    )
    (net (code "70") (name "DO70") (class "Default")
      (node (ref "D69") (pin "DI") (pinfunction "DI_DI") (pintype "input"))
      (node (ref "D70") (pin "DO") (pinfunction "DO_DO") (pintype "output"))
    )
    (net (code "71") (name "DO71") (class "Default")
      (node (ref "D70") (pin "DI") (pinfunction "DI_DI") (pintype "input"))
      (node (ref "D71") (pin "DO") (pinfunction "DO_DO") (pintype "output"))
    )
    (net (code "72") (name "DO72") (class "Default")
      (node (ref "D71") (pin "DI") (pinfunction "DI_DI") (pintype "input"))
      (node (ref "D72") (pin "DO") (pinfunction "DO_DO") (pintype "output"))
    )
    (net (code "73") (name "DO73") (class "Default")
      (node (ref "D72") (pin "DI") (pinfunction "DI_DI") (pintype "input"))
      (node (ref "D73") (pin "DO") (pinfunction "DO_DO") (pintype "output"))
    )
    (net (code "74") (name "DO74") (class "Default")
      (node (ref "D73") (pin "DI") (pinfunction "DI_DI") (pintype "input"))
      (node (ref "D74") (pin "DO") (pinfunction "DO_DO") (pintype "output"))
    )
    (net (code "75") (name "DO75") (class "Default")
      (node (ref "D74") (pin "DI") (pinfunction "DI_DI") (pintype "input"))
      (node (ref "D75") (pin "DO") (pinfunction "DO_DO") (pintype "output"))
    )
    (net (code "76") (name "DO76") (class "Default")
      (node (ref "D75") (pin "DI") (pinfunction "DI_DI") (pintype "input"))
      (node (ref "D76") (pin "DO") (pinfunction "DO_DO") (pintype "output"))
    )
    (net (code "77") (name "DO91") (class "Default")
      (node (ref "D90") (pin "DI") (pinfunction "DI_DI") (pintype "input"))
      (node (ref "D91") (pin "DO") (pinfunction "DO_DO") (pintype "output"))
    )
    (net (code "78") (name "DO106") (class "Default")
      (node (ref "D105") (pin "DI") (pinfunction "DI_DI") (pintype "input"))
      (node (ref "D106") (pin "DO") (pinfunction "DO_DO") (pintype "output"))
    )
    (net (code "79") (name "DO121") (class "Default")
      (node (ref "D120") (pin "DI") (pinfunction "DI_DI") (pintype "input"))
      (node (ref "D121") (pin "DO") (pinfunction "DO_DO") (pintype "output"))
    )
    (net (code "80") (name "DO136") (class "Default")
      (node (ref "D135") (pin "DI") (pinfunction "DI_DI") (pintype "input"))
      (node (ref "D136") (pin "DO") (pinfunction "DO_DO") (pintype "output"))
    )
    (net (code "81") (name "DO151") (class "Default")
      (node (ref "D150") (pin "DI") (pinfunction "DI_DI") (pintype "input"))
      (node (ref "D151") (pin "DO") (pinfunction "DO_DO") (pintype "output"))
    )
    (net (code "82") (name "DO166") (class "Default")
      (node (ref "D165") (pin "DI") (pinfunction "DI_DI") (pintype "input"))
      (node (ref "D166") (pin "DO") (pinfunction "DO_DO") (pintype "output"))
    )
    (net (code "83") (name "DO181") (class "Default")
      (node (ref "D180") (pin "DI") (pinfunction "DI_DI") (pintype "input"))
      (node (ref "D181") (pin "DO") (pinfunction "DO_DO") (pintype "output"))
    )
    (net (code "84") (name "DO196") (class "Default")
      (node (ref "D195") (pin "DI") (pinfunction "DI_DI") (pintype "input"))
      (node (ref "D196") (pin "DO") (pinfunction "DO_DO") (pintype "output"))
    )
    (net (code "85") (name "DO211") (class "Default")
      (node (ref "D210") (pin "DI") (pinfunction "DI_DI") (pintype "input"))
      (node (ref "D211") (pin "DO") (pinfunction "DO_DO") (pintype "output"))
    )
    (net (code "86") (name "DO226") (class "Default")
      (node (ref "D225") (pin "DI") (pinfunction "DI_DI") (pintype "input"))
      (node (ref "D226") (pin "DO") (pinfunction "DO_DO") (pintype "output"))
    )
    (net (code "87") (name "DO241") (class "Default")
      (node (ref "D240") (pin "DI") (pinfunction "DI_DI") (pintype "input"))
      (node (ref "D241") (pin "DO") (pinfunction "DO_DO") (pintype "output"))
    )
    (net (code "88") (name "DO256") (class "Default")
      (node (ref "D255") (pin "DI") (pinfunction "DI_DI") (pintype "input"))
      (node (ref "D256") (pin "DO") (pinfunction "DO_DO") (pintype "output"))
    )
    (net (code "89") (name "DO257") (class "Default")
      (node (ref "D256") (pin "DI") (pinfunction "DI_DI") (pintype "input"))
      (node (ref "D257") (pin "DO") (pinfunction "DO_DO") (pintype "output"))
    )
    (net (code "90") (name "DO258") (class "Default")
      (node (ref "D257") (pin "DI") (pinfunction "DI_DI") (pintype "input"))
      (node (ref "D258") (pin "DO") (pinfunction "DO_DO") (pintype "output"))
    )
    (net (code "91") (name "DO259") (class "Default")
      (node (ref "D258") (pin "DI") (pinfunction "DI_DI") (pintype "input"))
      (node (ref "D259") (pin "DO") (pinfunction "DO_DO") (pintype "output"))
    )
    (net (code "92") (name "DO260") (class "Default")
      (node (ref "D259") (pin "DI") (pinfunction "DI_DI") (pintype "input"))
      (node (ref "D260") (pin "DO") (pinfunction "DO_DO") (pintype "output"))
    )
    (net (code "93") (name "DO261") (class "Default")
      (node (ref "D260") (pin "DI") (pinfunction "DI_DI") (pintype "input"))
      (node (ref "D261") (pin "DO") (pinfunction "DO_DO") (pintype "output"))
    )
    (net (code "94") (name "DO262") (class "Default")
      (node (ref "D261") (pin "DI") (pinfunction "DI_DI") (pintype "input"))
      (node (ref "D262") (pin "DO") (pinfunction "DO_DO") (pintype "output"))
    )
    (net (code "95") (name "DO263") (class "Default")
      (node (ref "D262") (pin "DI") (pinfunction "DI_DI") (pintype "input"))
      (node (ref "D263") (pin "DO") (pinfunction "DO_DO") (pintype "output"))
    )
    (net (code "96") (name "DO264") (class "Default")
      (node (ref "D263") (pin "DI") (pinfunction "DI_DI") (pintype "input"))
      (node (ref "D264") (pin "DO") (pinfunction "DO_DO") (pintype "output"))
    )
    (net (code "97") (name "DO265") (class "Default")
      (node (ref "D264") (pin "DI") (pinfunction "DI_DI") (pintype "input"))
      (node (ref "D265") (pin "DO") (pinfunction "DO_DO") (pintype "output"))
    )
    (net (code "98") (name "DO266") (class "Default")
      (node (ref "D265") (pin "DI") (pinfunction "DI_DI") (pintype "input"))
      (node (ref "D266") (pin "DO") (pinfunction "DO_DO") (pintype "output"))
    )
    (net (code "99") (name "DO267") (class "Default")
      (node (ref "D266") (pin "DI") (pinfunction "DI_DI") (pintype "input"))
      (node (ref "D267") (pin "DO") (pinfunction "DO_DO") (pintype "output"))
    )
    (net (code "100") (name "DO268") (class "Default")
      (node (ref "D267") (pin "DI") (pinfunction "DI_DI") (pintype "input"))
      (node (ref "D268") (pin "DO") (pinfunction "DO_DO") (pintype "output"))
    )
    (net (code "101") (name "DO269") (class "Default")
      (node (ref "D268") (pin "DI") (pinfunction "DI_DI") (pintype "input"))
      (node (ref "D269") (pin "DO") (pinfunction "DO_DO") (pintype "output"))
    )
    (net (code "102") (name "DO270") (class "Default")
      (node (ref "D269") (pin "DI") (pinfunction "DI_DI") (pintype "input"))
      (node (ref "D270") (pin "DO") (pinfunction "DO_DO") (pintype "output"))
    )
    (net (code "103") (name "DO271") (class "Default")
      (node (ref "D270") (pin "DI") (pinfunction "DI_DI") (pintype "input"))
      (node (ref "D271") (pin "DO") (pinfunction "DO_DO") (pintype "output"))
    )
    (net (code "104") (name "DO272") (class "Default")
      (node (ref "D271") (pin "DI") (pinfunction "DI_DI") (pintype "input"))
      (node (ref "D272") (pin "DO") (pinfunction "DO_DO") (pintype "output"))
    )
    (net (code "105") (name "DO273") (class "Default")
      (node (ref "D272") (pin "DI") (pinfunction "DI_DI") (pintype "input"))
      (node (ref "D273") (pin "DO") (pinfunction "DO_DO") (pintype "output"))
    )
    (net (code "106") (name "DO274") (class "Default")
      (node (ref "D273") (pin "DI") (pinfunction "DI_DI") (pintype "input"))
      (node (ref "D274") (pin "DO") (pinfunction "DO_DO") (pintype "output"))
    )
    (net (code "107") (name "DO275") (class "Default")
      (node (ref "D274") (pin "DI") (pinfunction "DI_DI") (pintype "input"))
      (node (ref "D275") (pin "DO") (pinfunction "DO_DO") (pintype "output"))
    )
    (net (code "108") (name "DO276") (class "Default")
      (node (ref "D275") (pin "DI") (pinfunction "DI_DI") (pintype "input"))
      (node (ref "D276") (pin "DO") (pinfunction "DO_DO") (pintype "output"))
    )
    (net (code "109") (name "DO277") (class "Default")
      (node (ref "D276") (pin "DI") (pinfunction "DI_DI") (pintype "input"))
      (node (ref "D277") (pin "DO") (pinfunction "DO_DO") (pintype "output"))
    )
    (net (code "110") (name "DO278") (class "Default")
      (node (ref "D277") (pin "DI") (pinfunction "DI_DI") (pintype "input"))
      (node (ref "D278") (pin "DO") (pinfunction "DO_DO") (pintype "output"))
    )
    (net (code "111") (name "DO279") (class "Default")
      (node (ref "D278") (pin "DI") (pinfunction "DI_DI") (pintype "input"))
      (node (ref "D279") (pin "DO") (pinfunction "DO_DO") (pintype "output"))
    )
    (net (code "112") (name "DO280") (class "Default")
      (node (ref "D279") (pin "DI") (pinfunction "DI_DI") (pintype "input"))
      (node (ref "D280") (pin "DO") (pinfunction "DO_DO") (pintype "output"))
    )
    (net (code "113") (name "DO281") (class "Default")
      (node (ref "D280") (pin "DI") (pinfunction "DI_DI") (pintype "input"))
      (node (ref "D281") (pin "DO") (pinfunction "DO_DO") (pintype "output"))
    )
    (net (code "114") (name "DO282") (class "Default")
      (node (ref "D281") (pin "DI") (pinfunction "DI_DI") (pintype "input"))
      (node (ref "D282") (pin "DO") (pinfunction "DO_DO") (pintype "output"))
    )
    (net (code "115") (name "DO283") (class "Default")
      (node (ref "D282") (pin "DI") (pinfunction "DI_DI") (pintype "input"))
      (node (ref "D283") (pin "DO") (pinfunction "DO_DO") (pintype "output"))
    )
    (net (code "116") (name "DO284") (class "Default")
      (node (ref "D283") (pin "DI") (pinfunction "DI_DI") (pintype "input"))
      (node (ref "D284") (pin "DO") (pinfunction "DO_DO") (pintype "output"))
    )
    (net (code "117") (name "DO285") (class "Default")
      (node (ref "D284") (pin "DI") (pinfunction "DI_DI") (pintype "input"))
      (node (ref "D285") (pin "DO") (pinfunction "DO_DO") (pintype "output"))
    )
    (net (code "118") (name "DO286") (class "Default")
      (node (ref "D285") (pin "DI") (pinfunction "DI_DI") (pintype "input"))
      (node (ref "D286") (pin "DO") (pinfunction "DO_DO") (pintype "output"))
    )
    (net (code "119") (name "DO287") (class "Default")
      (node (ref "D286") (pin "DI") (pinfunction "DI_DI") (pintype "input"))
      (node (ref "D287") (pin "DO") (pinfunction "DO_DO") (pintype "output"))
    )
    (net (code "120") (name "DO288") (class "Default")
      (node (ref "D287") (pin "DI") (pinfunction "DI_DI") (pintype "input"))
      (node (ref "D288") (pin "DO") (pinfunction "DO_DO") (pintype "output"))
    )
    (net (code "121") (name "DO289") (class "Default")
      (node (ref "D288") (pin "DI") (pinfunction "DI_DI") (pintype "input"))
      (node (ref "D289") (pin "DO") (pinfunction "DO_DO") (pintype "output"))
    )
    (net (code "122") (name "DO290") (class "Default")
      (node (ref "D289") (pin "DI") (pinfunction "DI_DI") (pintype "input"))
      (node (ref "D290") (pin "DO") (pinfunction "DO_DO") (pintype "output"))
    )
    (net (code "123") (name "DO291") (class "Default")
      (node (ref "D290") (pin "DI") (pinfunction "DI_DI") (pintype "input"))
      (node (ref "D291") (pin "DO") (pinfunction "DO_DO") (pintype "output"))
    )
    (net (code "124") (name "DO292") (class "Default")
      (node (ref "D291") (pin "DI") (pinfunction "DI_DI") (pintype "input"))
      (node (ref "D292") (pin "DO") (pinfunction "DO_DO") (pintype "output"))
    )
    (net (code "125") (name "DO293") (class "Default")
      (node (ref "D292") (pin "DI") (pinfunction "DI_DI") (pintype "input"))
      (node (ref "D293") (pin "DO") (pinfunction "DO_DO") (pintype "output"))
    )
    (net (code "126") (name "DO294") (class "Default")
      (node (ref "D293") (pin "DI") (pinfunction "DI_DI") (pintype "input"))
      (node (ref "D294") (pin "DO") (pinfunction "DO_DO") (pintype "output"))
    )
    (net (code "127") (name "DO295") (class "Default")
      (node (ref "D294") (pin "DI") (pinfunction "DI_DI") (pintype "input"))
      (node (ref "D295") (pin "DO") (pinfunction "DO_DO") (pintype "output"))
    )
    (net (code "128") (name "DO296") (class "Default")
      (node (ref "D295") (pin "DI") (pinfunction "DI_DI") (pintype "input"))
      (node (ref "D296") (pin "DO") (pinfunction "DO_DO") (pintype "output"))
    )
    (net (code "129") (name "DO297") (class "Default")
      (node (ref "D296") (pin "DI") (pinfunction "DI_DI") (pintype "input"))
      (node (ref "D297") (pin "DO") (pinfunction "DO_DO") (pintype "output"))
    )
    (net (code "130") (name "DO298") (class "Default")
      (node (ref "D297") (pin "DI") (pinfunction "DI_DI") (pintype "input"))
      (node (ref "D298") (pin "DO") (pinfunction "DO_DO") (pintype "output"))
    )
    (net (code "131") (name "DO299") (class "Default")
      (node (ref "D298") (pin "DI") (pinfunction "DI_DI") (pintype "input"))
      (node (ref "D299") (pin "DO") (pinfunction "DO_DO") (pintype "output"))
    )
    (net (code "132") (name "DO300") (class "Default")
      (node (ref "D299") (pin "DI") (pinfunction "DI_DI") (pintype "input"))
      (node (ref "D300") (pin "DO") (pinfunction "DO_DO") (pintype "output"))
    )
    (net (code "133") (name "DO301") (class "Default")
      (node (ref "D300") (pin "DI") (pinfunction "DI_DI") (pintype "input"))
      (node (ref "D301") (pin "DO") (pinfunction "DO_DO") (pintype "output"))
    )
    (net (code "134") (name "DO302") (class "Default")
      (node (ref "D301") (pin "DI") (pinfunction "DI_DI") (pintype "input"))
      (node (ref "D302") (pin "DO") (pinfunction "DO_DO") (pintype "output"))
    )
    (net (code "135") (name "DO303") (class "Default")
      (node (ref "D302") (pin "DI") (pinfunction "DI_DI") (pintype "input"))
      (node (ref "D303") (pin "DO") (pinfunction "DO_DO") (pintype "output"))
    )
    (net (code "136") (name "DO304") (class "Default")
      (node (ref "D303") (pin "DI") (pinfunction "DI_DI") (pintype "input"))
      (node (ref "D304") (pin "DO") (pinfunction "DO_DO") (pintype "output"))
    )
    (net (code "137") (name "DO305") (class "Default")
      (node (ref "D304") (pin "DI") (pinfunction "DI_DI") (pintype "input"))
      (node (ref "D305") (pin "DO") (pinfunction "DO_DO") (pintype "output"))
    )
    (net (code "138") (name "DO306") (class "Default")
      (node (ref "D305") (pin "DI") (pinfunction "DI_DI") (pintype "input"))
      (node (ref "D306") (pin "DO") (pinfunction "DO_DO") (pintype "output"))
    )
    (net (code "139") (name "DO307") (class "Default")
      (node (ref "D306") (pin "DI") (pinfunction "DI_DI") (pintype "input"))
      (node (ref "D307") (pin "DO") (pinfunction "DO_DO") (pintype "output"))
    )
    (net (code "140") (name "DO308") (class "Default")
      (node (ref "D307") (pin "DI") (pinfunction "DI_DI") (pintype "input"))
      (node (ref "D308") (pin "DO") (pinfunction "DO_DO") (pintype "output"))
    )
    (net (code "141") (name "DO309") (class "Default")
      (node (ref "D308") (pin "DI") (pinfunction "DI_DI") (pintype "input"))
      (node (ref "D309") (pin "DO") (pinfunction "DO_DO") (pintype "output"))
    )
    (net (code "142") (name "DO310") (class "Default")
      (node (ref "D309") (pin "DI") (pinfunction "DI_DI") (pintype "input"))
      (node (ref "D310") (pin "DO") (pinfunction "DO_DO") (pintype "output"))
    )
    (net (code "143") (name "DO311") (class "Default")
      (node (ref "D310") (pin "DI") (pinfunction "DI_DI") (pintype "input"))
      (node (ref "D311") (pin "DO") (pinfunction "DO_DO") (pintype "output"))
    )
    (net (code "144") (name "DO312") (class "Default")
      (node (ref "D311") (pin "DI") (pinfunction "DI_DI") (pintype "input"))
      (node (ref "D312") (pin "DO") (pinfunction "DO_DO") (pintype "output"))
    )
    (net (code "145") (name "DO313") (class "Default")
      (node (ref "D312") (pin "DI") (pinfunction "DI_DI") (pintype "input"))
      (node (ref "D313") (pin "DO") (pinfunction "DO_DO") (pintype "output"))
    )
    (net (code "146") (name "DO314") (class "Default")
      (node (ref "D313") (pin "DI") (pinfunction "DI_DI") (pintype "input"))
      (node (ref "D314") (pin "DO") (pinfunction "DO_DO") (pintype "output"))
    )
    (net (code "147") (name "DO315") (class "Default")
      (node (ref "D314") (pin "DI") (pinfunction "DI_DI") (pintype "input"))
      (node (ref "D315") (pin "DO") (pinfunction "DO_DO") (pintype "output"))
    )
    (net (code "148") (name "DO316") (class "Default")
      (node (ref "D315") (pin "DI") (pinfunction "DI_DI") (pintype "input"))
      (node (ref "D316") (pin "DO") (pinfunction "DO_DO") (pintype "output"))
    )
    (net (code "149") (name "DO331") (class "Default")
      (node (ref "D330") (pin "DI") (pinfunction "DI_DI") (pintype "input"))
      (node (ref "D331") (pin "DO") (pinfunction "DO_DO") (pintype "output"))
    )
    (net (code "150") (name "DO346") (class "Default")
      (node (ref "D345") (pin "DI") (pinfunction "DI_DI") (pintype "input"))
      (node (ref "D346") (pin "DO") (pinfunction "DO_DO") (pintype "output"))
    )
    (net (code "151") (name "DO361") (class "Default")
      (node (ref "D360") (pin "DI") (pinfunction "DI_DI") (pintype "input"))
      (node (ref "D361") (pin "DO") (pinfunction "DO_DO") (pintype "output"))
    )
    (net (code "152") (name "DO376") (class "Default")
      (node (ref "D375") (pin "DI") (pinfunction "DI_DI") (pintype "input"))
      (node (ref "D376") (pin "DO") (pinfunction "DO_DO") (pintype "output"))
    )
    (net (code "153") (name "DO391") (class "Default")
      (node (ref "D390") (pin "DI") (pinfunction "DI_DI") (pintype "input"))
      (node (ref "D391") (pin "DO") (pinfunction "DO_DO") (pintype "output"))
    )
    (net (code "154") (name "GND") (class "Default")
      (node (ref "C1") (pin "-") (pinfunction "-_-") (pintype "passive"))
      (node (ref "C10") (pin "-") (pinfunction "-_-") (pintype "passive"))
      (node (ref "C100") (pin "2") (pinfunction "2_2") (pintype "passive"))
      (node (ref "C101") (pin "2") (pinfunction "2_2") (pintype "passive"))
      (node (ref "C102") (pin "2") (pinfunction "2_2") (pintype "passive"))
      (node (ref "C103") (pin "2") (pinfunction "2_2") (pintype "passive"))
      (node (ref "C104") (pin "2") (pinfunction "2_2") (pintype "passive"))
      (node (ref "C105") (pin "2") (pinfunction "2_2") (pintype "passive"))
      (node (ref "C106") (pin "2") (pinfunction "2_2") (pintype "passive"))
      (node (ref "C107") (pin "2") (pinfunction "2_2") (pintype "passive"))
      (node (ref "C108") (pin "2") (pinfunction "2_2") (pintype "passive"))
      (node (ref "C109") (pin "2") (pinfunction "2_2") (pintype "passive"))
      (node (ref "C11") (pin "-") (pinfunction "-_-") (pintype "passive"))
      (node (ref "C110") (pin "2") (pinfunction "2_2") (pintype "passive"))
      (node (ref "C111") (pin "2") (pinfunction "2_2") (pintype "passive"))
      (node (ref "C112") (pin "2") (pinfunction "2_2") (pintype "passive"))
      (node (ref "C113") (pin "2") (pinfunction "2_2") (pintype "passive"))
      (node (ref "C114") (pin "2") (pinfunction "2_2") (pintype "passive"))
      (node (ref "C115") (pin "2") (pinfunction "2_2") (pintype "passive"))
      (node (ref "C116") (pin "2") (pinfunction "2_2") (pintype "passive"))
      (node (ref "C117") (pin "2") (pinfunction "2_2") (pintype "passive"))
      (node (ref "C118") (pin "2") (pinfunction "2_2") (pintype "passive"))
      (node (ref "C119") (pin "2") (pinfunction "2_2") (pintype "passive"))
      (node (ref "C12") (pin "-") (pinfunction "-_-") (pintype "passive"))
      (node (ref "C120") (pin "2") (pinfunction "2_2") (pintype "passive"))
      (node (ref "C121") (pin "2") (pinfunction "2_2") (pintype "passive"))
      (node (ref "C122") (pin "2") (pinfunction "2_2") (pintype "passive"))
      (node (ref "C123") (pin "2") (pinfunction "2_2") (pintype "passive"))
      (node (ref "C124") (pin "2") (pinfunction "2_2") (pintype "passive"))
      (node (ref "C125") (pin "2") (pinfunction "2_2") (pintype "passive"))
      (node (ref "C126") (pin "2") (pinfunction "2_2") (pintype "passive"))
      (node (ref "C127") (pin "2") (pinfunction "2_2") (pintype "passive"))
      (node (ref "C128") (pin "2") (pinfunction "2_2") (pintype "passive"))
      (node (ref "C129") (pin "2") (pinfunction "2_2") (pintype "passive"))
      (node (ref "C13") (pin "-") (pinfunction "-_-") (pintype "passive"))
      (node (ref "C130") (pin "2") (pinfunction "2_2") (pintype "passive"))
      (node (ref "C131") (pin "2") (pinfunction "2_2") (pintype "passive"))
      (node (ref "C132") (pin "2") (pinfunction "2_2") (pintype "passive"))
      (node (ref "C133") (pin "2") (pinfunction "2_2") (pintype "passive"))
      (node (ref "C134") (pin "2") (pinfunction "2_2") (pintype "passive"))
      (node (ref "C135") (pin "2") (pinfunction "2_2") (pintype "passive"))
      (node (ref "C136") (pin "2") (pinfunction "2_2") (pintype "passive"))
      (node (ref "C137") (pin "2") (pinfunction "2_2") (pintype "passive"))
      (node (ref "C138") (pin "2") (pinfunction "2_2") (pintype "passive"))
      (node (ref "C139") (pin "2") (pinfunction "2_2") (pintype "passive"))
      (node (ref "C14") (pin "-") (pinfunction "-_-") (pintype "passive"))
      (node (ref "C140") (pin "2") (pinfunction "2_2") (pintype "passive"))
      (node (ref "C141") (pin "2") (pinfunction "2_2") (pintype "passive"))
      (node (ref "C142") (pin "2") (pinfunction "2_2") (pintype "passive"))
      (node (ref "C143") (pin "2") (pinfunction "2_2") (pintype "passive"))
      (node (ref "C144") (pin "2") (pinfunction "2_2") (pintype "passive"))
      (node (ref "C145") (pin "2") (pinfunction "2_2") (pintype "passive"))
      (node (ref "C146") (pin "2") (pinfunction "2_2") (pintype "passive"))
      (node (ref "C147") (pin "2") (pinfunction "2_2") (pintype "passive"))
      (node (ref "C148") (pin "2") (pinfunction "2_2") (pintype "passive"))
      (node (ref "C149") (pin "2") (pinfunction "2_2") (pintype "passive"))
      (node (ref "C15") (pin "-") (pinfunction "-_-") (pintype "passive"))
      (node (ref "C150") (pin "2") (pinfunction "2_2") (pintype "passive"))
      (node (ref "C151") (pin "2") (pinfunction "2_2") (pintype "passive"))
      (node (ref "C152") (pin "2") (pinfunction "2_2") (pintype "passive"))
      (node (ref "C153") (pin "2") (pinfunction "2_2") (pintype "passive"))
      (node (ref "C154") (pin "2") (pinfunction "2_2") (pintype "passive"))
      (node (ref "C155") (pin "2") (pinfunction "2_2") (pintype "passive"))
      (node (ref "C156") (pin "2") (pinfunction "2_2") (pintype "passive"))
      (node (ref "C157") (pin "2") (pinfunction "2_2") (pintype "passive"))
      (node (ref "C158") (pin "2") (pinfunction "2_2") (pintype "passive"))
      (node (ref "C159") (pin "2") (pinfunction "2_2") (pintype "passive"))
      (node (ref "C16") (pin "-") (pinfunction "-_-") (pintype "passive"))
      (node (ref "C160") (pin "2") (pinfunction "2_2") (pintype "passive"))
      (node (ref "C161") (pin "2") (pinfunction "2_2") (pintype "passive"))
      (node (ref "C162") (pin "2") (pinfunction "2_2") (pintype "passive"))
      (node (ref "C163") (pin "2") (pinfunction "2_2") (pintype "passive"))
      (node (ref "C164") (pin "2") (pinfunction "2_2") (pintype "passive"))
      (node (ref "C165") (pin "2") (pinfunction "2_2") (pintype "passive"))
      (node (ref "C166") (pin "2") (pinfunction "2_2") (pintype "passive"))
      (node (ref "C167") (pin "2") (pinfunction "2_2") (pintype "passive"))
      (node (ref "C168") (pin "2") (pinfunction "2_2") (pintype "passive"))
      (node (ref "C169") (pin "2") (pinfunction "2_2") (pintype "passive"))
      (node (ref "C17") (pin "-") (pinfunction "-_-") (pintype "passive"))
      (node (ref "C18") (pin "-") (pinfunction "-_-") (pintype "passive"))
      (node (ref "C19") (pin "-") (pinfunction "-_-") (pintype "passive"))
      (node (ref "C2") (pin "-") (pinfunction "-_-") (pintype "passive"))
      (node (ref "C20") (pin "-") (pinfunction "-_-") (pintype "passive"))
      (node (ref "C21") (pin "-") (pinfunction "-_-") (pintype "passive"))
      (node (ref "C22") (pin "-") (pinfunction "-_-") (pintype "passive"))
      (node (ref "C23") (pin "-") (pinfunction "-_-") (pintype "passive"))
      (node (ref "C24") (pin "-") (pinfunction "-_-") (pintype "passive"))
      (node (ref "C25") (pin "2") (pinfunction "2_2") (pintype "passive"))
      (node (ref "C26") (pin "2") (pinfunction "2_2") (pintype "passive"))
      (node (ref "C27") (pin "2") (pinfunction "2_2") (pintype "passive"))
      (node (ref "C28") (pin "2") (pinfunction "2_2") (pintype "passive"))
      (node (ref "C29") (pin "2") (pinfunction "2_2") (pintype "passive"))
      (node (ref "C3") (pin "-") (pinfunction "-_-") (pintype "passive"))
      (node (ref "C30") (pin "2") (pinfunction "2_2") (pintype "passive"))
      (node (ref "C31") (pin "2") (pinfunction "2_2") (pintype "passive"))
      (node (ref "C32") (pin "2") (pinfunction "2_2") (pintype "passive"))
      (node (ref "C33") (pin "2") (pinfunction "2_2") (pintype "passive"))
      (node (ref "C34") (pin "2") (pinfunction "2_2") (pintype "passive"))
      (node (ref "C35") (pin "2") (pinfunction "2_2") (pintype "passive"))
      (node (ref "C36") (pin "2") (pinfunction "2_2") (pintype "passive"))
      (node (ref "C37") (pin "2") (pinfunction "2_2") (pintype "passive"))
      (node (ref "C38") (pin "2") (pinfunction "2_2") (pintype "passive"))
      (node (ref "C39") (pin "2") (pinfunction "2_2") (pintype "passive"))
      (node (ref "C4") (pin "-") (pinfunction "-_-") (pintype "passive"))
      (node (ref "C40") (pin "2") (pinfunction "2_2") (pintype "passive"))
      (node (ref "C41") (pin "2") (pinfunction "2_2") (pintype "passive"))
      (node (ref "C42") (pin "2") (pinfunction "2_2") (pintype "passive"))
      (node (ref "C43") (pin "2") (pinfunction "2_2") (pintype "passive"))
      (node (ref "C44") (pin "2") (pinfunction "2_2") (pintype "passive"))
      (node (ref "C45") (pin "2") (pinfunction "2_2") (pintype "passive"))
      (node (ref "C46") (pin "2") (pinfunction "2_2") (pintype "passive"))
      (node (ref "C47") (pin "2") (pinfunction "2_2") (pintype "passive"))
      (node (ref "C48") (pin "2") (pinfunction "2_2") (pintype "passive"))
      (node (ref "C49") (pin "2") (pinfunction "2_2") (pintype "passive"))
      (node (ref "C5") (pin "-") (pinfunction "-_-") (pintype "passive"))
      (node (ref "C50") (pin "2") (pinfunction "2_2") (pintype "passive"))
      (node (ref "C51") (pin "2") (pinfunction "2_2") (pintype "passive"))
      (node (ref "C52") (pin "2") (pinfunction "2_2") (pintype "passive"))
      (node (ref "C53") (pin "2") (pinfunction "2_2") (pintype "passive"))
      (node (ref "C54") (pin "2") (pinfunction "2_2") (pintype "passive"))
      (node (ref "C55") (pin "2") (pinfunction "2_2") (pintype "passive"))
      (node (ref "C56") (pin "2") (pinfunction "2_2") (pintype "passive"))
      (node (ref "C57") (pin "2") (pinfunction "2_2") (pintype "passive"))
      (node (ref "C58") (pin "2") (pinfunction "2_2") (pintype "passive"))
      (node (ref "C59") (pin "2") (pinfunction "2_2") (pintype "passive"))
      (node (ref "C6") (pin "-") (pinfunction "-_-") (pintype "passive"))
      (node (ref "C60") (pin "2") (pinfunction "2_2") (pintype "passive"))
      (node (ref "C61") (pin "2") (pinfunction "2_2") (pintype "passive"))
      (node (ref "C62") (pin "2") (pinfunction "2_2") (pintype "passive"))
      (node (ref "C63") (pin "2") (pinfunction "2_2") (pintype "passive"))
      (node (ref "C64") (pin "2") (pinfunction "2_2") (pintype "passive"))
      (node (ref "C65") (pin "2") (pinfunction "2_2") (pintype "passive"))
      (node (ref "C66") (pin "2") (pinfunction "2_2") (pintype "passive"))
      (node (ref "C67") (pin "2") (pinfunction "2_2") (pintype "passive"))
      (node (ref "C68") (pin "2") (pinfunction "2_2") (pintype "passive"))
      (node (ref "C69") (pin "2") (pinfunction "2_2") (pintype "passive"))
      (node (ref "C7") (pin "-") (pinfunction "-_-") (pintype "passive"))
      (node (ref "C70") (pin "2") (pinfunction "2_2") (pintype "passive"))
      (node (ref "C71") (pin "2") (pinfunction "2_2") (pintype "passive"))
      (node (ref "C72") (pin "2") (pinfunction "2_2") (pintype "passive"))
      (node (ref "C73") (pin "2") (pinfunction "2_2") (pintype "passive"))
      (node (ref "C74") (pin "2") (pinfunction "2_2") (pintype "passive"))
      (node (ref "C75") (pin "2") (pinfunction "2_2") (pintype "passive"))
      (node (ref "C76") (pin "2") (pinfunction "2_2") (pintype "passive"))
      (node (ref "C77") (pin "2") (pinfunction "2_2") (pintype "passive"))
      (node (ref "C78") (pin "2") (pinfunction "2_2") (pintype "passive"))
      (node (ref "C79") (pin "2") (pinfunction "2_2") (pintype "passive"))
      (node (ref "C8") (pin "-") (pinfunction "-_-") (pintype "passive"))
      (node (ref "C80") (pin "2") (pinfunction "2_2") (pintype "passive"))
      (node (ref "C81") (pin "2") (pinfunction "2_2") (pintype "passive"))
      (node (ref "C82") (pin "2") (pinfunction "2_2") (pintype "passive"))
      (node (ref "C83") (pin "2") (pinfunction "2_2") (pintype "passive"))
      (node (ref "C84") (pin "2") (pinfunction "2_2") (pintype "passive"))
      (node (ref "C85") (pin "2") (pinfunction "2_2") (pintype "passive"))
      (node (ref "C86") (pin "2") (pinfunction "2_2") (pintype "passive"))
      (node (ref "C87") (pin "2") (pinfunction "2_2") (pintype "passive"))
      (node (ref "C88") (pin "2") (pinfunction "2_2") (pintype "passive"))
      (node (ref "C89") (pin "2") (pinfunction "2_2") (pintype "passive"))
      (node (ref "C9") (pin "-") (pinfunction "-_-") (pintype "passive"))
      (node (ref "C90") (pin "2") (pinfunction "2_2") (pintype "passive"))
      (node (ref "C91") (pin "2") (pinfunction "2_2") (pintype "passive"))
      (node (ref "C92") (pin "2") (pinfunction "2_2") (pintype "passive"))
      (node (ref "C93") (pin "2") (pinfunction "2_2") (pintype "passive"))
      (node (ref "C94") (pin "2") (pinfunction "2_2") (pintype "passive"))
      (node (ref "C95") (pin "2") (pinfunction "2_2") (pintype "passive"))
      (node (ref "C96") (pin "2") (pinfunction "2_2") (pintype "passive"))
      (node (ref "C97") (pin "2") (pinfunction "2_2") (pintype "passive"))
      (node (ref "C98") (pin "2") (pinfunction "2_2") (pintype "passive"))
      (node (ref "C99") (pin "2") (pinfunction "2_2") (pintype "passive"))
      (node (ref "D1") (pin "GND") (pinfunction "GND_GND") (pintype "power_in"))
      (node (ref "D10") (pin "GND") (pinfunction "GND_GND") (pintype "power_in"))
      (node (ref "D100") (pin "GND") (pinfunction "GND_GND") (pintype "power_in"))
      (node (ref "D101") (pin "GND") (pinfunction "GND_GND") (pintype "power_in"))
      (node (ref "D102") (pin "GND") (pinfunction "GND_GND") (pintype "power_in"))
      (node (ref "D103") (pin "GND") (pinfunction "GND_GND") (pintype "power_in"))
      (node (ref "D104") (pin "GND") (pinfunction "GND_GND") (pintype "power_in"))
      (node (ref "D105") (pin "GND") (pinfunction "GND_GND") (pintype "power_in"))
      (node (ref "D106") (pin "GND") (pinfunction "GND_GND") (pintype "power_in"))
      (node (ref "D107") (pin "GND") (pinfunction "GND_GND") (pintype "power_in"))
      (node (ref "D108") (pin "GND") (pinfunction "GND_GND") (pintype "power_in"))
      (node (ref "D109") (pin "GND") (pinfunction "GND_GND") (pintype "power_in"))
      (node (ref "D11") (pin "GND") (pinfunction "GND_GND") (pintype "power_in"))
      (node (ref "D110") (pin "GND") (pinfunction "GND_GND") (pintype "power_in"))
      (node (ref "D111") (pin "GND") (pinfunction "GND_GND") (pintype "power_in"))
      (node (ref "D112") (pin "GND") (pinfunction "GND_GND") (pintype "power_in"))
      (node (ref "D113") (pin "GND") (pinfunction "GND_GND") (pintype "power_in"))
      (node (ref "D114") (pin "GND") (pinfunction "GND_GND") (pintype "power_in"))
      (node (ref "D115") (pin "GND") (pinfunction "GND_GND") (pintype "power_in"))
      (node (ref "D116") (pin "GND") (pinfunction "GND_GND") (pintype "power_in"))
      (node (ref "D117") (pin "GND") (pinfunction "GND_GND") (pintype "power_in"))
      (node (ref "D118") (pin "GND") (pinfunction "GND_GND") (pintype "power_in"))
      (node (ref "D119") (pin "GND") (pinfunction "GND_GND") (pintype "power_in"))
      (node (ref "D12") (pin "GND") (pinfunction "GND_GND") (pintype "power_in"))
      (node (ref "D120") (pin "GND") (pinfunction "GND_GND") (pintype "power_in"))
      (node (ref "D121") (pin "GND") (pinfunction "GND_GND") (pintype "power_in"))
      (node (ref "D122") (pin "GND") (pinfunction "GND_GND") (pintype "power_in"))
      (node (ref "D123") (pin "GND") (pinfunction "GND_GND") (pintype "power_in"))
      (node (ref "D124") (pin "GND") (pinfunction "GND_GND") (pintype "power_in"))
      (node (ref "D125") (pin "GND") (pinfunction "GND_GND") (pintype "power_in"))
      (node (ref "D126") (pin "GND") (pinfunction "GND_GND") (pintype "power_in"))
      (node (ref "D127") (pin "GND") (pinfunction "GND_GND") (pintype "power_in"))
      (node (ref "D128") (pin "GND") (pinfunction "GND_GND") (pintype "power_in"))
      (node (ref "D129") (pin "GND") (pinfunction "GND_GND") (pintype "power_in"))
      (node (ref "D13") (pin "GND") (pinfunction "GND_GND") (pintype "power_in"))
      (node (ref "D130") (pin "GND") (pinfunction "GND_GND") (pintype "power_in"))
      (node (ref "D131") (pin "GND") (pinfunction "GND_GND") (pintype "power_in"))
      (node (ref "D132") (pin "GND") (pinfunction "GND_GND") (pintype "power_in"))
      (node (ref "D133") (pin "GND") (pinfunction "GND_GND") (pintype "power_in"))
      (node (ref "D134") (pin "GND") (pinfunction "GND_GND") (pintype "power_in"))
      (node (ref "D135") (pin "GND") (pinfunction "GND_GND") (pintype "power_in"))
      (node (ref "D136") (pin "GND") (pinfunction "GND_GND") (pintype "power_in"))
      (node (ref "D137") (pin "GND") (pinfunction "GND_GND") (pintype "power_in"))
      (node (ref "D138") (pin "GND") (pinfunction "GND_GND") (pintype "power_in"))
      (node (ref "D139") (pin "GND") (pinfunction "GND_GND") (pintype "power_in"))
      (node (ref "D14") (pin "GND") (pinfunction "GND_GND") (pintype "power_in"))
      (node (ref "D140") (pin "GND") (pinfunction "GND_GND") (pintype "power_in"))
      (node (ref "D141") (pin "GND") (pinfunction "GND_GND") (pintype "power_in"))
      (node (ref "D142") (pin "GND") (pinfunction "GND_GND") (pintype "power_in"))
      (node (ref "D143") (pin "GND") (pinfunction "GND_GND") (pintype "power_in"))
      (node (ref "D144") (pin "GND") (pinfunction "GND_GND") (pintype "power_in"))
      (node (ref "D145") (pin "GND") (pinfunction "GND_GND") (pintype "power_in"))
      (node (ref "D146") (pin "GND") (pinfunction "GND_GND") (pintype "power_in"))
      (node (ref "D147") (pin "GND") (pinfunction "GND_GND") (pintype "power_in"))
      (node (ref "D148") (pin "GND") (pinfunction "GND_GND") (pintype "power_in"))
      (node (ref "D149") (pin "GND") (pinfunction "GND_GND") (pintype "power_in"))
      (node (ref "D15") (pin "GND") (pinfunction "GND_GND") (pintype "power_in"))
      (node (ref "D150") (pin "GND") (pinfunction "GND_GND") (pintype "power_in"))
      (node (ref "D151") (pin "GND") (pinfunction "GND_GND") (pintype "power_in"))
      (node (ref "D152") (pin "GND") (pinfunction "GND_GND") (pintype "power_in"))
      (node (ref "D153") (pin "GND") (pinfunction "GND_GND") (pintype "power_in"))
      (node (ref "D154") (pin "GND") (pinfunction "GND_GND") (pintype "power_in"))
      (node (ref "D155") (pin "GND") (pinfunction "GND_GND") (pintype "power_in"))
      (node (ref "D156") (pin "GND") (pinfunction "GND_GND") (pintype "power_in"))
      (node (ref "D157") (pin "GND") (pinfunction "GND_GND") (pintype "power_in"))
      (node (ref "D158") (pin "GND") (pinfunction "GND_GND") (pintype "power_in"))
      (node (ref "D159") (pin "GND") (pinfunction "GND_GND") (pintype "power_in"))
      (node (ref "D16") (pin "GND") (pinfunction "GND_GND") (pintype "power_in"))
      (node (ref "D160") (pin "GND") (pinfunction "GND_GND") (pintype "power_in"))
      (node (ref "D161") (pin "GND") (pinfunction "GND_GND") (pintype "power_in"))
      (node (ref "D162") (pin "GND") (pinfunction "GND_GND") (pintype "power_in"))
      (node (ref "D163") (pin "GND") (pinfunction "GND_GND") (pintype "power_in"))
      (node (ref "D164") (pin "GND") (pinfunction "GND_GND") (pintype "power_in"))
      (node (ref "D165") (pin "GND") (pinfunction "GND_GND") (pintype "power_in"))
      (node (ref "D166") (pin "GND") (pinfunction "GND_GND") (pintype "power_in"))
      (node (ref "D167") (pin "GND") (pinfunction "GND_GND") (pintype "power_in"))
      (node (ref "D168") (pin "GND") (pinfunction "GND_GND") (pintype "power_in"))
      (node (ref "D169") (pin "GND") (pinfunction "GND_GND") (pintype "power_in"))
      (node (ref "D17") (pin "GND") (pinfunction "GND_GND") (pintype "power_in"))
      (node (ref "D170") (pin "GND") (pinfunction "GND_GND") (pintype "power_in"))
      (node (ref "D171") (pin "GND") (pinfunction "GND_GND") (pintype "power_in"))
      (node (ref "D172") (pin "GND") (pinfunction "GND_GND") (pintype "power_in"))
      (node (ref "D173") (pin "GND") (pinfunction "GND_GND") (pintype "power_in"))
      (node (ref "D174") (pin "GND") (pinfunction "GND_GND") (pintype "power_in"))
      (node (ref "D175") (pin "GND") (pinfunction "GND_GND") (pintype "power_in"))
      (node (ref "D176") (pin "GND") (pinfunction "GND_GND") (pintype "power_in"))
      (node (ref "D177") (pin "GND") (pinfunction "GND_GND") (pintype "power_in"))
      (node (ref "D178") (pin "GND") (pinfunction "GND_GND") (pintype "power_in"))
      (node (ref "D179") (pin "GND") (pinfunction "GND_GND") (pintype "power_in"))
      (node (ref "D18") (pin "GND") (pinfunction "GND_GND") (pintype "power_in"))
      (node (ref "D180") (pin "GND") (pinfunction "GND_GND") (pintype "power_in"))
      (node (ref "D181") (pin "GND") (pinfunction "GND_GND") (pintype "power_in"))
      (node (ref "D182") (pin "GND") (pinfunction "GND_GND") (pintype "power_in"))
      (node (ref "D183") (pin "GND") (pinfunction "GND_GND") (pintype "power_in"))
      (node (ref "D184") (pin "GND") (pinfunction "GND_GND") (pintype "power_in"))
      (node (ref "D185") (pin "GND") (pinfunction "GND_GND") (pintype "power_in"))
      (node (ref "D186") (pin "GND") (pinfunction "GND_GND") (pintype "power_in"))
      (node (ref "D187") (pin "GND") (pinfunction "GND_GND") (pintype "power_in"))
      (node (ref "D188") (pin "GND") (pinfunction "GND_GND") (pintype "power_in"))
      (node (ref "D189") (pin "GND") (pinfunction "GND_GND") (pintype "power_in"))
      (node (ref "D19") (pin "GND") (pinfunction "GND_GND") (pintype "power_in"))
      (node (ref "D190") (pin "GND") (pinfunction "GND_GND") (pintype "power_in"))
      (node (ref "D191") (pin "GND") (pinfunction "GND_GND") (pintype "power_in"))
      (node (ref "D192") (pin "GND") (pinfunction "GND_GND") (pintype "power_in"))
      (node (ref "D193") (pin "GND") (pinfunction "GND_GND") (pintype "power_in"))
      (node (ref "D194") (pin "GND") (pinfunction "GND_GND") (pintype "power_in"))
      (node (ref "D195") (pin "GND") (pinfunction "GND_GND") (pintype "power_in"))
      (node (ref "D196") (pin "GND") (pinfunction "GND_GND") (pintype "power_in"))
      (node (ref "D197") (pin "GND") (pinfunction "GND_GND") (pintype "power_in"))
      (node (ref "D198") (pin "GND") (pinfunction "GND_GND") (pintype "power_in"))
      (node (ref "D199") (pin "GND") (pinfunction "GND_GND") (pintype "power_in"))
      (node (ref "D2") (pin "GND") (pinfunction "GND_GND") (pintype "power_in"))
      (node (ref "D20") (pin "GND") (pinfunction "GND_GND") (pintype "power_in"))
      (node (ref "D200") (pin "GND") (pinfunction "GND_GND") (pintype "power_in"))
      (node (ref "D201") (pin "GND") (pinfunction "GND_GND") (pintype "power_in"))
      (node (ref "D202") (pin "GND") (pinfunction "GND_GND") (pintype "power_in"))
      (node (ref "D203") (pin "GND") (pinfunction "GND_GND") (pintype "power_in"))
      (node (ref "D204") (pin "GND") (pinfunction "GND_GND") (pintype "power_in"))
      (node (ref "D205") (pin "GND") (pinfunction "GND_GND") (pintype "power_in"))
      (node (ref "D206") (pin "GND") (pinfunction "GND_GND") (pintype "power_in"))
      (node (ref "D207") (pin "GND") (pinfunction "GND_GND") (pintype "power_in"))
      (node (ref "D208") (pin "GND") (pinfunction "GND_GND") (pintype "power_in"))
      (node (ref "D209") (pin "GND") (pinfunction "GND_GND") (pintype "power_in"))
      (node (ref "D21") (pin "GND") (pinfunction "GND_GND") (pintype "power_in"))
      (node (ref "D210") (pin "GND") (pinfunction "GND_GND") (pintype "power_in"))
      (node (ref "D211") (pin "GND") (pinfunction "GND_GND") (pintype "power_in"))
      (node (ref "D212") (pin "GND") (pinfunction "GND_GND") (pintype "power_in"))
      (node (ref "D213") (pin "GND") (pinfunction "GND_GND") (pintype "power_in"))
      (node (ref "D214") (pin "GND") (pinfunction "GND_GND") (pintype "power_in"))
      (node (ref "D215") (pin "GND") (pinfunction "GND_GND") (pintype "power_in"))
      (node (ref "D216") (pin "GND") (pinfunction "GND_GND") (pintype "power_in"))
      (node (ref "D217") (pin "GND") (pinfunction "GND_GND") (pintype "power_in"))
      (node (ref "D218") (pin "GND") (pinfunction "GND_GND") (pintype "power_in"))
      (node (ref "D219") (pin "GND") (pinfunction "GND_GND") (pintype "power_in"))
      (node (ref "D22") (pin "GND") (pinfunction "GND_GND") (pintype "power_in"))
      (node (ref "D220") (pin "GND") (pinfunction "GND_GND") (pintype "power_in"))
      (node (ref "D221") (pin "GND") (pinfunction "GND_GND") (pintype "power_in"))
      (node (ref "D222") (pin "GND") (pinfunction "GND_GND") (pintype "power_in"))
      (node (ref "D223") (pin "GND") (pinfunction "GND_GND") (pintype "power_in"))
      (node (ref "D224") (pin "GND") (pinfunction "GND_GND") (pintype "power_in"))
      (node (ref "D225") (pin "GND") (pinfunction "GND_GND") (pintype "power_in"))
      (node (ref "D226") (pin "GND") (pinfunction "GND_GND") (pintype "power_in"))
      (node (ref "D227") (pin "GND") (pinfunction "GND_GND") (pintype "power_in"))
      (node (ref "D228") (pin "GND") (pinfunction "GND_GND") (pintype "power_in"))
      (node (ref "D229") (pin "GND") (pinfunction "GND_GND") (pintype "power_in"))
      (node (ref "D23") (pin "GND") (pinfunction "GND_GND") (pintype "power_in"))
      (node (ref "D230") (pin "GND") (pinfunction "GND_GND") (pintype "power_in"))
      (node (ref "D231") (pin "GND") (pinfunction "GND_GND") (pintype "power_in"))
      (node (ref "D232") (pin "GND") (pinfunction "GND_GND") (pintype "power_in"))
      (node (ref "D233") (pin "GND") (pinfunction "GND_GND") (pintype "power_in"))
      (node (ref "D234") (pin "GND") (pinfunction "GND_GND") (pintype "power_in"))
      (node (ref "D235") (pin "GND") (pinfunction "GND_GND") (pintype "power_in"))
      (node (ref "D236") (pin "GND") (pinfunction "GND_GND") (pintype "power_in"))
      (node (ref "D237") (pin "GND") (pinfunction "GND_GND") (pintype "power_in"))
      (node (ref "D238") (pin "GND") (pinfunction "GND_GND") (pintype "power_in"))
      (node (ref "D239") (pin "GND") (pinfunction "GND_GND") (pintype "power_in"))
      (node (ref "D24") (pin "GND") (pinfunction "GND_GND") (pintype "power_in"))
      (node (ref "D240") (pin "GND") (pinfunction "GND_GND") (pintype "power_in"))
      (node (ref "D241") (pin "GND") (pinfunction "GND_GND") (pintype "power_in"))
      (node (ref "D242") (pin "GND") (pinfunction "GND_GND") (pintype "power_in"))
      (node (ref "D243") (pin "GND") (pinfunction "GND_GND") (pintype "power_in"))
      (node (ref "D244") (pin "GND") (pinfunction "GND_GND") (pintype "power_in"))
      (node (ref "D245") (pin "GND") (pinfunction "GND_GND") (pintype "power_in"))
      (node (ref "D246") (pin "GND") (pinfunction "GND_GND") (pintype "power_in"))
      (node (ref "D247") (pin "GND") (pinfunction "GND_GND") (pintype "power_in"))
      (node (ref "D248") (pin "GND") (pinfunction "GND_GND") (pintype "power_in"))
      (node (ref "D249") (pin "GND") (pinfunction "GND_GND") (pintype "power_in"))
      (node (ref "D25") (pin "GND") (pinfunction "GND_GND") (pintype "power_in"))
      (node (ref "D250") (pin "GND") (pinfunction "GND_GND") (pintype "power_in"))
      (node (ref "D251") (pin "GND") (pinfunction "GND_GND") (pintype "power_in"))
      (node (ref "D252") (pin "GND") (pinfunction "GND_GND") (pintype "power_in"))
      (node (ref "D253") (pin "GND") (pinfunction "GND_GND") (pintype "power_in"))
      (node (ref "D254") (pin "GND") (pinfunction "GND_GND") (pintype "power_in"))
      (node (ref "D255") (pin "GND") (pinfunction "GND_GND") (pintype "power_in"))
      (node (ref "D256") (pin "GND") (pinfunction "GND_GND") (pintype "power_in"))
      (node (ref "D257") (pin "GND") (pinfunction "GND_GND") (pintype "power_in"))
      (node (ref "D258") (pin "GND") (pinfunction "GND_GND") (pintype "power_in"))
      (node (ref "D259") (pin "GND") (pinfunction "GND_GND") (pintype "power_in"))
      (node (ref "D26") (pin "GND") (pinfunction "GND_GND") (pintype "power_in"))
      (node (ref "D260") (pin "GND") (pinfunction "GND_GND") (pintype "power_in"))
      (node (ref "D261") (pin "GND") (pinfunction "GND_GND") (pintype "power_in"))
      (node (ref "D262") (pin "GND") (pinfunction "GND_GND") (pintype "power_in"))
      (node (ref "D263") (pin "GND") (pinfunction "GND_GND") (pintype "power_in"))
      (node (ref "D264") (pin "GND") (pinfunction "GND_GND") (pintype "power_in"))
      (node (ref "D265") (pin "GND") (pinfunction "GND_GND") (pintype "power_in"))
      (node (ref "D266") (pin "GND") (pinfunction "GND_GND") (pintype "power_in"))
      (node (ref "D267") (pin "GND") (pinfunction "GND_GND") (pintype "power_in"))
      (node (ref "D268") (pin "GND") (pinfunction "GND_GND") (pintype "power_in"))
      (node (ref "D269") (pin "GND") (pinfunction "GND_GND") (pintype "power_in"))
      (node (ref "D27") (pin "GND") (pinfunction "GND_GND") (pintype "power_in"))
      (node (ref "D270") (pin "GND") (pinfunction "GND_GND") (pintype "power_in"))
      (node (ref "D271") (pin "GND") (pinfunction "GND_GND") (pintype "power_in"))
      (node (ref "D272") (pin "GND") (pinfunction "GND_GND") (pintype "power_in"))
      (node (ref "D273") (pin "GND") (pinfunction "GND_GND") (pintype "power_in"))
      (node (ref "D274") (pin "GND") (pinfunction "GND_GND") (pintype "power_in"))
      (node (ref "D275") (pin "GND") (pinfunction "GND_GND") (pintype "power_in"))
      (node (ref "D276") (pin "GND") (pinfunction "GND_GND") (pintype "power_in"))
      (node (ref "D277") (pin "GND") (pinfunction "GND_GND") (pintype "power_in"))
      (node (ref "D278") (pin "GND") (pinfunction "GND_GND") (pintype "power_in"))
      (node (ref "D279") (pin "GND") (pinfunction "GND_GND") (pintype "power_in"))
      (node (ref "D28") (pin "GND") (pinfunction "GND_GND") (pintype "power_in"))
      (node (ref "D280") (pin "GND") (pinfunction "GND_GND") (pintype "power_in"))
      (node (ref "D281") (pin "GND") (pinfunction "GND_GND") (pintype "power_in"))
      (node (ref "D282") (pin "GND") (pinfunction "GND_GND") (pintype "power_in"))
      (node (ref "D283") (pin "GND") (pinfunction "GND_GND") (pintype "power_in"))
      (node (ref "D284") (pin "GND") (pinfunction "GND_GND") (pintype "power_in"))
      (node (ref "D285") (pin "GND") (pinfunction "GND_GND") (pintype "power_in"))
      (node (ref "D286") (pin "GND") (pinfunction "GND_GND") (pintype "power_in"))
      (node (ref "D287") (pin "GND") (pinfunction "GND_GND") (pintype "power_in"))
      (node (ref "D288") (pin "GND") (pinfunction "GND_GND") (pintype "power_in"))
      (node (ref "D289") (pin "GND") (pinfunction "GND_GND") (pintype "power_in"))
      (node (ref "D29") (pin "GND") (pinfunction "GND_GND") (pintype "power_in"))
      (node (ref "D290") (pin "GND") (pinfunction "GND_GND") (pintype "power_in"))
      (node (ref "D291") (pin "GND") (pinfunction "GND_GND") (pintype "power_in"))
      (node (ref "D292") (pin "GND") (pinfunction "GND_GND") (pintype "power_in"))
      (node (ref "D293") (pin "GND") (pinfunction "GND_GND") (pintype "power_in"))
      (node (ref "D294") (pin "GND") (pinfunction "GND_GND") (pintype "power_in"))
      (node (ref "D295") (pin "GND") (pinfunction "GND_GND") (pintype "power_in"))
      (node (ref "D296") (pin "GND") (pinfunction "GND_GND") (pintype "power_in"))
      (node (ref "D297") (pin "GND") (pinfunction "GND_GND") (pintype "power_in"))
      (node (ref "D298") (pin "GND") (pinfunction "GND_GND") (pintype "power_in"))
      (node (ref "D299") (pin "GND") (pinfunction "GND_GND") (pintype "power_in"))
      (node (ref "D3") (pin "GND") (pinfunction "GND_GND") (pintype "power_in"))
      (node (ref "D30") (pin "GND") (pinfunction "GND_GND") (pintype "power_in"))
      (node (ref "D300") (pin "GND") (pinfunction "GND_GND") (pintype "power_in"))
      (node (ref "D301") (pin "GND") (pinfunction "GND_GND") (pintype "power_in"))
      (node (ref "D302") (pin "GND") (pinfunction "GND_GND") (pintype "power_in"))
      (node (ref "D303") (pin "GND") (pinfunction "GND_GND") (pintype "power_in"))
      (node (ref "D304") (pin "GND") (pinfunction "GND_GND") (pintype "power_in"))
      (node (ref "D305") (pin "GND") (pinfunction "GND_GND") (pintype "power_in"))
      (node (ref "D306") (pin "GND") (pinfunction "GND_GND") (pintype "power_in"))
      (node (ref "D307") (pin "GND") (pinfunction "GND_GND") (pintype "power_in"))
      (node (ref "D308") (pin "GND") (pinfunction "GND_GND") (pintype "power_in"))
      (node (ref "D309") (pin "GND") (pinfunction "GND_GND") (pintype "power_in"))
      (node (ref "D31") (pin "GND") (pinfunction "GND_GND") (pintype "power_in"))
      (node (ref "D310") (pin "GND") (pinfunction "GND_GND") (pintype "power_in"))
      (node (ref "D311") (pin "GND") (pinfunction "GND_GND") (pintype "power_in"))
      (node (ref "D312") (pin "GND") (pinfunction "GND_GND") (pintype "power_in"))
      (node (ref "D313") (pin "GND") (pinfunction "GND_GND") (pintype "power_in"))
      (node (ref "D314") (pin "GND") (pinfunction "GND_GND") (pintype "power_in"))
      (node (ref "D315") (pin "GND") (pinfunction "GND_GND") (pintype "power_in"))
      (node (ref "D316") (pin "GND") (pinfunction "GND_GND") (pintype "power_in"))
      (node (ref "D317") (pin "GND") (pinfunction "GND_GND") (pintype "power_in"))
      (node (ref "D318") (pin "GND") (pinfunction "GND_GND") (pintype "power_in"))
      (node (ref "D319") (pin "GND") (pinfunction "GND_GND") (pintype "power_in"))
      (node (ref "D32") (pin "GND") (pinfunction "GND_GND") (pintype "power_in"))
      (node (ref "D320") (pin "GND") (pinfunction "GND_GND") (pintype "power_in"))
      (node (ref "D321") (pin "GND") (pinfunction "GND_GND") (pintype "power_in"))
      (node (ref "D322") (pin "GND") (pinfunction "GND_GND") (pintype "power_in"))
      (node (ref "D323") (pin "GND") (pinfunction "GND_GND") (pintype "power_in"))
      (node (ref "D324") (pin "GND") (pinfunction "GND_GND") (pintype "power_in"))
      (node (ref "D325") (pin "GND") (pinfunction "GND_GND") (pintype "power_in"))
      (node (ref "D326") (pin "GND") (pinfunction "GND_GND") (pintype "power_in"))
      (node (ref "D327") (pin "GND") (pinfunction "GND_GND") (pintype "power_in"))
      (node (ref "D328") (pin "GND") (pinfunction "GND_GND") (pintype "power_in"))
      (node (ref "D329") (pin "GND") (pinfunction "GND_GND") (pintype "power_in"))
      (node (ref "D33") (pin "GND") (pinfunction "GND_GND") (pintype "power_in"))
      (node (ref "D330") (pin "GND") (pinfunction "GND_GND") (pintype "power_in"))
      (node (ref "D331") (pin "GND") (pinfunction "GND_GND") (pintype "power_in"))
      (node (ref "D332") (pin "GND") (pinfunction "GND_GND") (pintype "power_in"))
      (node (ref "D333") (pin "GND") (pinfunction "GND_GND") (pintype "power_in"))
      (node (ref "D334") (pin "GND") (pinfunction "GND_GND") (pintype "power_in"))
      (node (ref "D335") (pin "GND") (pinfunction "GND_GND") (pintype "power_in"))
      (node (ref "D336") (pin "GND") (pinfunction "GND_GND") (pintype "power_in"))
      (node (ref "D337") (pin "GND") (pinfunction "GND_GND") (pintype "power_in"))
      (node (ref "D338") (pin "GND") (pinfunction "GND_GND") (pintype "power_in"))
      (node (ref "D339") (pin "GND") (pinfunction "GND_GND") (pintype "power_in"))
      (node (ref "D34") (pin "GND") (pinfunction "GND_GND") (pintype "power_in"))
      (node (ref "D340") (pin "GND") (pinfunction "GND_GND") (pintype "power_in"))
      (node (ref "D341") (pin "GND") (pinfunction "GND_GND") (pintype "power_in"))
      (node (ref "D342") (pin "GND") (pinfunction "GND_GND") (pintype "power_in"))
      (node (ref "D343") (pin "GND") (pinfunction "GND_GND") (pintype "power_in"))
      (node (ref "D344") (pin "GND") (pinfunction "GND_GND") (pintype "power_in"))
      (node (ref "D345") (pin "GND") (pinfunction "GND_GND") (pintype "power_in"))
      (node (ref "D346") (pin "GND") (pinfunction "GND_GND") (pintype "power_in"))
      (node (ref "D347") (pin "GND") (pinfunction "GND_GND") (pintype "power_in"))
      (node (ref "D348") (pin "GND") (pinfunction "GND_GND") (pintype "power_in"))
      (node (ref "D349") (pin "GND") (pinfunction "GND_GND") (pintype "power_in"))
      (node (ref "D35") (pin "GND") (pinfunction "GND_GND") (pintype "power_in"))
      (node (ref "D350") (pin "GND") (pinfunction "GND_GND") (pintype "power_in"))
      (node (ref "D351") (pin "GND") (pinfunction "GND_GND") (pintype "power_in"))
      (node (ref "D352") (pin "GND") (pinfunction "GND_GND") (pintype "power_in"))
      (node (ref "D353") (pin "GND") (pinfunction "GND_GND") (pintype "power_in"))
      (node (ref "D354") (pin "GND") (pinfunction "GND_GND") (pintype "power_in"))
      (node (ref "D355") (pin "GND") (pinfunction "GND_GND") (pintype "power_in"))
      (node (ref "D356") (pin "GND") (pinfunction "GND_GND") (pintype "power_in"))
      (node (ref "D357") (pin "GND") (pinfunction "GND_GND") (pintype "power_in"))
      (node (ref "D358") (pin "GND") (pinfunction "GND_GND") (pintype "power_in"))
      (node (ref "D359") (pin "GND") (pinfunction "GND_GND") (pintype "power_in"))
      (node (ref "D36") (pin "GND") (pinfunction "GND_GND") (pintype "power_in"))
      (node (ref "D360") (pin "GND") (pinfunction "GND_GND") (pintype "power_in"))
      (node (ref "D361") (pin "GND") (pinfunction "GND_GND") (pintype "power_in"))
      (node (ref "D362") (pin "GND") (pinfunction "GND_GND") (pintype "power_in"))
      (node (ref "D363") (pin "GND") (pinfunction "GND_GND") (pintype "power_in"))
      (node (ref "D364") (pin "GND") (pinfunction "GND_GND") (pintype "power_in"))
      (node (ref "D365") (pin "GND") (pinfunction "GND_GND") (pintype "power_in"))
      (node (ref "D366") (pin "GND") (pinfunction "GND_GND") (pintype "power_in"))
      (node (ref "D367") (pin "GND") (pinfunction "GND_GND") (pintype "power_in"))
      (node (ref "D368") (pin "GND") (pinfunction "GND_GND") (pintype "power_in"))
      (node (ref "D369") (pin "GND") (pinfunction "GND_GND") (pintype "power_in"))
      (node (ref "D37") (pin "GND") (pinfunction "GND_GND") (pintype "power_in"))
      (node (ref "D370") (pin "GND") (pinfunction "GND_GND") (pintype "power_in"))
      (node (ref "D371") (pin "GND") (pinfunction "GND_GND") (pintype "power_in"))
      (node (ref "D372") (pin "GND") (pinfunction "GND_GND") (pintype "power_in"))
      (node (ref "D373") (pin "GND") (pinfunction "GND_GND") (pintype "power_in"))
      (node (ref "D374") (pin "GND") (pinfunction "GND_GND") (pintype "power_in"))
      (node (ref "D375") (pin "GND") (pinfunction "GND_GND") (pintype "power_in"))
      (node (ref "D376") (pin "GND") (pinfunction "GND_GND") (pintype "power_in"))
      (node (ref "D377") (pin "GND") (pinfunction "GND_GND") (pintype "power_in"))
      (node (ref "D378") (pin "GND") (pinfunction "GND_GND") (pintype "power_in"))
      (node (ref "D379") (pin "GND") (pinfunction "GND_GND") (pintype "power_in"))
      (node (ref "D38") (pin "GND") (pinfunction "GND_GND") (pintype "power_in"))
      (node (ref "D380") (pin "GND") (pinfunction "GND_GND") (pintype "power_in"))
      (node (ref "D381") (pin "GND") (pinfunction "GND_GND") (pintype "power_in"))
      (node (ref "D382") (pin "GND") (pinfunction "GND_GND") (pintype "power_in"))
      (node (ref "D383") (pin "GND") (pinfunction "GND_GND") (pintype "power_in"))
      (node (ref "D384") (pin "GND") (pinfunction "GND_GND") (pintype "power_in"))
      (node (ref "D385") (pin "GND") (pinfunction "GND_GND") (pintype "power_in"))
      (node (ref "D386") (pin "GND") (pinfunction "GND_GND") (pintype "power_in"))
      (node (ref "D387") (pin "GND") (pinfunction "GND_GND") (pintype "power_in"))
      (node (ref "D388") (pin "GND") (pinfunction "GND_GND") (pintype "power_in"))
      (node (ref "D389") (pin "GND") (pinfunction "GND_GND") (pintype "power_in"))
      (node (ref "D39") (pin "GND") (pinfunction "GND_GND") (pintype "power_in"))
      (node (ref "D390") (pin "GND") (pinfunction "GND_GND") (pintype "power_in"))
      (node (ref "D391") (pin "GND") (pinfunction "GND_GND") (pintype "power_in"))
      (node (ref "D392") (pin "GND") (pinfunction "GND_GND") (pintype "power_in"))
      (node (ref "D393") (pin "GND") (pinfunction "GND_GND") (pintype "power_in"))
      (node (ref "D394") (pin "GND") (pinfunction "GND_GND") (pintype "power_in"))
      (node (ref "D395") (pin "GND") (pinfunction "GND_GND") (pintype "power_in"))
      (node (ref "D396") (pin "GND") (pinfunction "GND_GND") (pintype "power_in"))
      (node (ref "D397") (pin "GND") (pinfunction "GND_GND") (pintype "power_in"))
      (node (ref "D398") (pin "GND") (pinfunction "GND_GND") (pintype "power_in"))
      (node (ref "D399") (pin "GND") (pinfunction "GND_GND") (pintype "power_in"))
      (node (ref "D4") (pin "GND") (pinfunction "GND_GND") (pintype "power_in"))
      (node (ref "D40") (pin "GND") (pinfunction "GND_GND") (pintype "power_in"))
      (node (ref "D400") (pin "GND") (pinfunction "GND_GND") (pintype "power_in"))
      (node (ref "D401") (pin "GND") (pinfunction "GND_GND") (pintype "power_in"))
      (node (ref "D402") (pin "GND") (pinfunction "GND_GND") (pintype "power_in"))
      (node (ref "D403") (pin "GND") (pinfunction "GND_GND") (pintype "power_in"))
      (node (ref "D404") (pin "GND") (pinfunction "GND_GND") (pintype "power_in"))
      (node (ref "D405") (pin "GND") (pinfunction "GND_GND") (pintype "power_in"))
      (node (ref "D41") (pin "GND") (pinfunction "GND_GND") (pintype "power_in"))
      (node (ref "D42") (pin "GND") (pinfunction "GND_GND") (pintype "power_in"))
      (node (ref "D43") (pin "GND") (pinfunction "GND_GND") (pintype "power_in"))
      (node (ref "D44") (pin "GND") (pinfunction "GND_GND") (pintype "power_in"))
      (node (ref "D45") (pin "GND") (pinfunction "GND_GND") (pintype "power_in"))
      (node (ref "D46") (pin "GND") (pinfunction "GND_GND") (pintype "power_in"))
      (node (ref "D47") (pin "GND") (pinfunction "GND_GND") (pintype "power_in"))
      (node (ref "D48") (pin "GND") (pinfunction "GND_GND") (pintype "power_in"))
      (node (ref "D49") (pin "GND") (pinfunction "GND_GND") (pintype "power_in"))
      (node (ref "D5") (pin "GND") (pinfunction "GND_GND") (pintype "power_in"))
      (node (ref "D50") (pin "GND") (pinfunction "GND_GND") (pintype "power_in"))
      (node (ref "D51") (pin "GND") (pinfunction "GND_GND") (pintype "power_in"))
      (node (ref "D52") (pin "GND") (pinfunction "GND_GND") (pintype "power_in"))
      (node (ref "D53") (pin "GND") (pinfunction "GND_GND") (pintype "power_in"))
      (node (ref "D54") (pin "GND") (pinfunction "GND_GND") (pintype "power_in"))
      (node (ref "D55") (pin "GND") (pinfunction "GND_GND") (pintype "power_in"))
      (node (ref "D56") (pin "GND") (pinfunction "GND_GND") (pintype "power_in"))
      (node (ref "D57") (pin "GND") (pinfunction "GND_GND") (pintype "power_in"))
      (node (ref "D58") (pin "GND") (pinfunction "GND_GND") (pintype "power_in"))
      (node (ref "D59") (pin "GND") (pinfunction "GND_GND") (pintype "power_in"))
      (node (ref "D6") (pin "GND") (pinfunction "GND_GND") (pintype "power_in"))
      (node (ref "D60") (pin "GND") (pinfunction "GND_GND") (pintype "power_in"))
      (node (ref "D61") (pin "GND") (pinfunction "GND_GND") (pintype "power_in"))
      (node (ref "D62") (pin "GND") (pinfunction "GND_GND") (pintype "power_in"))
      (node (ref "D63") (pin "GND") (pinfunction "GND_GND") (pintype "power_in"))
      (node (ref "D64") (pin "GND") (pinfunction "GND_GND") (pintype "power_in"))
      (node (ref "D65") (pin "GND") (pinfunction "GND_GND") (pintype "power_in"))
      (node (ref "D66") (pin "GND") (pinfunction "GND_GND") (pintype "power_in"))
      (node (ref "D67") (pin "GND") (pinfunction "GND_GND") (pintype "power_in"))
      (node (ref "D68") (pin "GND") (pinfunction "GND_GND") (pintype "power_in"))
      (node (ref "D69") (pin "GND") (pinfunction "GND_GND") (pintype "power_in"))
      (node (ref "D7") (pin "GND") (pinfunction "GND_GND") (pintype "power_in"))
      (node (ref "D70") (pin "GND") (pinfunction "GND_GND") (pintype "power_in"))
      (node (ref "D71") (pin "GND") (pinfunction "GND_GND") (pintype "power_in"))
      (node (ref "D72") (pin "GND") (pinfunction "GND_GND") (pintype "power_in"))
      (node (ref "D73") (pin "GND") (pinfunction "GND_GND") (pintype "power_in"))
      (node (ref "D74") (pin "GND") (pinfunction "GND_GND") (pintype "power_in"))
      (node (ref "D75") (pin "GND") (pinfunction "GND_GND") (pintype "power_in"))
      (node (ref "D76") (pin "GND") (pinfunction "GND_GND") (pintype "power_in"))
      (node (ref "D77") (pin "GND") (pinfunction "GND_GND") (pintype "power_in"))
      (node (ref "D78") (pin "GND") (pinfunction "GND_GND") (pintype "power_in"))
      (node (ref "D79") (pin "GND") (pinfunction "GND_GND") (pintype "power_in"))
      (node (ref "D8") (pin "GND") (pinfunction "GND_GND") (pintype "power_in"))
      (node (ref "D80") (pin "GND") (pinfunction "GND_GND") (pintype "power_in"))
      (node (ref "D81") (pin "GND") (pinfunction "GND_GND") (pintype "power_in"))
      (node (ref "D82") (pin "GND") (pinfunction "GND_GND") (pintype "power_in"))
      (node (ref "D83") (pin "GND") (pinfunction "GND_GND") (pintype "power_in"))
      (node (ref "D84") (pin "GND") (pinfunction "GND_GND") (pintype "power_in"))
      (node (ref "D85") (pin "GND") (pinfunction "GND_GND") (pintype "power_in"))
      (node (ref "D86") (pin "GND") (pinfunction "GND_GND") (pintype "power_in"))
      (node (ref "D87") (pin "GND") (pinfunction "GND_GND") (pintype "power_in"))
      (node (ref "D88") (pin "GND") (pinfunction "GND_GND") (pintype "power_in"))
      (node (ref "D89") (pin "GND") (pinfunction "GND_GND") (pintype "power_in"))
      (node (ref "D9") (pin "GND") (pinfunction "GND_GND") (pintype "power_in"))
      (node (ref "D90") (pin "GND") (pinfunction "GND_GND") (pintype "power_in"))
      (node (ref "D91") (pin "GND") (pinfunction "GND_GND") (pintype "power_in"))
      (node (ref "D92") (pin "GND") (pinfunction "GND_GND") (pintype "power_in"))
      (node (ref "D93") (pin "GND") (pinfunction "GND_GND") (pintype "power_in"))
      (node (ref "D94") (pin "GND") (pinfunction "GND_GND") (pintype "power_in"))
      (node (ref "D95") (pin "GND") (pinfunction "GND_GND") (pintype "power_in"))
      (node (ref "D96") (pin "GND") (pinfunction "GND_GND") (pintype "power_in"))
      (node (ref "D97") (pin "GND") (pinfunction "GND_GND") (pintype "power_in"))
      (node (ref "D98") (pin "GND") (pinfunction "GND_GND") (pintype "power_in"))
      (node (ref "D99") (pin "GND") (pinfunction "GND_GND") (pintype "power_in"))
      (node (ref "JP1") (pin "5") (pinfunction "5_5") (pintype "passive"))
      (node (ref "JP1") (pin "6") (pinfunction "6_6") (pintype "passive"))
      (node (ref "JP1") (pin "7") (pinfunction "7_7") (pintype "passive"))
      (node (ref "JP2") (pin "5") (pinfunction "5_5") (pintype "passive"))
      (node (ref "JP2") (pin "6") (pinfunction "6_6") (pintype "passive"))
      (node (ref "JP2") (pin "7") (pinfunction "7_7") (pintype "passive"))
      (node (ref "Z1") (pin "2") (pinfunction "2_2") (pintype "passive"))
    )
    (net (code "155") (name "Net-(D76-PadDI)") (class "Default")
      (node (ref "D76") (pin "DI") (pinfunction "DI_DI") (pintype "input"))
      (node (ref "D77") (pin "DO") (pinfunction "DO_DO") (pintype "output"))
    )
    (net (code "156") (name "Net-(D77-PadDI)") (class "Default")
      (node (ref "D77") (pin "DI") (pinfunction "DI_DI") (pintype "input"))
      (node (ref "D78") (pin "DO") (pinfunction "DO_DO") (pintype "output"))
    )
    (net (code "157") (name "Net-(D78-PadDI)") (class "Default")
      (node (ref "D78") (pin "DI") (pinfunction "DI_DI") (pintype "input"))
      (node (ref "D79") (pin "DO") (pinfunction "DO_DO") (pintype "output"))
    )
    (net (code "158") (name "Net-(D79-PadDI)") (class "Default")
      (node (ref "D79") (pin "DI") (pinfunction "DI_DI") (pintype "input"))
      (node (ref "D80") (pin "DO") (pinfunction "DO_DO") (pintype "output"))
    )
    (net (code "159") (name "Net-(D80-PadDI)") (class "Default")
      (node (ref "D80") (pin "DI") (pinfunction "DI_DI") (pintype "input"))
      (node (ref "D81") (pin "DO") (pinfunction "DO_DO") (pintype "output"))
    )
    (net (code "160") (name "Net-(D81-PadDI)") (class "Default")
      (node (ref "D81") (pin "DI") (pinfunction "DI_DI") (pintype "input"))
      (node (ref "D82") (pin "DO") (pinfunction "DO_DO") (pintype "output"))
    )
    (net (code "161") (name "Net-(D82-PadDI)") (class "Default")
      (node (ref "D82") (pin "DI") (pinfunction "DI_DI") (pintype "input"))
      (node (ref "D83") (pin "DO") (pinfunction "DO_DO") (pintype "output"))
    )
    (net (code "162") (name "Net-(D83-PadDI)") (class "Default")
      (node (ref "D83") (pin "DI") (pinfunction "DI_DI") (pintype "input"))
      (node (ref "D84") (pin "DO") (pinfunction "DO_DO") (pintype "output"))
    )
    (net (code "163") (name "Net-(D84-PadDI)") (class "Default")
      (node (ref "D84") (pin "DI") (pinfunction "DI_DI") (pintype "input"))
      (node (ref "D85") (pin "DO") (pinfunction "DO_DO") (pintype "output"))
    )
    (net (code "164") (name "Net-(D85-PadDI)") (class "Default")
      (node (ref "D85") (pin "DI") (pinfunction "DI_DI") (pintype "input"))
      (node (ref "D86") (pin "DO") (pinfunction "DO_DO") (pintype "output"))
    )
    (net (code "165") (name "Net-(D86-PadDI)") (class "Default")
      (node (ref "D86") (pin "DI") (pinfunction "DI_DI") (pintype "input"))
      (node (ref "D87") (pin "DO") (pinfunction "DO_DO") (pintype "output"))
    )
    (net (code "166") (name "Net-(D87-PadDI)") (class "Default")
      (node (ref "D87") (pin "DI") (pinfunction "DI_DI") (pintype "input"))
      (node (ref "D88") (pin "DO") (pinfunction "DO_DO") (pintype "output"))
    )
    (net (code "167") (name "Net-(D88-PadDI)") (class "Default")
      (node (ref "D88") (pin "DI") (pinfunction "DI_DI") (pintype "input"))
      (node (ref "D89") (pin "DO") (pinfunction "DO_DO") (pintype "output"))
    )
    (net (code "168") (name "Net-(D89-PadDI)") (class "Default")
      (node (ref "D89") (pin "DI") (pinfunction "DI_DI") (pintype "input"))
      (node (ref "D90") (pin "DO") (pinfunction "DO_DO") (pintype "output"))
    )
    (net (code "169") (name "Net-(D91-PadDI)") (class "Default")
      (node (ref "D91") (pin "DI") (pinfunction "DI_DI") (pintype "input"))
      (node (ref "D92") (pin "DO") (pinfunction "DO_DO") (pintype "output"))
    )
    (net (code "170") (name "Net-(D92-PadDI)") (class "Default")
      (node (ref "D92") (pin "DI") (pinfunction "DI_DI") (pintype "input"))
      (node (ref "D93") (pin "DO") (pinfunction "DO_DO") (pintype "output"))
    )
    (net (code "171") (name "Net-(D93-PadDI)") (class "Default")
      (node (ref "D93") (pin "DI") (pinfunction "DI_DI") (pintype "input"))
      (node (ref "D94") (pin "DO") (pinfunction "DO_DO") (pintype "output"))
    )
    (net (code "172") (name "Net-(D94-PadDI)") (class "Default")
      (node (ref "D94") (pin "DI") (pinfunction "DI_DI") (pintype "input"))
      (node (ref "D95") (pin "DO") (pinfunction "DO_DO") (pintype "output"))
    )
    (net (code "173") (name "Net-(D95-PadDI)") (class "Default")
      (node (ref "D95") (pin "DI") (pinfunction "DI_DI") (pintype "input"))
      (node (ref "D96") (pin "DO") (pinfunction "DO_DO") (pintype "output"))
    )
    (net (code "174") (name "Net-(D96-PadDI)") (class "Default")
      (node (ref "D96") (pin "DI") (pinfunction "DI_DI") (pintype "input"))
      (node (ref "D97") (pin "DO") (pinfunction "DO_DO") (pintype "output"))
    )
    (net (code "175") (name "Net-(D97-PadDI)") (class "Default")
      (node (ref "D97") (pin "DI") (pinfunction "DI_DI") (pintype "input"))
      (node (ref "D98") (pin "DO") (pinfunction "DO_DO") (pintype "output"))
    )
    (net (code "176") (name "Net-(D98-PadDI)") (class "Default")
      (node (ref "D98") (pin "DI") (pinfunction "DI_DI") (pintype "input"))
      (node (ref "D99") (pin "DO") (pinfunction "DO_DO") (pintype "output"))
    )
    (net (code "177") (name "Net-(D100-PadDI)") (class "Default")
      (node (ref "D100") (pin "DI") (pinfunction "DI_DI") (pintype "input"))
      (node (ref "D101") (pin "DO") (pinfunction "DO_DO") (pintype "output"))
    )
    (net (code "178") (name "Net-(D100-PadDO)") (class "Default")
      (node (ref "D100") (pin "DO") (pinfunction "DO_DO") (pintype "output"))
      (node (ref "D99") (pin "DI") (pinfunction "DI_DI") (pintype "input"))
    )
    (net (code "179") (name "Net-(D101-PadDI)") (class "Default")
      (node (ref "D101") (pin "DI") (pinfunction "DI_DI") (pintype "input"))
      (node (ref "D102") (pin "DO") (pinfunction "DO_DO") (pintype "output"))
    )
    (net (code "180") (name "Net-(D102-PadDI)") (class "Default")
      (node (ref "D102") (pin "DI") (pinfunction "DI_DI") (pintype "input"))
      (node (ref "D103") (pin "DO") (pinfunction "DO_DO") (pintype "output"))
    )
    (net (code "181") (name "Net-(D103-PadDI)") (class "Default")
      (node (ref "D103") (pin "DI") (pinfunction "DI_DI") (pintype "input"))
      (node (ref "D104") (pin "DO") (pinfunction "DO_DO") (pintype "output"))
    )
    (net (code "182") (name "Net-(D104-PadDI)") (class "Default")
      (node (ref "D104") (pin "DI") (pinfunction "DI_DI") (pintype "input"))
      (node (ref "D105") (pin "DO") (pinfunction "DO_DO") (pintype "output"))
    )
    (net (code "183") (name "Net-(D106-PadDI)") (class "Default")
      (node (ref "D106") (pin "DI") (pinfunction "DI_DI") (pintype "input"))
      (node (ref "D107") (pin "DO") (pinfunction "DO_DO") (pintype "output"))
    )
    (net (code "184") (name "Net-(D107-PadDI)") (class "Default")
      (node (ref "D107") (pin "DI") (pinfunction "DI_DI") (pintype "input"))
      (node (ref "D108") (pin "DO") (pinfunction "DO_DO") (pintype "output"))
    )
    (net (code "185") (name "Net-(D108-PadDI)") (class "Default")
      (node (ref "D108") (pin "DI") (pinfunction "DI_DI") (pintype "input"))
      (node (ref "D109") (pin "DO") (pinfunction "DO_DO") (pintype "output"))
    )
    (net (code "186") (name "Net-(D109-PadDI)") (class "Default")
      (node (ref "D109") (pin "DI") (pinfunction "DI_DI") (pintype "input"))
      (node (ref "D110") (pin "DO") (pinfunction "DO_DO") (pintype "output"))
    )
    (net (code "187") (name "Net-(D110-PadDI)") (class "Default")
      (node (ref "D110") (pin "DI") (pinfunction "DI_DI") (pintype "input"))
      (node (ref "D111") (pin "DO") (pinfunction "DO_DO") (pintype "output"))
    )
    (net (code "188") (name "Net-(D111-PadDI)") (class "Default")
      (node (ref "D111") (pin "DI") (pinfunction "DI_DI") (pintype "input"))
      (node (ref "D112") (pin "DO") (pinfunction "DO_DO") (pintype "output"))
    )
    (net (code "189") (name "Net-(D112-PadDI)") (class "Default")
      (node (ref "D112") (pin "DI") (pinfunction "DI_DI") (pintype "input"))
      (node (ref "D113") (pin "DO") (pinfunction "DO_DO") (pintype "output"))
    )
    (net (code "190") (name "Net-(D113-PadDI)") (class "Default")
      (node (ref "D113") (pin "DI") (pinfunction "DI_DI") (pintype "input"))
      (node (ref "D114") (pin "DO") (pinfunction "DO_DO") (pintype "output"))
    )
    (net (code "191") (name "Net-(D114-PadDI)") (class "Default")
      (node (ref "D114") (pin "DI") (pinfunction "DI_DI") (pintype "input"))
      (node (ref "D115") (pin "DO") (pinfunction "DO_DO") (pintype "output"))
    )
    (net (code "192") (name "Net-(D115-PadDI)") (class "Default")
      (node (ref "D115") (pin "DI") (pinfunction "DI_DI") (pintype "input"))
      (node (ref "D116") (pin "DO") (pinfunction "DO_DO") (pintype "output"))
    )
    (net (code "193") (name "Net-(D116-PadDI)") (class "Default")
      (node (ref "D116") (pin "DI") (pinfunction "DI_DI") (pintype "input"))
      (node (ref "D117") (pin "DO") (pinfunction "DO_DO") (pintype "output"))
    )
    (net (code "194") (name "Net-(D117-PadDI)") (class "Default")
      (node (ref "D117") (pin "DI") (pinfunction "DI_DI") (pintype "input"))
      (node (ref "D118") (pin "DO") (pinfunction "DO_DO") (pintype "output"))
    )
    (net (code "195") (name "Net-(D118-PadDI)") (class "Default")
      (node (ref "D118") (pin "DI") (pinfunction "DI_DI") (pintype "input"))
      (node (ref "D119") (pin "DO") (pinfunction "DO_DO") (pintype "output"))
    )
    (net (code "196") (name "Net-(D119-PadDI)") (class "Default")
      (node (ref "D119") (pin "DI") (pinfunction "DI_DI") (pintype "input"))
      (node (ref "D120") (pin "DO") (pinfunction "DO_DO") (pintype "output"))
    )
    (net (code "197") (name "Net-(D121-PadDI)") (class "Default")
      (node (ref "D121") (pin "DI") (pinfunction "DI_DI") (pintype "input"))
      (node (ref "D122") (pin "DO") (pinfunction "DO_DO") (pintype "output"))
    )
    (net (code "198") (name "Net-(D122-PadDI)") (class "Default")
      (node (ref "D122") (pin "DI") (pinfunction "DI_DI") (pintype "input"))
      (node (ref "D123") (pin "DO") (pinfunction "DO_DO") (pintype "output"))
    )
    (net (code "199") (name "Net-(D123-PadDI)") (class "Default")
      (node (ref "D123") (pin "DI") (pinfunction "DI_DI") (pintype "input"))
      (node (ref "D124") (pin "DO") (pinfunction "DO_DO") (pintype "output"))
    )
    (net (code "200") (name "Net-(D124-PadDI)") (class "Default")
      (node (ref "D124") (pin "DI") (pinfunction "DI_DI") (pintype "input"))
      (node (ref "D125") (pin "DO") (pinfunction "DO_DO") (pintype "output"))
    )
    (net (code "201") (name "Net-(D125-PadDI)") (class "Default")
      (node (ref "D125") (pin "DI") (pinfunction "DI_DI") (pintype "input"))
      (node (ref "D126") (pin "DO") (pinfunction "DO_DO") (pintype "output"))
    )
    (net (code "202") (name "Net-(D126-PadDI)") (class "Default")
      (node (ref "D126") (pin "DI") (pinfunction "DI_DI") (pintype "input"))
      (node (ref "D127") (pin "DO") (pinfunction "DO_DO") (pintype "output"))
    )
    (net (code "203") (name "Net-(D127-PadDI)") (class "Default")
      (node (ref "D127") (pin "DI") (pinfunction "DI_DI") (pintype "input"))
      (node (ref "D128") (pin "DO") (pinfunction "DO_DO") (pintype "output"))
    )
    (net (code "204") (name "Net-(D128-PadDI)") (class "Default")
      (node (ref "D128") (pin "DI") (pinfunction "DI_DI") (pintype "input"))
      (node (ref "D129") (pin "DO") (pinfunction "DO_DO") (pintype "output"))
    )
    (net (code "205") (name "Net-(D129-PadDI)") (class "Default")
      (node (ref "D129") (pin "DI") (pinfunction "DI_DI") (pintype "input"))
      (node (ref "D130") (pin "DO") (pinfunction "DO_DO") (pintype "output"))
    )
    (net (code "206") (name "Net-(D130-PadDI)") (class "Default")
      (node (ref "D130") (pin "DI") (pinfunction "DI_DI") (pintype "input"))
      (node (ref "D131") (pin "DO") (pinfunction "DO_DO") (pintype "output"))
    )
    (net (code "207") (name "Net-(D131-PadDI)") (class "Default")
      (node (ref "D131") (pin "DI") (pinfunction "DI_DI") (pintype "input"))
      (node (ref "D132") (pin "DO") (pinfunction "DO_DO") (pintype "output"))
    )
    (net (code "208") (name "Net-(D132-PadDI)") (class "Default")
      (node (ref "D132") (pin "DI") (pinfunction "DI_DI") (pintype "input"))
      (node (ref "D133") (pin "DO") (pinfunction "DO_DO") (pintype "output"))
    )
    (net (code "209") (name "Net-(D133-PadDI)") (class "Default")
      (node (ref "D133") (pin "DI") (pinfunction "DI_DI") (pintype "input"))
      (node (ref "D134") (pin "DO") (pinfunction "DO_DO") (pintype "output"))
    )
    (net (code "210") (name "Net-(D134-PadDI)") (class "Default")
      (node (ref "D134") (pin "DI") (pinfunction "DI_DI") (pintype "input"))
      (node (ref "D135") (pin "DO") (pinfunction "DO_DO") (pintype "output"))
    )
    (net (code "211") (name "Net-(D136-PadDI)") (class "Default")
      (node (ref "D136") (pin "DI") (pinfunction "DI_DI") (pintype "input"))
      (node (ref "D137") (pin "DO") (pinfunction "DO_DO") (pintype "output"))
    )
    (net (code "212") (name "Net-(D137-PadDI)") (class "Default")
      (node (ref "D137") (pin "DI") (pinfunction "DI_DI") (pintype "input"))
      (node (ref "D138") (pin "DO") (pinfunction "DO_DO") (pintype "output"))
    )
    (net (code "213") (name "Net-(D138-PadDI)") (class "Default")
      (node (ref "D138") (pin "DI") (pinfunction "DI_DI") (pintype "input"))
      (node (ref "D139") (pin "DO") (pinfunction "DO_DO") (pintype "output"))
    )
    (net (code "214") (name "Net-(D139-PadDI)") (class "Default")
      (node (ref "D139") (pin "DI") (pinfunction "DI_DI") (pintype "input"))
      (node (ref "D140") (pin "DO") (pinfunction "DO_DO") (pintype "output"))
    )
    (net (code "215") (name "Net-(D140-PadDI)") (class "Default")
      (node (ref "D140") (pin "DI") (pinfunction "DI_DI") (pintype "input"))
      (node (ref "D141") (pin "DO") (pinfunction "DO_DO") (pintype "output"))
    )
    (net (code "216") (name "Net-(D141-PadDI)") (class "Default")
      (node (ref "D141") (pin "DI") (pinfunction "DI_DI") (pintype "input"))
      (node (ref "D142") (pin "DO") (pinfunction "DO_DO") (pintype "output"))
    )
    (net (code "217") (name "Net-(D142-PadDI)") (class "Default")
      (node (ref "D142") (pin "DI") (pinfunction "DI_DI") (pintype "input"))
      (node (ref "D143") (pin "DO") (pinfunction "DO_DO") (pintype "output"))
    )
    (net (code "218") (name "Net-(D143-PadDI)") (class "Default")
      (node (ref "D143") (pin "DI") (pinfunction "DI_DI") (pintype "input"))
      (node (ref "D144") (pin "DO") (pinfunction "DO_DO") (pintype "output"))
    )
    (net (code "219") (name "Net-(D144-PadDI)") (class "Default")
      (node (ref "D144") (pin "DI") (pinfunction "DI_DI") (pintype "input"))
      (node (ref "D145") (pin "DO") (pinfunction "DO_DO") (pintype "output"))
    )
    (net (code "220") (name "Net-(D145-PadDI)") (class "Default")
      (node (ref "D145") (pin "DI") (pinfunction "DI_DI") (pintype "input"))
      (node (ref "D146") (pin "DO") (pinfunction "DO_DO") (pintype "output"))
    )
    (net (code "221") (name "Net-(D146-PadDI)") (class "Default")
      (node (ref "D146") (pin "DI") (pinfunction "DI_DI") (pintype "input"))
      (node (ref "D147") (pin "DO") (pinfunction "DO_DO") (pintype "output"))
    )
    (net (code "222") (name "Net-(D147-PadDI)") (class "Default")
      (node (ref "D147") (pin "DI") (pinfunction "DI_DI") (pintype "input"))
      (node (ref "D148") (pin "DO") (pinfunction "DO_DO") (pintype "output"))
    )
    (net (code "223") (name "Net-(D148-PadDI)") (class "Default")
      (node (ref "D148") (pin "DI") (pinfunction "DI_DI") (pintype "input"))
      (node (ref "D149") (pin "DO") (pinfunction "DO_DO") (pintype "output"))
    )
    (net (code "224") (name "Net-(D149-PadDI)") (class "Default")
      (node (ref "D149") (pin "DI") (pinfunction "DI_DI") (pintype "input"))
      (node (ref "D150") (pin "DO") (pinfunction "DO_DO") (pintype "output"))
    )
    (net (code "225") (name "Net-(D151-PadDI)") (class "Default")
      (node (ref "D151") (pin "DI") (pinfunction "DI_DI") (pintype "input"))
      (node (ref "D152") (pin "DO") (pinfunction "DO_DO") (pintype "output"))
    )
    (net (code "226") (name "Net-(D152-PadDI)") (class "Default")
      (node (ref "D152") (pin "DI") (pinfunction "DI_DI") (pintype "input"))
      (node (ref "D153") (pin "DO") (pinfunction "DO_DO") (pintype "output"))
    )
    (net (code "227") (name "Net-(D153-PadDI)") (class "Default")
      (node (ref "D153") (pin "DI") (pinfunction "DI_DI") (pintype "input"))
      (node (ref "D154") (pin "DO") (pinfunction "DO_DO") (pintype "output"))
    )
    (net (code "228") (name "Net-(D154-PadDI)") (class "Default")
      (node (ref "D154") (pin "DI") (pinfunction "DI_DI") (pintype "input"))
      (node (ref "D155") (pin "DO") (pinfunction "DO_DO") (pintype "output"))
    )
    (net (code "229") (name "Net-(D155-PadDI)") (class "Default")
      (node (ref "D155") (pin "DI") (pinfunction "DI_DI") (pintype "input"))
      (node (ref "D156") (pin "DO") (pinfunction "DO_DO") (pintype "output"))
    )
    (net (code "230") (name "Net-(D156-PadDI)") (class "Default")
      (node (ref "D156") (pin "DI") (pinfunction "DI_DI") (pintype "input"))
      (node (ref "D157") (pin "DO") (pinfunction "DO_DO") (pintype "output"))
    )
    (net (code "231") (name "Net-(D157-PadDI)") (class "Default")
      (node (ref "D157") (pin "DI") (pinfunction "DI_DI") (pintype "input"))
      (node (ref "D158") (pin "DO") (pinfunction "DO_DO") (pintype "output"))
    )
    (net (code "232") (name "Net-(D158-PadDI)") (class "Default")
      (node (ref "D158") (pin "DI") (pinfunction "DI_DI") (pintype "input"))
      (node (ref "D159") (pin "DO") (pinfunction "DO_DO") (pintype "output"))
    )
    (net (code "233") (name "Net-(D159-PadDI)") (class "Default")
      (node (ref "D159") (pin "DI") (pinfunction "DI_DI") (pintype "input"))
      (node (ref "D160") (pin "DO") (pinfunction "DO_DO") (pintype "output"))
    )
    (net (code "234") (name "Net-(D160-PadDI)") (class "Default")
      (node (ref "D160") (pin "DI") (pinfunction "DI_DI") (pintype "input"))
      (node (ref "D161") (pin "DO") (pinfunction "DO_DO") (pintype "output"))
    )
    (net (code "235") (name "Net-(D161-PadDI)") (class "Default")
      (node (ref "D161") (pin "DI") (pinfunction "DI_DI") (pintype "input"))
      (node (ref "D162") (pin "DO") (pinfunction "DO_DO") (pintype "output"))
    )
    (net (code "236") (name "Net-(D162-PadDI)") (class "Default")
      (node (ref "D162") (pin "DI") (pinfunction "DI_DI") (pintype "input"))
      (node (ref "D163") (pin "DO") (pinfunction "DO_DO") (pintype "output"))
    )
    (net (code "237") (name "Net-(D163-PadDI)") (class "Default")
      (node (ref "D163") (pin "DI") (pinfunction "DI_DI") (pintype "input"))
      (node (ref "D164") (pin "DO") (pinfunction "DO_DO") (pintype "output"))
    )
    (net (code "238") (name "Net-(D164-PadDI)") (class "Default")
      (node (ref "D164") (pin "DI") (pinfunction "DI_DI") (pintype "input"))
      (node (ref "D165") (pin "DO") (pinfunction "DO_DO") (pintype "output"))
    )
    (net (code "239") (name "Net-(D166-PadDI)") (class "Default")
      (node (ref "D166") (pin "DI") (pinfunction "DI_DI") (pintype "input"))
      (node (ref "D167") (pin "DO") (pinfunction "DO_DO") (pintype "output"))
    )
    (net (code "240") (name "Net-(D167-PadDI)") (class "Default")
      (node (ref "D167") (pin "DI") (pinfunction "DI_DI") (pintype "input"))
      (node (ref "D168") (pin "DO") (pinfunction "DO_DO") (pintype "output"))
    )
    (net (code "241") (name "Net-(D168-PadDI)") (class "Default")
      (node (ref "D168") (pin "DI") (pinfunction "DI_DI") (pintype "input"))
      (node (ref "D169") (pin "DO") (pinfunction "DO_DO") (pintype "output"))
    )
    (net (code "242") (name "Net-(D169-PadDI)") (class "Default")
      (node (ref "D169") (pin "DI") (pinfunction "DI_DI") (pintype "input"))
      (node (ref "D170") (pin "DO") (pinfunction "DO_DO") (pintype "output"))
    )
    (net (code "243") (name "Net-(D170-PadDI)") (class "Default")
      (node (ref "D170") (pin "DI") (pinfunction "DI_DI") (pintype "input"))
      (node (ref "D171") (pin "DO") (pinfunction "DO_DO") (pintype "output"))
    )
    (net (code "244") (name "Net-(D171-PadDI)") (class "Default")
      (node (ref "D171") (pin "DI") (pinfunction "DI_DI") (pintype "input"))
      (node (ref "D172") (pin "DO") (pinfunction "DO_DO") (pintype "output"))
    )
    (net (code "245") (name "Net-(D172-PadDI)") (class "Default")
      (node (ref "D172") (pin "DI") (pinfunction "DI_DI") (pintype "input"))
      (node (ref "D173") (pin "DO") (pinfunction "DO_DO") (pintype "output"))
    )
    (net (code "246") (name "Net-(D173-PadDI)") (class "Default")
      (node (ref "D173") (pin "DI") (pinfunction "DI_DI") (pintype "input"))
      (node (ref "D174") (pin "DO") (pinfunction "DO_DO") (pintype "output"))
    )
    (net (code "247") (name "Net-(D174-PadDI)") (class "Default")
      (node (ref "D174") (pin "DI") (pinfunction "DI_DI") (pintype "input"))
      (node (ref "D175") (pin "DO") (pinfunction "DO_DO") (pintype "output"))
    )
    (net (code "248") (name "Net-(D175-PadDI)") (class "Default")
      (node (ref "D175") (pin "DI") (pinfunction "DI_DI") (pintype "input"))
      (node (ref "D176") (pin "DO") (pinfunction "DO_DO") (pintype "output"))
    )
    (net (code "249") (name "Net-(D176-PadDI)") (class "Default")
      (node (ref "D176") (pin "DI") (pinfunction "DI_DI") (pintype "input"))
      (node (ref "D177") (pin "DO") (pinfunction "DO_DO") (pintype "output"))
    )
    (net (code "250") (name "Net-(D177-PadDI)") (class "Default")
      (node (ref "D177") (pin "DI") (pinfunction "DI_DI") (pintype "input"))
      (node (ref "D178") (pin "DO") (pinfunction "DO_DO") (pintype "output"))
    )
    (net (code "251") (name "Net-(D178-PadDI)") (class "Default")
      (node (ref "D178") (pin "DI") (pinfunction "DI_DI") (pintype "input"))
      (node (ref "D179") (pin "DO") (pinfunction "DO_DO") (pintype "output"))
    )
    (net (code "252") (name "Net-(D179-PadDI)") (class "Default")
      (node (ref "D179") (pin "DI") (pinfunction "DI_DI") (pintype "input"))
      (node (ref "D180") (pin "DO") (pinfunction "DO_DO") (pintype "output"))
    )
    (net (code "253") (name "Net-(D181-PadDI)") (class "Default")
      (node (ref "D181") (pin "DI") (pinfunction "DI_DI") (pintype "input"))
      (node (ref "D182") (pin "DO") (pinfunction "DO_DO") (pintype "output"))
    )
    (net (code "254") (name "Net-(D182-PadDI)") (class "Default")
      (node (ref "D182") (pin "DI") (pinfunction "DI_DI") (pintype "input"))
      (node (ref "D183") (pin "DO") (pinfunction "DO_DO") (pintype "output"))
    )
    (net (code "255") (name "Net-(D183-PadDI)") (class "Default")
      (node (ref "D183") (pin "DI") (pinfunction "DI_DI") (pintype "input"))
      (node (ref "D184") (pin "DO") (pinfunction "DO_DO") (pintype "output"))
    )
    (net (code "256") (name "Net-(D184-PadDI)") (class "Default")
      (node (ref "D184") (pin "DI") (pinfunction "DI_DI") (pintype "input"))
      (node (ref "D185") (pin "DO") (pinfunction "DO_DO") (pintype "output"))
    )
    (net (code "257") (name "Net-(D185-PadDI)") (class "Default")
      (node (ref "D185") (pin "DI") (pinfunction "DI_DI") (pintype "input"))
      (node (ref "D186") (pin "DO") (pinfunction "DO_DO") (pintype "output"))
    )
    (net (code "258") (name "Net-(D186-PadDI)") (class "Default")
      (node (ref "D186") (pin "DI") (pinfunction "DI_DI") (pintype "input"))
      (node (ref "D187") (pin "DO") (pinfunction "DO_DO") (pintype "output"))
    )
    (net (code "259") (name "Net-(D187-PadDI)") (class "Default")
      (node (ref "D187") (pin "DI") (pinfunction "DI_DI") (pintype "input"))
      (node (ref "D188") (pin "DO") (pinfunction "DO_DO") (pintype "output"))
    )
    (net (code "260") (name "Net-(D188-PadDI)") (class "Default")
      (node (ref "D188") (pin "DI") (pinfunction "DI_DI") (pintype "input"))
      (node (ref "D189") (pin "DO") (pinfunction "DO_DO") (pintype "output"))
    )
    (net (code "261") (name "Net-(D189-PadDI)") (class "Default")
      (node (ref "D189") (pin "DI") (pinfunction "DI_DI") (pintype "input"))
      (node (ref "D190") (pin "DO") (pinfunction "DO_DO") (pintype "output"))
    )
    (net (code "262") (name "Net-(D190-PadDI)") (class "Default")
      (node (ref "D190") (pin "DI") (pinfunction "DI_DI") (pintype "input"))
      (node (ref "D191") (pin "DO") (pinfunction "DO_DO") (pintype "output"))
    )
    (net (code "263") (name "Net-(D191-PadDI)") (class "Default")
      (node (ref "D191") (pin "DI") (pinfunction "DI_DI") (pintype "input"))
      (node (ref "D192") (pin "DO") (pinfunction "DO_DO") (pintype "output"))
    )
    (net (code "264") (name "Net-(D192-PadDI)") (class "Default")
      (node (ref "D192") (pin "DI") (pinfunction "DI_DI") (pintype "input"))
      (node (ref "D193") (pin "DO") (pinfunction "DO_DO") (pintype "output"))
    )
    (net (code "265") (name "Net-(D193-PadDI)") (class "Default")
      (node (ref "D193") (pin "DI") (pinfunction "DI_DI") (pintype "input"))
      (node (ref "D194") (pin "DO") (pinfunction "DO_DO") (pintype "output"))
    )
    (net (code "266") (name "Net-(D194-PadDI)") (class "Default")
      (node (ref "D194") (pin "DI") (pinfunction "DI_DI") (pintype "input"))
      (node (ref "D195") (pin "DO") (pinfunction "DO_DO") (pintype "output"))
    )
    (net (code "267") (name "Net-(D196-PadDI)") (class "Default")
      (node (ref "D196") (pin "DI") (pinfunction "DI_DI") (pintype "input"))
      (node (ref "D197") (pin "DO") (pinfunction "DO_DO") (pintype "output"))
    )
    (net (code "268") (name "Net-(D197-PadDI)") (class "Default")
      (node (ref "D197") (pin "DI") (pinfunction "DI_DI") (pintype "input"))
      (node (ref "D198") (pin "DO") (pinfunction "DO_DO") (pintype "output"))
    )
    (net (code "269") (name "Net-(D198-PadDI)") (class "Default")
      (node (ref "D198") (pin "DI") (pinfunction "DI_DI") (pintype "input"))
      (node (ref "D199") (pin "DO") (pinfunction "DO_DO") (pintype "output"))
    )
    (net (code "270") (name "Net-(D199-PadDI)") (class "Default")
      (node (ref "D199") (pin "DI") (pinfunction "DI_DI") (pintype "input"))
      (node (ref "D200") (pin "DO") (pinfunction "DO_DO") (pintype "output"))
    )
    (net (code "271") (name "Net-(D200-PadDI)") (class "Default")
      (node (ref "D200") (pin "DI") (pinfunction "DI_DI") (pintype "input"))
      (node (ref "D201") (pin "DO") (pinfunction "DO_DO") (pintype "output"))
    )
    (net (code "272") (name "Net-(D201-PadDI)") (class "Default")
      (node (ref "D201") (pin "DI") (pinfunction "DI_DI") (pintype "input"))
      (node (ref "D202") (pin "DO") (pinfunction "DO_DO") (pintype "output"))
    )
    (net (code "273") (name "Net-(D202-PadDI)") (class "Default")
      (node (ref "D202") (pin "DI") (pinfunction "DI_DI") (pintype "input"))
      (node (ref "D203") (pin "DO") (pinfunction "DO_DO") (pintype "output"))
    )
    (net (code "274") (name "Net-(D203-PadDI)") (class "Default")
      (node (ref "D203") (pin "DI") (pinfunction "DI_DI") (pintype "input"))
      (node (ref "D204") (pin "DO") (pinfunction "DO_DO") (pintype "output"))
    )
    (net (code "275") (name "Net-(D204-PadDI)") (class "Default")
      (node (ref "D204") (pin "DI") (pinfunction "DI_DI") (pintype "input"))
      (node (ref "D205") (pin "DO") (pinfunction "DO_DO") (pintype "output"))
    )
    (net (code "276") (name "Net-(D205-PadDI)") (class "Default")
      (node (ref "D205") (pin "DI") (pinfunction "DI_DI") (pintype "input"))
      (node (ref "D206") (pin "DO") (pinfunction "DO_DO") (pintype "output"))
    )
    (net (code "277") (name "Net-(D206-PadDI)") (class "Default")
      (node (ref "D206") (pin "DI") (pinfunction "DI_DI") (pintype "input"))
      (node (ref "D207") (pin "DO") (pinfunction "DO_DO") (pintype "output"))
    )
    (net (code "278") (name "Net-(D207-PadDI)") (class "Default")
      (node (ref "D207") (pin "DI") (pinfunction "DI_DI") (pintype "input"))
      (node (ref "D208") (pin "DO") (pinfunction "DO_DO") (pintype "output"))
    )
    (net (code "279") (name "Net-(D208-PadDI)") (class "Default")
      (node (ref "D208") (pin "DI") (pinfunction "DI_DI") (pintype "input"))
      (node (ref "D209") (pin "DO") (pinfunction "DO_DO") (pintype "output"))
    )
    (net (code "280") (name "Net-(D209-PadDI)") (class "Default")
      (node (ref "D209") (pin "DI") (pinfunction "DI_DI") (pintype "input"))
      (node (ref "D210") (pin "DO") (pinfunction "DO_DO") (pintype "output"))
    )
    (net (code "281") (name "Net-(D211-PadDI)") (class "Default")
      (node (ref "D211") (pin "DI") (pinfunction "DI_DI") (pintype "input"))
      (node (ref "D212") (pin "DO") (pinfunction "DO_DO") (pintype "output"))
    )
    (net (code "282") (name "Net-(D212-PadDI)") (class "Default")
      (node (ref "D212") (pin "DI") (pinfunction "DI_DI") (pintype "input"))
      (node (ref "D213") (pin "DO") (pinfunction "DO_DO") (pintype "output"))
    )
    (net (code "283") (name "Net-(D213-PadDI)") (class "Default")
      (node (ref "D213") (pin "DI") (pinfunction "DI_DI") (pintype "input"))
      (node (ref "D214") (pin "DO") (pinfunction "DO_DO") (pintype "output"))
    )
    (net (code "284") (name "Net-(D214-PadDI)") (class "Default")
      (node (ref "D214") (pin "DI") (pinfunction "DI_DI") (pintype "input"))
      (node (ref "D215") (pin "DO") (pinfunction "DO_DO") (pintype "output"))
    )
    (net (code "285") (name "Net-(D215-PadDI)") (class "Default")
      (node (ref "D215") (pin "DI") (pinfunction "DI_DI") (pintype "input"))
      (node (ref "D216") (pin "DO") (pinfunction "DO_DO") (pintype "output"))
    )
    (net (code "286") (name "Net-(D216-PadDI)") (class "Default")
      (node (ref "D216") (pin "DI") (pinfunction "DI_DI") (pintype "input"))
      (node (ref "D217") (pin "DO") (pinfunction "DO_DO") (pintype "output"))
    )
    (net (code "287") (name "Net-(D217-PadDI)") (class "Default")
      (node (ref "D217") (pin "DI") (pinfunction "DI_DI") (pintype "input"))
      (node (ref "D218") (pin "DO") (pinfunction "DO_DO") (pintype "output"))
    )
    (net (code "288") (name "Net-(D218-PadDI)") (class "Default")
      (node (ref "D218") (pin "DI") (pinfunction "DI_DI") (pintype "input"))
      (node (ref "D219") (pin "DO") (pinfunction "DO_DO") (pintype "output"))
    )
    (net (code "289") (name "Net-(D219-PadDI)") (class "Default")
      (node (ref "D219") (pin "DI") (pinfunction "DI_DI") (pintype "input"))
      (node (ref "D220") (pin "DO") (pinfunction "DO_DO") (pintype "output"))
    )
    (net (code "290") (name "Net-(D220-PadDI)") (class "Default")
      (node (ref "D220") (pin "DI") (pinfunction "DI_DI") (pintype "input"))
      (node (ref "D221") (pin "DO") (pinfunction "DO_DO") (pintype "output"))
    )
    (net (code "291") (name "Net-(D221-PadDI)") (class "Default")
      (node (ref "D221") (pin "DI") (pinfunction "DI_DI") (pintype "input"))
      (node (ref "D222") (pin "DO") (pinfunction "DO_DO") (pintype "output"))
    )
    (net (code "292") (name "Net-(D222-PadDI)") (class "Default")
      (node (ref "D222") (pin "DI") (pinfunction "DI_DI") (pintype "input"))
      (node (ref "D223") (pin "DO") (pinfunction "DO_DO") (pintype "output"))
    )
    (net (code "293") (name "Net-(D223-PadDI)") (class "Default")
      (node (ref "D223") (pin "DI") (pinfunction "DI_DI") (pintype "input"))
      (node (ref "D224") (pin "DO") (pinfunction "DO_DO") (pintype "output"))
    )
    (net (code "294") (name "Net-(D224-PadDI)") (class "Default")
      (node (ref "D224") (pin "DI") (pinfunction "DI_DI") (pintype "input"))
      (node (ref "D225") (pin "DO") (pinfunction "DO_DO") (pintype "output"))
    )
    (net (code "295") (name "Net-(D226-PadDI)") (class "Default")
      (node (ref "D226") (pin "DI") (pinfunction "DI_DI") (pintype "input"))
      (node (ref "D227") (pin "DO") (pinfunction "DO_DO") (pintype "output"))
    )
    (net (code "296") (name "Net-(D227-PadDI)") (class "Default")
      (node (ref "D227") (pin "DI") (pinfunction "DI_DI") (pintype "input"))
      (node (ref "D228") (pin "DO") (pinfunction "DO_DO") (pintype "output"))
    )
    (net (code "297") (name "Net-(D228-PadDI)") (class "Default")
      (node (ref "D228") (pin "DI") (pinfunction "DI_DI") (pintype "input"))
      (node (ref "D229") (pin "DO") (pinfunction "DO_DO") (pintype "output"))
    )
    (net (code "298") (name "Net-(D229-PadDI)") (class "Default")
      (node (ref "D229") (pin "DI") (pinfunction "DI_DI") (pintype "input"))
      (node (ref "D230") (pin "DO") (pinfunction "DO_DO") (pintype "output"))
    )
    (net (code "299") (name "Net-(D230-PadDI)") (class "Default")
      (node (ref "D230") (pin "DI") (pinfunction "DI_DI") (pintype "input"))
      (node (ref "D231") (pin "DO") (pinfunction "DO_DO") (pintype "output"))
    )
    (net (code "300") (name "Net-(D231-PadDI)") (class "Default")
      (node (ref "D231") (pin "DI") (pinfunction "DI_DI") (pintype "input"))
      (node (ref "D232") (pin "DO") (pinfunction "DO_DO") (pintype "output"))
    )
    (net (code "301") (name "Net-(D232-PadDI)") (class "Default")
      (node (ref "D232") (pin "DI") (pinfunction "DI_DI") (pintype "input"))
      (node (ref "D233") (pin "DO") (pinfunction "DO_DO") (pintype "output"))
    )
    (net (code "302") (name "Net-(D233-PadDI)") (class "Default")
      (node (ref "D233") (pin "DI") (pinfunction "DI_DI") (pintype "input"))
      (node (ref "D234") (pin "DO") (pinfunction "DO_DO") (pintype "output"))
    )
    (net (code "303") (name "Net-(D234-PadDI)") (class "Default")
      (node (ref "D234") (pin "DI") (pinfunction "DI_DI") (pintype "input"))
      (node (ref "D235") (pin "DO") (pinfunction "DO_DO") (pintype "output"))
    )
    (net (code "304") (name "Net-(D235-PadDI)") (class "Default")
      (node (ref "D235") (pin "DI") (pinfunction "DI_DI") (pintype "input"))
      (node (ref "D236") (pin "DO") (pinfunction "DO_DO") (pintype "output"))
    )
    (net (code "305") (name "Net-(D236-PadDI)") (class "Default")
      (node (ref "D236") (pin "DI") (pinfunction "DI_DI") (pintype "input"))
      (node (ref "D237") (pin "DO") (pinfunction "DO_DO") (pintype "output"))
    )
    (net (code "306") (name "Net-(D237-PadDI)") (class "Default")
      (node (ref "D237") (pin "DI") (pinfunction "DI_DI") (pintype "input"))
      (node (ref "D238") (pin "DO") (pinfunction "DO_DO") (pintype "output"))
    )
    (net (code "307") (name "Net-(D238-PadDI)") (class "Default")
      (node (ref "D238") (pin "DI") (pinfunction "DI_DI") (pintype "input"))
      (node (ref "D239") (pin "DO") (pinfunction "DO_DO") (pintype "output"))
    )
    (net (code "308") (name "Net-(D239-PadDI)") (class "Default")
      (node (ref "D239") (pin "DI") (pinfunction "DI_DI") (pintype "input"))
      (node (ref "D240") (pin "DO") (pinfunction "DO_DO") (pintype "output"))
    )
    (net (code "309") (name "Net-(D241-PadDI)") (class "Default")
      (node (ref "D241") (pin "DI") (pinfunction "DI_DI") (pintype "input"))
      (node (ref "D242") (pin "DO") (pinfunction "DO_DO") (pintype "output"))
    )
    (net (code "310") (name "Net-(D242-PadDI)") (class "Default")
      (node (ref "D242") (pin "DI") (pinfunction "DI_DI") (pintype "input"))
      (node (ref "D243") (pin "DO") (pinfunction "DO_DO") (pintype "output"))
    )
    (net (code "311") (name "Net-(D243-PadDI)") (class "Default")
      (node (ref "D243") (pin "DI") (pinfunction "DI_DI") (pintype "input"))
      (node (ref "D244") (pin "DO") (pinfunction "DO_DO") (pintype "output"))
    )
    (net (code "312") (name "Net-(D244-PadDI)") (class "Default")
      (node (ref "D244") (pin "DI") (pinfunction "DI_DI") (pintype "input"))
      (node (ref "D245") (pin "DO") (pinfunction "DO_DO") (pintype "output"))
    )
    (net (code "313") (name "Net-(D245-PadDI)") (class "Default")
      (node (ref "D245") (pin "DI") (pinfunction "DI_DI") (pintype "input"))
      (node (ref "D246") (pin "DO") (pinfunction "DO_DO") (pintype "output"))
    )
    (net (code "314") (name "Net-(D246-PadDI)") (class "Default")
      (node (ref "D246") (pin "DI") (pinfunction "DI_DI") (pintype "input"))
      (node (ref "D247") (pin "DO") (pinfunction "DO_DO") (pintype "output"))
    )
    (net (code "315") (name "Net-(D247-PadDI)") (class "Default")
      (node (ref "D247") (pin "DI") (pinfunction "DI_DI") (pintype "input"))
      (node (ref "D248") (pin "DO") (pinfunction "DO_DO") (pintype "output"))
    )
    (net (code "316") (name "Net-(D248-PadDI)") (class "Default")
      (node (ref "D248") (pin "DI") (pinfunction "DI_DI") (pintype "input"))
      (node (ref "D249") (pin "DO") (pinfunction "DO_DO") (pintype "output"))
    )
    (net (code "317") (name "Net-(D249-PadDI)") (class "Default")
      (node (ref "D249") (pin "DI") (pinfunction "DI_DI") (pintype "input"))
      (node (ref "D250") (pin "DO") (pinfunction "DO_DO") (pintype "output"))
    )
    (net (code "318") (name "Net-(D250-PadDI)") (class "Default")
      (node (ref "D250") (pin "DI") (pinfunction "DI_DI") (pintype "input"))
      (node (ref "D251") (pin "DO") (pinfunction "DO_DO") (pintype "output"))
    )
    (net (code "319") (name "Net-(D251-PadDI)") (class "Default")
      (node (ref "D251") (pin "DI") (pinfunction "DI_DI") (pintype "input"))
      (node (ref "D252") (pin "DO") (pinfunction "DO_DO") (pintype "output"))
    )
    (net (code "320") (name "Net-(D252-PadDI)") (class "Default")
      (node (ref "D252") (pin "DI") (pinfunction "DI_DI") (pintype "input"))
      (node (ref "D253") (pin "DO") (pinfunction "DO_DO") (pintype "output"))
    )
    (net (code "321") (name "Net-(D253-PadDI)") (class "Default")
      (node (ref "D253") (pin "DI") (pinfunction "DI_DI") (pintype "input"))
      (node (ref "D254") (pin "DO") (pinfunction "DO_DO") (pintype "output"))
    )
    (net (code "322") (name "Net-(D254-PadDI)") (class "Default")
      (node (ref "D254") (pin "DI") (pinfunction "DI_DI") (pintype "input"))
      (node (ref "D255") (pin "DO") (pinfunction "DO_DO") (pintype "output"))
    )
    (net (code "323") (name "Net-(D316-PadDI)") (class "Default")
      (node (ref "D316") (pin "DI") (pinfunction "DI_DI") (pintype "input"))
      (node (ref "D317") (pin "DO") (pinfunction "DO_DO") (pintype "output"))
    )
    (net (code "324") (name "Net-(D317-PadDI)") (class "Default")
      (node (ref "D317") (pin "DI") (pinfunction "DI_DI") (pintype "input"))
      (node (ref "D318") (pin "DO") (pinfunction "DO_DO") (pintype "output"))
    )
    (net (code "325") (name "Net-(D318-PadDI)") (class "Default")
      (node (ref "D318") (pin "DI") (pinfunction "DI_DI") (pintype "input"))
      (node (ref "D319") (pin "DO") (pinfunction "DO_DO") (pintype "output"))
    )
    (net (code "326") (name "Net-(D319-PadDI)") (class "Default")
      (node (ref "D319") (pin "DI") (pinfunction "DI_DI") (pintype "input"))
      (node (ref "D320") (pin "DO") (pinfunction "DO_DO") (pintype "output"))
    )
    (net (code "327") (name "Net-(D320-PadDI)") (class "Default")
      (node (ref "D320") (pin "DI") (pinfunction "DI_DI") (pintype "input"))
      (node (ref "D321") (pin "DO") (pinfunction "DO_DO") (pintype "output"))
    )
    (net (code "328") (name "Net-(D321-PadDI)") (class "Default")
      (node (ref "D321") (pin "DI") (pinfunction "DI_DI") (pintype "input"))
      (node (ref "D322") (pin "DO") (pinfunction "DO_DO") (pintype "output"))
    )
    (net (code "329") (name "Net-(D322-PadDI)") (class "Default")
      (node (ref "D322") (pin "DI") (pinfunction "DI_DI") (pintype "input"))
      (node (ref "D323") (pin "DO") (pinfunction "DO_DO") (pintype "output"))
    )
    (net (code "330") (name "Net-(D323-PadDI)") (class "Default")
      (node (ref "D323") (pin "DI") (pinfunction "DI_DI") (pintype "input"))
      (node (ref "D324") (pin "DO") (pinfunction "DO_DO") (pintype "output"))
    )
    (net (code "331") (name "Net-(D324-PadDI)") (class "Default")
      (node (ref "D324") (pin "DI") (pinfunction "DI_DI") (pintype "input"))
      (node (ref "D325") (pin "DO") (pinfunction "DO_DO") (pintype "output"))
    )
    (net (code "332") (name "Net-(D325-PadDI)") (class "Default")
      (node (ref "D325") (pin "DI") (pinfunction "DI_DI") (pintype "input"))
      (node (ref "D326") (pin "DO") (pinfunction "DO_DO") (pintype "output"))
    )
    (net (code "333") (name "Net-(D326-PadDI)") (class "Default")
      (node (ref "D326") (pin "DI") (pinfunction "DI_DI") (pintype "input"))
      (node (ref "D327") (pin "DO") (pinfunction "DO_DO") (pintype "output"))
    )
    (net (code "334") (name "Net-(D327-PadDI)") (class "Default")
      (node (ref "D327") (pin "DI") (pinfunction "DI_DI") (pintype "input"))
      (node (ref "D328") (pin "DO") (pinfunction "DO_DO") (pintype "output"))
    )
    (net (code "335") (name "Net-(D328-PadDI)") (class "Default")
      (node (ref "D328") (pin "DI") (pinfunction "DI_DI") (pintype "input"))
      (node (ref "D329") (pin "DO") (pinfunction "DO_DO") (pintype "output"))
    )
    (net (code "336") (name "Net-(D329-PadDI)") (class "Default")
      (node (ref "D329") (pin "DI") (pinfunction "DI_DI") (pintype "input"))
      (node (ref "D330") (pin "DO") (pinfunction "DO_DO") (pintype "output"))
    )
    (net (code "337") (name "Net-(D331-PadDI)") (class "Default")
      (node (ref "D331") (pin "DI") (pinfunction "DI_DI") (pintype "input"))
      (node (ref "D332") (pin "DO") (pinfunction "DO_DO") (pintype "output"))
    )
    (net (code "338") (name "Net-(D332-PadDI)") (class "Default")
      (node (ref "D332") (pin "DI") (pinfunction "DI_DI") (pintype "input"))
      (node (ref "D333") (pin "DO") (pinfunction "DO_DO") (pintype "output"))
    )
    (net (code "339") (name "Net-(D333-PadDI)") (class "Default")
      (node (ref "D333") (pin "DI") (pinfunction "DI_DI") (pintype "input"))
      (node (ref "D334") (pin "DO") (pinfunction "DO_DO") (pintype "output"))
    )
    (net (code "340") (name "Net-(D334-PadDI)") (class "Default")
      (node (ref "D334") (pin "DI") (pinfunction "DI_DI") (pintype "input"))
      (node (ref "D335") (pin "DO") (pinfunction "DO_DO") (pintype "output"))
    )
    (net (code "341") (name "Net-(D335-PadDI)") (class "Default")
      (node (ref "D335") (pin "DI") (pinfunction "DI_DI") (pintype "input"))
      (node (ref "D336") (pin "DO") (pinfunction "DO_DO") (pintype "output"))
    )
    (net (code "342") (name "Net-(D336-PadDI)") (class "Default")
      (node (ref "D336") (pin "DI") (pinfunction "DI_DI") (pintype "input"))
      (node (ref "D337") (pin "DO") (pinfunction "DO_DO") (pintype "output"))
    )
    (net (code "343") (name "Net-(D337-PadDI)") (class "Default")
      (node (ref "D337") (pin "DI") (pinfunction "DI_DI") (pintype "input"))
      (node (ref "D338") (pin "DO") (pinfunction "DO_DO") (pintype "output"))
    )
    (net (code "344") (name "Net-(D338-PadDI)") (class "Default")
      (node (ref "D338") (pin "DI") (pinfunction "DI_DI") (pintype "input"))
      (node (ref "D339") (pin "DO") (pinfunction "DO_DO") (pintype "output"))
    )
    (net (code "345") (name "Net-(D339-PadDI)") (class "Default")
      (node (ref "D339") (pin "DI") (pinfunction "DI_DI") (pintype "input"))
      (node (ref "D340") (pin "DO") (pinfunction "DO_DO") (pintype "output"))
    )
    (net (code "346") (name "Net-(D340-PadDI)") (class "Default")
      (node (ref "D340") (pin "DI") (pinfunction "DI_DI") (pintype "input"))
      (node (ref "D341") (pin "DO") (pinfunction "DO_DO") (pintype "output"))
    )
    (net (code "347") (name "Net-(D341-PadDI)") (class "Default")
      (node (ref "D341") (pin "DI") (pinfunction "DI_DI") (pintype "input"))
      (node (ref "D342") (pin "DO") (pinfunction "DO_DO") (pintype "output"))
    )
    (net (code "348") (name "Net-(D342-PadDI)") (class "Default")
      (node (ref "D342") (pin "DI") (pinfunction "DI_DI") (pintype "input"))
      (node (ref "D343") (pin "DO") (pinfunction "DO_DO") (pintype "output"))
    )
    (net (code "349") (name "Net-(D343-PadDI)") (class "Default")
      (node (ref "D343") (pin "DI") (pinfunction "DI_DI") (pintype "input"))
      (node (ref "D344") (pin "DO") (pinfunction "DO_DO") (pintype "output"))
    )
    (net (code "350") (name "Net-(D344-PadDI)") (class "Default")
      (node (ref "D344") (pin "DI") (pinfunction "DI_DI") (pintype "input"))
      (node (ref "D345") (pin "DO") (pinfunction "DO_DO") (pintype "output"))
    )
    (net (code "351") (name "Net-(D346-PadDI)") (class "Default")
      (node (ref "D346") (pin "DI") (pinfunction "DI_DI") (pintype "input"))
      (node (ref "D347") (pin "DO") (pinfunction "DO_DO") (pintype "output"))
    )
    (net (code "352") (name "Net-(D347-PadDI)") (class "Default")
      (node (ref "D347") (pin "DI") (pinfunction "DI_DI") (pintype "input"))
      (node (ref "D348") (pin "DO") (pinfunction "DO_DO") (pintype "output"))
    )
    (net (code "353") (name "Net-(D348-PadDI)") (class "Default")
      (node (ref "D348") (pin "DI") (pinfunction "DI_DI") (pintype "input"))
      (node (ref "D349") (pin "DO") (pinfunction "DO_DO") (pintype "output"))
    )
    (net (code "354") (name "Net-(D349-PadDI)") (class "Default")
      (node (ref "D349") (pin "DI") (pinfunction "DI_DI") (pintype "input"))
      (node (ref "D350") (pin "DO") (pinfunction "DO_DO") (pintype "output"))
    )
    (net (code "355") (name "Net-(D350-PadDI)") (class "Default")
      (node (ref "D350") (pin "DI") (pinfunction "DI_DI") (pintype "input"))
      (node (ref "D351") (pin "DO") (pinfunction "DO_DO") (pintype "output"))
    )
    (net (code "356") (name "Net-(D351-PadDI)") (class "Default")
      (node (ref "D351") (pin "DI") (pinfunction "DI_DI") (pintype "input"))
      (node (ref "D352") (pin "DO") (pinfunction "DO_DO") (pintype "output"))
    )
    (net (code "357") (name "Net-(D352-PadDI)") (class "Default")
      (node (ref "D352") (pin "DI") (pinfunction "DI_DI") (pintype "input"))
      (node (ref "D353") (pin "DO") (pinfunction "DO_DO") (pintype "output"))
    )
    (net (code "358") (name "Net-(D353-PadDI)") (class "Default")
      (node (ref "D353") (pin "DI") (pinfunction "DI_DI") (pintype "input"))
      (node (ref "D354") (pin "DO") (pinfunction "DO_DO") (pintype "output"))
    )
    (net (code "359") (name "Net-(D354-PadDI)") (class "Default")
      (node (ref "D354") (pin "DI") (pinfunction "DI_DI") (pintype "input"))
      (node (ref "D355") (pin "DO") (pinfunction "DO_DO") (pintype "output"))
    )
    (net (code "360") (name "Net-(D355-PadDI)") (class "Default")
      (node (ref "D355") (pin "DI") (pinfunction "DI_DI") (pintype "input"))
      (node (ref "D356") (pin "DO") (pinfunction "DO_DO") (pintype "output"))
    )
    (net (code "361") (name "Net-(D356-PadDI)") (class "Default")
      (node (ref "D356") (pin "DI") (pinfunction "DI_DI") (pintype "input"))
      (node (ref "D357") (pin "DO") (pinfunction "DO_DO") (pintype "output"))
    )
    (net (code "362") (name "Net-(D357-PadDI)") (class "Default")
      (node (ref "D357") (pin "DI") (pinfunction "DI_DI") (pintype "input"))
      (node (ref "D358") (pin "DO") (pinfunction "DO_DO") (pintype "output"))
    )
    (net (code "363") (name "Net-(D358-PadDI)") (class "Default")
      (node (ref "D358") (pin "DI") (pinfunction "DI_DI") (pintype "input"))
      (node (ref "D359") (pin "DO") (pinfunction "DO_DO") (pintype "output"))
    )
    (net (code "364") (name "Net-(D359-PadDI)") (class "Default")
      (node (ref "D359") (pin "DI") (pinfunction "DI_DI") (pintype "input"))
      (node (ref "D360") (pin "DO") (pinfunction "DO_DO") (pintype "output"))
    )
    (net (code "365") (name "Net-(D361-PadDI)") (class "Default")
      (node (ref "D361") (pin "DI") (pinfunction "DI_DI") (pintype "input"))
      (node (ref "D362") (pin "DO") (pinfunction "DO_DO") (pintype "output"))
    )
    (net (code "366") (name "Net-(D362-PadDI)") (class "Default")
      (node (ref "D362") (pin "DI") (pinfunction "DI_DI") (pintype "input"))
      (node (ref "D363") (pin "DO") (pinfunction "DO_DO") (pintype "output"))
    )
    (net (code "367") (name "Net-(D363-PadDI)") (class "Default")
      (node (ref "D363") (pin "DI") (pinfunction "DI_DI") (pintype "input"))
      (node (ref "D364") (pin "DO") (pinfunction "DO_DO") (pintype "output"))
    )
    (net (code "368") (name "Net-(D364-PadDI)") (class "Default")
      (node (ref "D364") (pin "DI") (pinfunction "DI_DI") (pintype "input"))
      (node (ref "D365") (pin "DO") (pinfunction "DO_DO") (pintype "output"))
    )
    (net (code "369") (name "Net-(D365-PadDI)") (class "Default")
      (node (ref "D365") (pin "DI") (pinfunction "DI_DI") (pintype "input"))
      (node (ref "D366") (pin "DO") (pinfunction "DO_DO") (pintype "output"))
    )
    (net (code "370") (name "Net-(D366-PadDI)") (class "Default")
      (node (ref "D366") (pin "DI") (pinfunction "DI_DI") (pintype "input"))
      (node (ref "D367") (pin "DO") (pinfunction "DO_DO") (pintype "output"))
    )
    (net (code "371") (name "Net-(D367-PadDI)") (class "Default")
      (node (ref "D367") (pin "DI") (pinfunction "DI_DI") (pintype "input"))
      (node (ref "D368") (pin "DO") (pinfunction "DO_DO") (pintype "output"))
    )
    (net (code "372") (name "Net-(D368-PadDI)") (class "Default")
      (node (ref "D368") (pin "DI") (pinfunction "DI_DI") (pintype "input"))
      (node (ref "D369") (pin "DO") (pinfunction "DO_DO") (pintype "output"))
    )
    (net (code "373") (name "Net-(D369-PadDI)") (class "Default")
      (node (ref "D369") (pin "DI") (pinfunction "DI_DI") (pintype "input"))
      (node (ref "D370") (pin "DO") (pinfunction "DO_DO") (pintype "output"))
    )
    (net (code "374") (name "Net-(D370-PadDI)") (class "Default")
      (node (ref "D370") (pin "DI") (pinfunction "DI_DI") (pintype "input"))
      (node (ref "D371") (pin "DO") (pinfunction "DO_DO") (pintype "output"))
    )
    (net (code "375") (name "Net-(D371-PadDI)") (class "Default")
      (node (ref "D371") (pin "DI") (pinfunction "DI_DI") (pintype "input"))
      (node (ref "D372") (pin "DO") (pinfunction "DO_DO") (pintype "output"))
    )
    (net (code "376") (name "Net-(D372-PadDI)") (class "Default")
      (node (ref "D372") (pin "DI") (pinfunction "DI_DI") (pintype "input"))
      (node (ref "D373") (pin "DO") (pinfunction "DO_DO") (pintype "output"))
    )
    (net (code "377") (name "Net-(D373-PadDI)") (class "Default")
      (node (ref "D373") (pin "DI") (pinfunction "DI_DI") (pintype "input"))
      (node (ref "D374") (pin "DO") (pinfunction "DO_DO") (pintype "output"))
    )
    (net (code "378") (name "Net-(D374-PadDI)") (class "Default")
      (node (ref "D374") (pin "DI") (pinfunction "DI_DI") (pintype "input"))
      (node (ref "D375") (pin "DO") (pinfunction "DO_DO") (pintype "output"))
    )
    (net (code "379") (name "Net-(D376-PadDI)") (class "Default")
      (node (ref "D376") (pin "DI") (pinfunction "DI_DI") (pintype "input"))
      (node (ref "D377") (pin "DO") (pinfunction "DO_DO") (pintype "output"))
    )
    (net (code "380") (name "Net-(D377-PadDI)") (class "Default")
      (node (ref "D377") (pin "DI") (pinfunction "DI_DI") (pintype "input"))
      (node (ref "D378") (pin "DO") (pinfunction "DO_DO") (pintype "output"))
    )
    (net (code "381") (name "Net-(D378-PadDI)") (class "Default")
      (node (ref "D378") (pin "DI") (pinfunction "DI_DI") (pintype "input"))
      (node (ref "D379") (pin "DO") (pinfunction "DO_DO") (pintype "output"))
    )
    (net (code "382") (name "Net-(D379-PadDI)") (class "Default")
      (node (ref "D379") (pin "DI") (pinfunction "DI_DI") (pintype "input"))
      (node (ref "D380") (pin "DO") (pinfunction "DO_DO") (pintype "output"))
    )
    (net (code "383") (name "Net-(D380-PadDI)") (class "Default")
      (node (ref "D380") (pin "DI") (pinfunction "DI_DI") (pintype "input"))
      (node (ref "D381") (pin "DO") (pinfunction "DO_DO") (pintype "output"))
    )
    (net (code "384") (name "Net-(D381-PadDI)") (class "Default")
      (node (ref "D381") (pin "DI") (pinfunction "DI_DI") (pintype "input"))
      (node (ref "D382") (pin "DO") (pinfunction "DO_DO") (pintype "output"))
    )
    (net (code "385") (name "Net-(D382-PadDI)") (class "Default")
      (node (ref "D382") (pin "DI") (pinfunction "DI_DI") (pintype "input"))
      (node (ref "D383") (pin "DO") (pinfunction "DO_DO") (pintype "output"))
    )
    (net (code "386") (name "Net-(D383-PadDI)") (class "Default")
      (node (ref "D383") (pin "DI") (pinfunction "DI_DI") (pintype "input"))
      (node (ref "D384") (pin "DO") (pinfunction "DO_DO") (pintype "output"))
    )
    (net (code "387") (name "Net-(D384-PadDI)") (class "Default")
      (node (ref "D384") (pin "DI") (pinfunction "DI_DI") (pintype "input"))
      (node (ref "D385") (pin "DO") (pinfunction "DO_DO") (pintype "output"))
    )
    (net (code "388") (name "Net-(D385-PadDI)") (class "Default")
      (node (ref "D385") (pin "DI") (pinfunction "DI_DI") (pintype "input"))
      (node (ref "D386") (pin "DO") (pinfunction "DO_DO") (pintype "output"))
    )
    (net (code "389") (name "Net-(D386-PadDI)") (class "Default")
      (node (ref "D386") (pin "DI") (pinfunction "DI_DI") (pintype "input"))
      (node (ref "D387") (pin "DO") (pinfunction "DO_DO") (pintype "output"))
    )
    (net (code "390") (name "Net-(D387-PadDI)") (class "Default")
      (node (ref "D387") (pin "DI") (pinfunction "DI_DI") (pintype "input"))
      (node (ref "D388") (pin "DO") (pinfunction "DO_DO") (pintype "output"))
    )
    (net (code "391") (name "Net-(D388-PadDI)") (class "Default")
      (node (ref "D388") (pin "DI") (pinfunction "DI_DI") (pintype "input"))
      (node (ref "D389") (pin "DO") (pinfunction "DO_DO") (pintype "output"))
    )
    (net (code "392") (name "Net-(D389-PadDI)") (class "Default")
      (node (ref "D389") (pin "DI") (pinfunction "DI_DI") (pintype "input"))
      (node (ref "D390") (pin "DO") (pinfunction "DO_DO") (pintype "output"))
    )
    (net (code "393") (name "Net-(D391-PadDI)") (class "Default")
      (node (ref "D391") (pin "DI") (pinfunction "DI_DI") (pintype "input"))
      (node (ref "D392") (pin "DO") (pinfunction "DO_DO") (pintype "output"))
    )
    (net (code "394") (name "Net-(D392-PadDI)") (class "Default")
      (node (ref "D392") (pin "DI") (pinfunction "DI_DI") (pintype "input"))
      (node (ref "D393") (pin "DO") (pinfunction "DO_DO") (pintype "output"))
    )
    (net (code "395") (name "Net-(D393-PadDI)") (class "Default")
      (node (ref "D393") (pin "DI") (pinfunction "DI_DI") (pintype "input"))
      (node (ref "D394") (pin "DO") (pinfunction "DO_DO") (pintype "output"))
    )
    (net (code "396") (name "Net-(D394-PadDI)") (class "Default")
      (node (ref "D394") (pin "DI") (pinfunction "DI_DI") (pintype "input"))
      (node (ref "D395") (pin "DO") (pinfunction "DO_DO") (pintype "output"))
    )
    (net (code "397") (name "Net-(D395-PadDI)") (class "Default")
      (node (ref "D395") (pin "DI") (pinfunction "DI_DI") (pintype "input"))
      (node (ref "D396") (pin "DO") (pinfunction "DO_DO") (pintype "output"))
    )
    (net (code "398") (name "Net-(D396-PadDI)") (class "Default")
      (node (ref "D396") (pin "DI") (pinfunction "DI_DI") (pintype "input"))
      (node (ref "D397") (pin "DO") (pinfunction "DO_DO") (pintype "output"))
    )
    (net (code "399") (name "Net-(D397-PadDI)") (class "Default")
      (node (ref "D397") (pin "DI") (pinfunction "DI_DI") (pintype "input"))
      (node (ref "D398") (pin "DO") (pinfunction "DO_DO") (pintype "output"))
    )
    (net (code "400") (name "Net-(D398-PadDI)") (class "Default")
      (node (ref "D398") (pin "DI") (pinfunction "DI_DI") (pintype "input"))
      (node (ref "D399") (pin "DO") (pinfunction "DO_DO") (pintype "output"))
    )
    (net (code "401") (name "Net-(D399-PadDI)") (class "Default")
      (node (ref "D399") (pin "DI") (pinfunction "DI_DI") (pintype "input"))
      (node (ref "D400") (pin "DO") (pinfunction "DO_DO") (pintype "output"))
    )
    (net (code "402") (name "Net-(D400-PadDI)") (class "Default")
      (node (ref "D400") (pin "DI") (pinfunction "DI_DI") (pintype "input"))
      (node (ref "D401") (pin "DO") (pinfunction "DO_DO") (pintype "output"))
    )
    (net (code "403") (name "Net-(D401-PadDI)") (class "Default")
      (node (ref "D401") (pin "DI") (pinfunction "DI_DI") (pintype "input"))
      (node (ref "D402") (pin "DO") (pinfunction "DO_DO") (pintype "output"))
    )
    (net (code "404") (name "Net-(D402-PadDI)") (class "Default")
      (node (ref "D402") (pin "DI") (pinfunction "DI_DI") (pintype "input"))
      (node (ref "D403") (pin "DO") (pinfunction "DO_DO") (pintype "output"))
    )
    (net (code "405") (name "Net-(D403-PadDI)") (class "Default")
      (node (ref "D403") (pin "DI") (pinfunction "DI_DI") (pintype "input"))
      (node (ref "D404") (pin "DO") (pinfunction "DO_DO") (pintype "output"))
    )
    (net (code "406") (name "Net-(D404-PadDI)") (class "Default")
      (node (ref "D404") (pin "DI") (pinfunction "DI_DI") (pintype "input"))
      (node (ref "D405") (pin "DO") (pinfunction "DO_DO") (pintype "output"))
    )
    (net (code "407") (name "Net-(JP1-Pad4)") (class "Default")
      (node (ref "JP1") (pin "4") (pinfunction "4_4") (pintype "passive"))
      (node (ref "R1") (pin "1") (pinfunction "1_1") (pintype "passive"))
    )
    (net (code "408") (name "VCC") (class "Default")
      (node (ref "C1") (pin "+") (pinfunction "+_+") (pintype "passive"))
      (node (ref "C10") (pin "+") (pinfunction "+_+") (pintype "passive"))
      (node (ref "C100") (pin "1") (pinfunction "1_1") (pintype "passive"))
      (node (ref "C101") (pin "1") (pinfunction "1_1") (pintype "passive"))
      (node (ref "C102") (pin "1") (pinfunction "1_1") (pintype "passive"))
      (node (ref "C103") (pin "1") (pinfunction "1_1") (pintype "passive"))
      (node (ref "C104") (pin "1") (pinfunction "1_1") (pintype "passive"))
      (node (ref "C105") (pin "1") (pinfunction "1_1") (pintype "passive"))
      (node (ref "C106") (pin "1") (pinfunction "1_1") (pintype "passive"))
      (node (ref "C107") (pin "1") (pinfunction "1_1") (pintype "passive"))
      (node (ref "C108") (pin "1") (pinfunction "1_1") (pintype "passive"))
      (node (ref "C109") (pin "1") (pinfunction "1_1") (pintype "passive"))
      (node (ref "C11") (pin "+") (pinfunction "+_+") (pintype "passive"))
      (node (ref "C110") (pin "1") (pinfunction "1_1") (pintype "passive"))
      (node (ref "C111") (pin "1") (pinfunction "1_1") (pintype "passive"))
      (node (ref "C112") (pin "1") (pinfunction "1_1") (pintype "passive"))
      (node (ref "C113") (pin "1") (pinfunction "1_1") (pintype "passive"))
      (node (ref "C114") (pin "1") (pinfunction "1_1") (pintype "passive"))
      (node (ref "C115") (pin "1") (pinfunction "1_1") (pintype "passive"))
      (node (ref "C116") (pin "1") (pinfunction "1_1") (pintype "passive"))
      (node (ref "C117") (pin "1") (pinfunction "1_1") (pintype "passive"))
      (node (ref "C118") (pin "1") (pinfunction "1_1") (pintype "passive"))
      (node (ref "C119") (pin "1") (pinfunction "1_1") (pintype "passive"))
      (node (ref "C12") (pin "+") (pinfunction "+_+") (pintype "passive"))
      (node (ref "C120") (pin "1") (pinfunction "1_1") (pintype "passive"))
      (node (ref "C121") (pin "1") (pinfunction "1_1") (pintype "passive"))
      (node (ref "C122") (pin "1") (pinfunction "1_1") (pintype "passive"))
      (node (ref "C123") (pin "1") (pinfunction "1_1") (pintype "passive"))
      (node (ref "C124") (pin "1") (pinfunction "1_1") (pintype "passive"))
      (node (ref "C125") (pin "1") (pinfunction "1_1") (pintype "passive"))
      (node (ref "C126") (pin "1") (pinfunction "1_1") (pintype "passive"))
      (node (ref "C127") (pin "1") (pinfunction "1_1") (pintype "passive"))
      (node (ref "C128") (pin "1") (pinfunction "1_1") (pintype "passive"))
      (node (ref "C129") (pin "1") (pinfunction "1_1") (pintype "passive"))
      (node (ref "C13") (pin "+") (pinfunction "+_+") (pintype "passive"))
      (node (ref "C130") (pin "1") (pinfunction "1_1") (pintype "passive"))
      (node (ref "C131") (pin "1") (pinfunction "1_1") (pintype "passive"))
      (node (ref "C132") (pin "1") (pinfunction "1_1") (pintype "passive"))
      (node (ref "C133") (pin "1") (pinfunction "1_1") (pintype "passive"))
      (node (ref "C134") (pin "1") (pinfunction "1_1") (pintype "passive"))
      (node (ref "C135") (pin "1") (pinfunction "1_1") (pintype "passive"))
      (node (ref "C136") (pin "1") (pinfunction "1_1") (pintype "passive"))
      (node (ref "C137") (pin "1") (pinfunction "1_1") (pintype "passive"))
      (node (ref "C138") (pin "1") (pinfunction "1_1") (pintype "passive"))
      (node (ref "C139") (pin "1") (pinfunction "1_1") (pintype "passive"))
      (node (ref "C14") (pin "+") (pinfunction "+_+") (pintype "passive"))
      (node (ref "C140") (pin "1") (pinfunction "1_1") (pintype "passive"))
      (node (ref "C141") (pin "1") (pinfunction "1_1") (pintype "passive"))
      (node (ref "C142") (pin "1") (pinfunction "1_1") (pintype "passive"))
      (node (ref "C143") (pin "1") (pinfunction "1_1") (pintype "passive"))
      (node (ref "C144") (pin "1") (pinfunction "1_1") (pintype "passive"))
      (node (ref "C145") (pin "1") (pinfunction "1_1") (pintype "passive"))
      (node (ref "C146") (pin "1") (pinfunction "1_1") (pintype "passive"))
      (node (ref "C147") (pin "1") (pinfunction "1_1") (pintype "passive"))
      (node (ref "C148") (pin "1") (pinfunction "1_1") (pintype "passive"))
      (node (ref "C149") (pin "1") (pinfunction "1_1") (pintype "passive"))
      (node (ref "C15") (pin "+") (pinfunction "+_+") (pintype "passive"))
      (node (ref "C150") (pin "1") (pinfunction "1_1") (pintype "passive"))
      (node (ref "C151") (pin "1") (pinfunction "1_1") (pintype "passive"))
      (node (ref "C152") (pin "1") (pinfunction "1_1") (pintype "passive"))
      (node (ref "C153") (pin "1") (pinfunction "1_1") (pintype "passive"))
      (node (ref "C154") (pin "1") (pinfunction "1_1") (pintype "passive"))
      (node (ref "C155") (pin "1") (pinfunction "1_1") (pintype "passive"))
      (node (ref "C156") (pin "1") (pinfunction "1_1") (pintype "passive"))
      (node (ref "C157") (pin "1") (pinfunction "1_1") (pintype "passive"))
      (node (ref "C158") (pin "1") (pinfunction "1_1") (pintype "passive"))
      (node (ref "C159") (pin "1") (pinfunction "1_1") (pintype "passive"))
      (node (ref "C16") (pin "+") (pinfunction "+_+") (pintype "passive"))
      (node (ref "C160") (pin "1") (pinfunction "1_1") (pintype "passive"))
      (node (ref "C161") (pin "1") (pinfunction "1_1") (pintype "passive"))
      (node (ref "C162") (pin "1") (pinfunction "1_1") (pintype "passive"))
      (node (ref "C163") (pin "1") (pinfunction "1_1") (pintype "passive"))
      (node (ref "C164") (pin "1") (pinfunction "1_1") (pintype "passive"))
      (node (ref "C165") (pin "1") (pinfunction "1_1") (pintype "passive"))
      (node (ref "C166") (pin "1") (pinfunction "1_1") (pintype "passive"))
      (node (ref "C167") (pin "1") (pinfunction "1_1") (pintype "passive"))
      (node (ref "C168") (pin "1") (pinfunction "1_1") (pintype "passive"))
      (node (ref "C169") (pin "1") (pinfunction "1_1") (pintype "passive"))
      (node (ref "C17") (pin "+") (pinfunction "+_+") (pintype "passive"))
      (node (ref "C18") (pin "+") (pinfunction "+_+") (pintype "passive"))
      (node (ref "C19") (pin "+") (pinfunction "+_+") (pintype "passive"))
      (node (ref "C2") (pin "+") (pinfunction "+_+") (pintype "passive"))
      (node (ref "C20") (pin "+") (pinfunction "+_+") (pintype "passive"))
      (node (ref "C21") (pin "+") (pinfunction "+_+") (pintype "passive"))
      (node (ref "C22") (pin "+") (pinfunction "+_+") (pintype "passive"))
      (node (ref "C23") (pin "+") (pinfunction "+_+") (pintype "passive"))
      (node (ref "C24") (pin "+") (pinfunction "+_+") (pintype "passive"))
      (node (ref "C25") (pin "1") (pinfunction "1_1") (pintype "passive"))
      (node (ref "C26") (pin "1") (pinfunction "1_1") (pintype "passive"))
      (node (ref "C27") (pin "1") (pinfunction "1_1") (pintype "passive"))
      (node (ref "C28") (pin "1") (pinfunction "1_1") (pintype "passive"))
      (node (ref "C29") (pin "1") (pinfunction "1_1") (pintype "passive"))
      (node (ref "C3") (pin "+") (pinfunction "+_+") (pintype "passive"))
      (node (ref "C30") (pin "1") (pinfunction "1_1") (pintype "passive"))
      (node (ref "C31") (pin "1") (pinfunction "1_1") (pintype "passive"))
      (node (ref "C32") (pin "1") (pinfunction "1_1") (pintype "passive"))
      (node (ref "C33") (pin "1") (pinfunction "1_1") (pintype "passive"))
      (node (ref "C34") (pin "1") (pinfunction "1_1") (pintype "passive"))
      (node (ref "C35") (pin "1") (pinfunction "1_1") (pintype "passive"))
      (node (ref "C36") (pin "1") (pinfunction "1_1") (pintype "passive"))
      (node (ref "C37") (pin "1") (pinfunction "1_1") (pintype "passive"))
      (node (ref "C38") (pin "1") (pinfunction "1_1") (pintype "passive"))
      (node (ref "C39") (pin "1") (pinfunction "1_1") (pintype "passive"))
      (node (ref "C4") (pin "+") (pinfunction "+_+") (pintype "passive"))
      (node (ref "C40") (pin "1") (pinfunction "1_1") (pintype "passive"))
      (node (ref "C41") (pin "1") (pinfunction "1_1") (pintype "passive"))
      (node (ref "C42") (pin "1") (pinfunction "1_1") (pintype "passive"))
      (node (ref "C43") (pin "1") (pinfunction "1_1") (pintype "passive"))
      (node (ref "C44") (pin "1") (pinfunction "1_1") (pintype "passive"))
      (node (ref "C45") (pin "1") (pinfunction "1_1") (pintype "passive"))
      (node (ref "C46") (pin "1") (pinfunction "1_1") (pintype "passive"))
      (node (ref "C47") (pin "1") (pinfunction "1_1") (pintype "passive"))
      (node (ref "C48") (pin "1") (pinfunction "1_1") (pintype "passive"))
      (node (ref "C49") (pin "1") (pinfunction "1_1") (pintype "passive"))
      (node (ref "C5") (pin "+") (pinfunction "+_+") (pintype "passive"))
      (node (ref "C50") (pin "1") (pinfunction "1_1") (pintype "passive"))
      (node (ref "C51") (pin "1") (pinfunction "1_1") (pintype "passive"))
      (node (ref "C52") (pin "1") (pinfunction "1_1") (pintype "passive"))
      (node (ref "C53") (pin "1") (pinfunction "1_1") (pintype "passive"))
      (node (ref "C54") (pin "1") (pinfunction "1_1") (pintype "passive"))
      (node (ref "C55") (pin "1") (pinfunction "1_1") (pintype "passive"))
      (node (ref "C56") (pin "1") (pinfunction "1_1") (pintype "passive"))
      (node (ref "C57") (pin "1") (pinfunction "1_1") (pintype "passive"))
      (node (ref "C58") (pin "1") (pinfunction "1_1") (pintype "passive"))
      (node (ref "C59") (pin "1") (pinfunction "1_1") (pintype "passive"))
      (node (ref "C6") (pin "+") (pinfunction "+_+") (pintype "passive"))
      (node (ref "C60") (pin "1") (pinfunction "1_1") (pintype "passive"))
      (node (ref "C61") (pin "1") (pinfunction "1_1") (pintype "passive"))
      (node (ref "C62") (pin "1") (pinfunction "1_1") (pintype "passive"))
      (node (ref "C63") (pin "1") (pinfunction "1_1") (pintype "passive"))
      (node (ref "C64") (pin "1") (pinfunction "1_1") (pintype "passive"))
      (node (ref "C65") (pin "1") (pinfunction "1_1") (pintype "passive"))
      (node (ref "C66") (pin "1") (pinfunction "1_1") (pintype "passive"))
      (node (ref "C67") (pin "1") (pinfunction "1_1") (pintype "passive"))
      (node (ref "C68") (pin "1") (pinfunction "1_1") (pintype "passive"))
      (node (ref "C69") (pin "1") (pinfunction "1_1") (pintype "passive"))
      (node (ref "C7") (pin "+") (pinfunction "+_+") (pintype "passive"))
      (node (ref "C70") (pin "1") (pinfunction "1_1") (pintype "passive"))
      (node (ref "C71") (pin "1") (pinfunction "1_1") (pintype "passive"))
      (node (ref "C72") (pin "1") (pinfunction "1_1") (pintype "passive"))
      (node (ref "C73") (pin "1") (pinfunction "1_1") (pintype "passive"))
      (node (ref "C74") (pin "1") (pinfunction "1_1") (pintype "passive"))
      (node (ref "C75") (pin "1") (pinfunction "1_1") (pintype "passive"))
      (node (ref "C76") (pin "1") (pinfunction "1_1") (pintype "passive"))
      (node (ref "C77") (pin "1") (pinfunction "1_1") (pintype "passive"))
      (node (ref "C78") (pin "1") (pinfunction "1_1") (pintype "passive"))
      (node (ref "C79") (pin "1") (pinfunction "1_1") (pintype "passive"))
      (node (ref "C8") (pin "+") (pinfunction "+_+") (pintype "passive"))
      (node (ref "C80") (pin "1") (pinfunction "1_1") (pintype "passive"))
      (node (ref "C81") (pin "1") (pinfunction "1_1") (pintype "passive"))
      (node (ref "C82") (pin "1") (pinfunction "1_1") (pintype "passive"))
      (node (ref "C83") (pin "1") (pinfunction "1_1") (pintype "passive"))
      (node (ref "C84") (pin "1") (pinfunction "1_1") (pintype "passive"))
      (node (ref "C85") (pin "1") (pinfunction "1_1") (pintype "passive"))
      (node (ref "C86") (pin "1") (pinfunction "1_1") (pintype "passive"))
      (node (ref "C87") (pin "1") (pinfunction "1_1") (pintype "passive"))
      (node (ref "C88") (pin "1") (pinfunction "1_1") (pintype "passive"))
      (node (ref "C89") (pin "1") (pinfunction "1_1") (pintype "passive"))
      (node (ref "C9") (pin "+") (pinfunction "+_+") (pintype "passive"))
      (node (ref "C90") (pin "1") (pinfunction "1_1") (pintype "passive"))
      (node (ref "C91") (pin "1") (pinfunction "1_1") (pintype "passive"))
      (node (ref "C92") (pin "1") (pinfunction "1_1") (pintype "passive"))
      (node (ref "C93") (pin "1") (pinfunction "1_1") (pintype "passive"))
      (node (ref "C94") (pin "1") (pinfunction "1_1") (pintype "passive"))
      (node (ref "C95") (pin "1") (pinfunction "1_1") (pintype "passive"))
      (node (ref "C96") (pin "1") (pinfunction "1_1") (pintype "passive"))
      (node (ref "C97") (pin "1") (pinfunction "1_1") (pintype "passive"))
      (node (ref "C98") (pin "1") (pinfunction "1_1") (pintype "passive"))
      (node (ref "C99") (pin "1") (pinfunction "1_1") (pintype "passive"))
      (node (ref "D1") (pin "VCC") (pinfunction "VCC_VCC") (pintype "power_in"))
      (node (ref "D10") (pin "VCC") (pinfunction "VCC_VCC") (pintype "power_in"))
      (node (ref "D100") (pin "VCC") (pinfunction "VCC_VCC") (pintype "power_in"))
      (node (ref "D101") (pin "VCC") (pinfunction "VCC_VCC") (pintype "power_in"))
      (node (ref "D102") (pin "VCC") (pinfunction "VCC_VCC") (pintype "power_in"))
      (node (ref "D103") (pin "VCC") (pinfunction "VCC_VCC") (pintype "power_in"))
      (node (ref "D104") (pin "VCC") (pinfunction "VCC_VCC") (pintype "power_in"))
      (node (ref "D105") (pin "VCC") (pinfunction "VCC_VCC") (pintype "power_in"))
      (node (ref "D106") (pin "VCC") (pinfunction "VCC_VCC") (pintype "power_in"))
      (node (ref "D107") (pin "VCC") (pinfunction "VCC_VCC") (pintype "power_in"))
      (node (ref "D108") (pin "VCC") (pinfunction "VCC_VCC") (pintype "power_in"))
      (node (ref "D109") (pin "VCC") (pinfunction "VCC_VCC") (pintype "power_in"))
      (node (ref "D11") (pin "VCC") (pinfunction "VCC_VCC") (pintype "power_in"))
      (node (ref "D110") (pin "VCC") (pinfunction "VCC_VCC") (pintype "power_in"))
      (node (ref "D111") (pin "VCC") (pinfunction "VCC_VCC") (pintype "power_in"))
      (node (ref "D112") (pin "VCC") (pinfunction "VCC_VCC") (pintype "power_in"))
      (node (ref "D113") (pin "VCC") (pinfunction "VCC_VCC") (pintype "power_in"))
      (node (ref "D114") (pin "VCC") (pinfunction "VCC_VCC") (pintype "power_in"))
      (node (ref "D115") (pin "VCC") (pinfunction "VCC_VCC") (pintype "power_in"))
      (node (ref "D116") (pin "VCC") (pinfunction "VCC_VCC") (pintype "power_in"))
      (node (ref "D117") (pin "VCC") (pinfunction "VCC_VCC") (pintype "power_in"))
      (node (ref "D118") (pin "VCC") (pinfunction "VCC_VCC") (pintype "power_in"))
      (node (ref "D119") (pin "VCC") (pinfunction "VCC_VCC") (pintype "power_in"))
      (node (ref "D12") (pin "VCC") (pinfunction "VCC_VCC") (pintype "power_in"))
      (node (ref "D120") (pin "VCC") (pinfunction "VCC_VCC") (pintype "power_in"))
      (node (ref "D121") (pin "VCC") (pinfunction "VCC_VCC") (pintype "power_in"))
      (node (ref "D122") (pin "VCC") (pinfunction "VCC_VCC") (pintype "power_in"))
      (node (ref "D123") (pin "VCC") (pinfunction "VCC_VCC") (pintype "power_in"))
      (node (ref "D124") (pin "VCC") (pinfunction "VCC_VCC") (pintype "power_in"))
      (node (ref "D125") (pin "VCC") (pinfunction "VCC_VCC") (pintype "power_in"))
      (node (ref "D126") (pin "VCC") (pinfunction "VCC_VCC") (pintype "power_in"))
      (node (ref "D127") (pin "VCC") (pinfunction "VCC_VCC") (pintype "power_in"))
      (node (ref "D128") (pin "VCC") (pinfunction "VCC_VCC") (pintype "power_in"))
      (node (ref "D129") (pin "VCC") (pinfunction "VCC_VCC") (pintype "power_in"))
      (node (ref "D13") (pin "VCC") (pinfunction "VCC_VCC") (pintype "power_in"))
      (node (ref "D130") (pin "VCC") (pinfunction "VCC_VCC") (pintype "power_in"))
      (node (ref "D131") (pin "VCC") (pinfunction "VCC_VCC") (pintype "power_in"))
      (node (ref "D132") (pin "VCC") (pinfunction "VCC_VCC") (pintype "power_in"))
      (node (ref "D133") (pin "VCC") (pinfunction "VCC_VCC") (pintype "power_in"))
      (node (ref "D134") (pin "VCC") (pinfunction "VCC_VCC") (pintype "power_in"))
      (node (ref "D135") (pin "VCC") (pinfunction "VCC_VCC") (pintype "power_in"))
      (node (ref "D136") (pin "VCC") (pinfunction "VCC_VCC") (pintype "power_in"))
      (node (ref "D137") (pin "VCC") (pinfunction "VCC_VCC") (pintype "power_in"))
      (node (ref "D138") (pin "VCC") (pinfunction "VCC_VCC") (pintype "power_in"))
      (node (ref "D139") (pin "VCC") (pinfunction "VCC_VCC") (pintype "power_in"))
      (node (ref "D14") (pin "VCC") (pinfunction "VCC_VCC") (pintype "power_in"))
      (node (ref "D140") (pin "VCC") (pinfunction "VCC_VCC") (pintype "power_in"))
      (node (ref "D141") (pin "VCC") (pinfunction "VCC_VCC") (pintype "power_in"))
      (node (ref "D142") (pin "VCC") (pinfunction "VCC_VCC") (pintype "power_in"))
      (node (ref "D143") (pin "VCC") (pinfunction "VCC_VCC") (pintype "power_in"))
      (node (ref "D144") (pin "VCC") (pinfunction "VCC_VCC") (pintype "power_in"))
      (node (ref "D145") (pin "VCC") (pinfunction "VCC_VCC") (pintype "power_in"))
      (node (ref "D146") (pin "VCC") (pinfunction "VCC_VCC") (pintype "power_in"))
      (node (ref "D147") (pin "VCC") (pinfunction "VCC_VCC") (pintype "power_in"))
      (node (ref "D148") (pin "VCC") (pinfunction "VCC_VCC") (pintype "power_in"))
      (node (ref "D149") (pin "VCC") (pinfunction "VCC_VCC") (pintype "power_in"))
      (node (ref "D15") (pin "VCC") (pinfunction "VCC_VCC") (pintype "power_in"))
      (node (ref "D150") (pin "VCC") (pinfunction "VCC_VCC") (pintype "power_in"))
      (node (ref "D151") (pin "VCC") (pinfunction "VCC_VCC") (pintype "power_in"))
      (node (ref "D152") (pin "VCC") (pinfunction "VCC_VCC") (pintype "power_in"))
      (node (ref "D153") (pin "VCC") (pinfunction "VCC_VCC") (pintype "power_in"))
      (node (ref "D154") (pin "VCC") (pinfunction "VCC_VCC") (pintype "power_in"))
      (node (ref "D155") (pin "VCC") (pinfunction "VCC_VCC") (pintype "power_in"))
      (node (ref "D156") (pin "VCC") (pinfunction "VCC_VCC") (pintype "power_in"))
      (node (ref "D157") (pin "VCC") (pinfunction "VCC_VCC") (pintype "power_in"))
      (node (ref "D158") (pin "VCC") (pinfunction "VCC_VCC") (pintype "power_in"))
      (node (ref "D159") (pin "VCC") (pinfunction "VCC_VCC") (pintype "power_in"))
      (node (ref "D16") (pin "VCC") (pinfunction "VCC_VCC") (pintype "power_in"))
      (node (ref "D160") (pin "VCC") (pinfunction "VCC_VCC") (pintype "power_in"))
      (node (ref "D161") (pin "VCC") (pinfunction "VCC_VCC") (pintype "power_in"))
      (node (ref "D162") (pin "VCC") (pinfunction "VCC_VCC") (pintype "power_in"))
      (node (ref "D163") (pin "VCC") (pinfunction "VCC_VCC") (pintype "power_in"))
      (node (ref "D164") (pin "VCC") (pinfunction "VCC_VCC") (pintype "power_in"))
      (node (ref "D165") (pin "VCC") (pinfunction "VCC_VCC") (pintype "power_in"))
      (node (ref "D166") (pin "VCC") (pinfunction "VCC_VCC") (pintype "power_in"))
      (node (ref "D167") (pin "VCC") (pinfunction "VCC_VCC") (pintype "power_in"))
      (node (ref "D168") (pin "VCC") (pinfunction "VCC_VCC") (pintype "power_in"))
      (node (ref "D169") (pin "VCC") (pinfunction "VCC_VCC") (pintype "power_in"))
      (node (ref "D17") (pin "VCC") (pinfunction "VCC_VCC") (pintype "power_in"))
      (node (ref "D170") (pin "VCC") (pinfunction "VCC_VCC") (pintype "power_in"))
      (node (ref "D171") (pin "VCC") (pinfunction "VCC_VCC") (pintype "power_in"))
      (node (ref "D172") (pin "VCC") (pinfunction "VCC_VCC") (pintype "power_in"))
      (node (ref "D173") (pin "VCC") (pinfunction "VCC_VCC") (pintype "power_in"))
      (node (ref "D174") (pin "VCC") (pinfunction "VCC_VCC") (pintype "power_in"))
      (node (ref "D175") (pin "VCC") (pinfunction "VCC_VCC") (pintype "power_in"))
      (node (ref "D176") (pin "VCC") (pinfunction "VCC_VCC") (pintype "power_in"))
      (node (ref "D177") (pin "VCC") (pinfunction "VCC_VCC") (pintype "power_in"))
      (node (ref "D178") (pin "VCC") (pinfunction "VCC_VCC") (pintype "power_in"))
      (node (ref "D179") (pin "VCC") (pinfunction "VCC_VCC") (pintype "power_in"))
      (node (ref "D18") (pin "VCC") (pinfunction "VCC_VCC") (pintype "power_in"))
      (node (ref "D180") (pin "VCC") (pinfunction "VCC_VCC") (pintype "power_in"))
      (node (ref "D181") (pin "VCC") (pinfunction "VCC_VCC") (pintype "power_in"))
      (node (ref "D182") (pin "VCC") (pinfunction "VCC_VCC") (pintype "power_in"))
      (node (ref "D183") (pin "VCC") (pinfunction "VCC_VCC") (pintype "power_in"))
      (node (ref "D184") (pin "VCC") (pinfunction "VCC_VCC") (pintype "power_in"))
      (node (ref "D185") (pin "VCC") (pinfunction "VCC_VCC") (pintype "power_in"))
      (node (ref "D186") (pin "VCC") (pinfunction "VCC_VCC") (pintype "power_in"))
      (node (ref "D187") (pin "VCC") (pinfunction "VCC_VCC") (pintype "power_in"))
      (node (ref "D188") (pin "VCC") (pinfunction "VCC_VCC") (pintype "power_in"))
      (node (ref "D189") (pin "VCC") (pinfunction "VCC_VCC") (pintype "power_in"))
      (node (ref "D19") (pin "VCC") (pinfunction "VCC_VCC") (pintype "power_in"))
      (node (ref "D190") (pin "VCC") (pinfunction "VCC_VCC") (pintype "power_in"))
      (node (ref "D191") (pin "VCC") (pinfunction "VCC_VCC") (pintype "power_in"))
      (node (ref "D192") (pin "VCC") (pinfunction "VCC_VCC") (pintype "power_in"))
      (node (ref "D193") (pin "VCC") (pinfunction "VCC_VCC") (pintype "power_in"))
      (node (ref "D194") (pin "VCC") (pinfunction "VCC_VCC") (pintype "power_in"))
      (node (ref "D195") (pin "VCC") (pinfunction "VCC_VCC") (pintype "power_in"))
      (node (ref "D196") (pin "VCC") (pinfunction "VCC_VCC") (pintype "power_in"))
      (node (ref "D197") (pin "VCC") (pinfunction "VCC_VCC") (pintype "power_in"))
      (node (ref "D198") (pin "VCC") (pinfunction "VCC_VCC") (pintype "power_in"))
      (node (ref "D199") (pin "VCC") (pinfunction "VCC_VCC") (pintype "power_in"))
      (node (ref "D2") (pin "VCC") (pinfunction "VCC_VCC") (pintype "power_in"))
      (node (ref "D20") (pin "VCC") (pinfunction "VCC_VCC") (pintype "power_in"))
      (node (ref "D200") (pin "VCC") (pinfunction "VCC_VCC") (pintype "power_in"))
      (node (ref "D201") (pin "VCC") (pinfunction "VCC_VCC") (pintype "power_in"))
      (node (ref "D202") (pin "VCC") (pinfunction "VCC_VCC") (pintype "power_in"))
      (node (ref "D203") (pin "VCC") (pinfunction "VCC_VCC") (pintype "power_in"))
      (node (ref "D204") (pin "VCC") (pinfunction "VCC_VCC") (pintype "power_in"))
      (node (ref "D205") (pin "VCC") (pinfunction "VCC_VCC") (pintype "power_in"))
      (node (ref "D206") (pin "VCC") (pinfunction "VCC_VCC") (pintype "power_in"))
      (node (ref "D207") (pin "VCC") (pinfunction "VCC_VCC") (pintype "power_in"))
      (node (ref "D208") (pin "VCC") (pinfunction "VCC_VCC") (pintype "power_in"))
      (node (ref "D209") (pin "VCC") (pinfunction "VCC_VCC") (pintype "power_in"))
      (node (ref "D21") (pin "VCC") (pinfunction "VCC_VCC") (pintype "power_in"))
      (node (ref "D210") (pin "VCC") (pinfunction "VCC_VCC") (pintype "power_in"))
      (node (ref "D211") (pin "VCC") (pinfunction "VCC_VCC") (pintype "power_in"))
      (node (ref "D212") (pin "VCC") (pinfunction "VCC_VCC") (pintype "power_in"))
      (node (ref "D213") (pin "VCC") (pinfunction "VCC_VCC") (pintype "power_in"))
      (node (ref "D214") (pin "VCC") (pinfunction "VCC_VCC") (pintype "power_in"))
      (node (ref "D215") (pin "VCC") (pinfunction "VCC_VCC") (pintype "power_in"))
      (node (ref "D216") (pin "VCC") (pinfunction "VCC_VCC") (pintype "power_in"))
      (node (ref "D217") (pin "VCC") (pinfunction "VCC_VCC") (pintype "power_in"))
      (node (ref "D218") (pin "VCC") (pinfunction "VCC_VCC") (pintype "power_in"))
      (node (ref "D219") (pin "VCC") (pinfunction "VCC_VCC") (pintype "power_in"))
      (node (ref "D22") (pin "VCC") (pinfunction "VCC_VCC") (pintype "power_in"))
      (node (ref "D220") (pin "VCC") (pinfunction "VCC_VCC") (pintype "power_in"))
      (node (ref "D221") (pin "VCC") (pinfunction "VCC_VCC") (pintype "power_in"))
      (node (ref "D222") (pin "VCC") (pinfunction "VCC_VCC") (pintype "power_in"))
      (node (ref "D223") (pin "VCC") (pinfunction "VCC_VCC") (pintype "power_in"))
      (node (ref "D224") (pin "VCC") (pinfunction "VCC_VCC") (pintype "power_in"))
      (node (ref "D225") (pin "VCC") (pinfunction "VCC_VCC") (pintype "power_in"))
      (node (ref "D226") (pin "VCC") (pinfunction "VCC_VCC") (pintype "power_in"))
      (node (ref "D227") (pin "VCC") (pinfunction "VCC_VCC") (pintype "power_in"))
      (node (ref "D228") (pin "VCC") (pinfunction "VCC_VCC") (pintype "power_in"))
      (node (ref "D229") (pin "VCC") (pinfunction "VCC_VCC") (pintype "power_in"))
      (node (ref "D23") (pin "VCC") (pinfunction "VCC_VCC") (pintype "power_in"))
      (node (ref "D230") (pin "VCC") (pinfunction "VCC_VCC") (pintype "power_in"))
      (node (ref "D231") (pin "VCC") (pinfunction "VCC_VCC") (pintype "power_in"))
      (node (ref "D232") (pin "VCC") (pinfunction "VCC_VCC") (pintype "power_in"))
      (node (ref "D233") (pin "VCC") (pinfunction "VCC_VCC") (pintype "power_in"))
      (node (ref "D234") (pin "VCC") (pinfunction "VCC_VCC") (pintype "power_in"))
      (node (ref "D235") (pin "VCC") (pinfunction "VCC_VCC") (pintype "power_in"))
      (node (ref "D236") (pin "VCC") (pinfunction "VCC_VCC") (pintype "power_in"))
      (node (ref "D237") (pin "VCC") (pinfunction "VCC_VCC") (pintype "power_in"))
      (node (ref "D238") (pin "VCC") (pinfunction "VCC_VCC") (pintype "power_in"))
      (node (ref "D239") (pin "VCC") (pinfunction "VCC_VCC") (pintype "power_in"))
      (node (ref "D24") (pin "VCC") (pinfunction "VCC_VCC") (pintype "power_in"))
      (node (ref "D240") (pin "VCC") (pinfunction "VCC_VCC") (pintype "power_in"))
      (node (ref "D241") (pin "VCC") (pinfunction "VCC_VCC") (pintype "power_in"))
      (node (ref "D242") (pin "VCC") (pinfunction "VCC_VCC") (pintype "power_in"))
      (node (ref "D243") (pin "VCC") (pinfunction "VCC_VCC") (pintype "power_in"))
      (node (ref "D244") (pin "VCC") (pinfunction "VCC_VCC") (pintype "power_in"))
      (node (ref "D245") (pin "VCC") (pinfunction "VCC_VCC") (pintype "power_in"))
      (node (ref "D246") (pin "VCC") (pinfunction "VCC_VCC") (pintype "power_in"))
      (node (ref "D247") (pin "VCC") (pinfunction "VCC_VCC") (pintype "power_in"))
      (node (ref "D248") (pin "VCC") (pinfunction "VCC_VCC") (pintype "power_in"))
      (node (ref "D249") (pin "VCC") (pinfunction "VCC_VCC") (pintype "power_in"))
      (node (ref "D25") (pin "VCC") (pinfunction "VCC_VCC") (pintype "power_in"))
      (node (ref "D250") (pin "VCC") (pinfunction "VCC_VCC") (pintype "power_in"))
      (node (ref "D251") (pin "VCC") (pinfunction "VCC_VCC") (pintype "power_in"))
      (node (ref "D252") (pin "VCC") (pinfunction "VCC_VCC") (pintype "power_in"))
      (node (ref "D253") (pin "VCC") (pinfunction "VCC_VCC") (pintype "power_in"))
      (node (ref "D254") (pin "VCC") (pinfunction "VCC_VCC") (pintype "power_in"))
      (node (ref "D255") (pin "VCC") (pinfunction "VCC_VCC") (pintype "power_in"))
      (node (ref "D256") (pin "VCC") (pinfunction "VCC_VCC") (pintype "power_in"))
      (node (ref "D257") (pin "VCC") (pinfunction "VCC_VCC") (pintype "power_in"))
      (node (ref "D258") (pin "VCC") (pinfunction "VCC_VCC") (pintype "power_in"))
      (node (ref "D259") (pin "VCC") (pinfunction "VCC_VCC") (pintype "power_in"))
      (node (ref "D26") (pin "VCC") (pinfunction "VCC_VCC") (pintype "power_in"))
      (node (ref "D260") (pin "VCC") (pinfunction "VCC_VCC") (pintype "power_in"))
      (node (ref "D261") (pin "VCC") (pinfunction "VCC_VCC") (pintype "power_in"))
      (node (ref "D262") (pin "VCC") (pinfunction "VCC_VCC") (pintype "power_in"))
      (node (ref "D263") (pin "VCC") (pinfunction "VCC_VCC") (pintype "power_in"))
      (node (ref "D264") (pin "VCC") (pinfunction "VCC_VCC") (pintype "power_in"))
      (node (ref "D265") (pin "VCC") (pinfunction "VCC_VCC") (pintype "power_in"))
      (node (ref "D266") (pin "VCC") (pinfunction "VCC_VCC") (pintype "power_in"))
      (node (ref "D267") (pin "VCC") (pinfunction "VCC_VCC") (pintype "power_in"))
      (node (ref "D268") (pin "VCC") (pinfunction "VCC_VCC") (pintype "power_in"))
      (node (ref "D269") (pin "VCC") (pinfunction "VCC_VCC") (pintype "power_in"))
      (node (ref "D27") (pin "VCC") (pinfunction "VCC_VCC") (pintype "power_in"))
      (node (ref "D270") (pin "VCC") (pinfunction "VCC_VCC") (pintype "power_in"))
      (node (ref "D271") (pin "VCC") (pinfunction "VCC_VCC") (pintype "power_in"))
      (node (ref "D272") (pin "VCC") (pinfunction "VCC_VCC") (pintype "power_in"))
      (node (ref "D273") (pin "VCC") (pinfunction "VCC_VCC") (pintype "power_in"))
      (node (ref "D274") (pin "VCC") (pinfunction "VCC_VCC") (pintype "power_in"))
      (node (ref "D275") (pin "VCC") (pinfunction "VCC_VCC") (pintype "power_in"))
      (node (ref "D276") (pin "VCC") (pinfunction "VCC_VCC") (pintype "power_in"))
      (node (ref "D277") (pin "VCC") (pinfunction "VCC_VCC") (pintype "power_in"))
      (node (ref "D278") (pin "VCC") (pinfunction "VCC_VCC") (pintype "power_in"))
      (node (ref "D279") (pin "VCC") (pinfunction "VCC_VCC") (pintype "power_in"))
      (node (ref "D28") (pin "VCC") (pinfunction "VCC_VCC") (pintype "power_in"))
      (node (ref "D280") (pin "VCC") (pinfunction "VCC_VCC") (pintype "power_in"))
      (node (ref "D281") (pin "VCC") (pinfunction "VCC_VCC") (pintype "power_in"))
      (node (ref "D282") (pin "VCC") (pinfunction "VCC_VCC") (pintype "power_in"))
      (node (ref "D283") (pin "VCC") (pinfunction "VCC_VCC") (pintype "power_in"))
      (node (ref "D284") (pin "VCC") (pinfunction "VCC_VCC") (pintype "power_in"))
      (node (ref "D285") (pin "VCC") (pinfunction "VCC_VCC") (pintype "power_in"))
      (node (ref "D286") (pin "VCC") (pinfunction "VCC_VCC") (pintype "power_in"))
      (node (ref "D287") (pin "VCC") (pinfunction "VCC_VCC") (pintype "power_in"))
      (node (ref "D288") (pin "VCC") (pinfunction "VCC_VCC") (pintype "power_in"))
      (node (ref "D289") (pin "VCC") (pinfunction "VCC_VCC") (pintype "power_in"))
      (node (ref "D29") (pin "VCC") (pinfunction "VCC_VCC") (pintype "power_in"))
      (node (ref "D290") (pin "VCC") (pinfunction "VCC_VCC") (pintype "power_in"))
      (node (ref "D291") (pin "VCC") (pinfunction "VCC_VCC") (pintype "power_in"))
      (node (ref "D292") (pin "VCC") (pinfunction "VCC_VCC") (pintype "power_in"))
      (node (ref "D293") (pin "VCC") (pinfunction "VCC_VCC") (pintype "power_in"))
      (node (ref "D294") (pin "VCC") (pinfunction "VCC_VCC") (pintype "power_in"))
      (node (ref "D295") (pin "VCC") (pinfunction "VCC_VCC") (pintype "power_in"))
      (node (ref "D296") (pin "VCC") (pinfunction "VCC_VCC") (pintype "power_in"))
      (node (ref "D297") (pin "VCC") (pinfunction "VCC_VCC") (pintype "power_in"))
      (node (ref "D298") (pin "VCC") (pinfunction "VCC_VCC") (pintype "power_in"))
      (node (ref "D299") (pin "VCC") (pinfunction "VCC_VCC") (pintype "power_in"))
      (node (ref "D3") (pin "VCC") (pinfunction "VCC_VCC") (pintype "power_in"))
      (node (ref "D30") (pin "VCC") (pinfunction "VCC_VCC") (pintype "power_in"))
      (node (ref "D300") (pin "VCC") (pinfunction "VCC_VCC") (pintype "power_in"))
      (node (ref "D301") (pin "VCC") (pinfunction "VCC_VCC") (pintype "power_in"))
      (node (ref "D302") (pin "VCC") (pinfunction "VCC_VCC") (pintype "power_in"))
      (node (ref "D303") (pin "VCC") (pinfunction "VCC_VCC") (pintype "power_in"))
      (node (ref "D304") (pin "VCC") (pinfunction "VCC_VCC") (pintype "power_in"))
      (node (ref "D305") (pin "VCC") (pinfunction "VCC_VCC") (pintype "power_in"))
      (node (ref "D306") (pin "VCC") (pinfunction "VCC_VCC") (pintype "power_in"))
      (node (ref "D307") (pin "VCC") (pinfunction "VCC_VCC") (pintype "power_in"))
      (node (ref "D308") (pin "VCC") (pinfunction "VCC_VCC") (pintype "power_in"))
      (node (ref "D309") (pin "VCC") (pinfunction "VCC_VCC") (pintype "power_in"))
      (node (ref "D31") (pin "VCC") (pinfunction "VCC_VCC") (pintype "power_in"))
      (node (ref "D310") (pin "VCC") (pinfunction "VCC_VCC") (pintype "power_in"))
      (node (ref "D311") (pin "VCC") (pinfunction "VCC_VCC") (pintype "power_in"))
      (node (ref "D312") (pin "VCC") (pinfunction "VCC_VCC") (pintype "power_in"))
      (node (ref "D313") (pin "VCC") (pinfunction "VCC_VCC") (pintype "power_in"))
      (node (ref "D314") (pin "VCC") (pinfunction "VCC_VCC") (pintype "power_in"))
      (node (ref "D315") (pin "VCC") (pinfunction "VCC_VCC") (pintype "power_in"))
      (node (ref "D316") (pin "VCC") (pinfunction "VCC_VCC") (pintype "power_in"))
      (node (ref "D317") (pin "VCC") (pinfunction "VCC_VCC") (pintype "power_in"))
      (node (ref "D318") (pin "VCC") (pinfunction "VCC_VCC") (pintype "power_in"))
      (node (ref "D319") (pin "VCC") (pinfunction "VCC_VCC") (pintype "power_in"))
      (node (ref "D32") (pin "VCC") (pinfunction "VCC_VCC") (pintype "power_in"))
      (node (ref "D320") (pin "VCC") (pinfunction "VCC_VCC") (pintype "power_in"))
      (node (ref "D321") (pin "VCC") (pinfunction "VCC_VCC") (pintype "power_in"))
      (node (ref "D322") (pin "VCC") (pinfunction "VCC_VCC") (pintype "power_in"))
      (node (ref "D323") (pin "VCC") (pinfunction "VCC_VCC") (pintype "power_in"))
      (node (ref "D324") (pin "VCC") (pinfunction "VCC_VCC") (pintype "power_in"))
      (node (ref "D325") (pin "VCC") (pinfunction "VCC_VCC") (pintype "power_in"))
      (node (ref "D326") (pin "VCC") (pinfunction "VCC_VCC") (pintype "power_in"))
      (node (ref "D327") (pin "VCC") (pinfunction "VCC_VCC") (pintype "power_in"))
      (node (ref "D328") (pin "VCC") (pinfunction "VCC_VCC") (pintype "power_in"))
      (node (ref "D329") (pin "VCC") (pinfunction "VCC_VCC") (pintype "power_in"))
      (node (ref "D33") (pin "VCC") (pinfunction "VCC_VCC") (pintype "power_in"))
      (node (ref "D330") (pin "VCC") (pinfunction "VCC_VCC") (pintype "power_in"))
      (node (ref "D331") (pin "VCC") (pinfunction "VCC_VCC") (pintype "power_in"))
      (node (ref "D332") (pin "VCC") (pinfunction "VCC_VCC") (pintype "power_in"))
      (node (ref "D333") (pin "VCC") (pinfunction "VCC_VCC") (pintype "power_in"))
      (node (ref "D334") (pin "VCC") (pinfunction "VCC_VCC") (pintype "power_in"))
      (node (ref "D335") (pin "VCC") (pinfunction "VCC_VCC") (pintype "power_in"))
      (node (ref "D336") (pin "VCC") (pinfunction "VCC_VCC") (pintype "power_in"))
      (node (ref "D337") (pin "VCC") (pinfunction "VCC_VCC") (pintype "power_in"))
      (node (ref "D338") (pin "VCC") (pinfunction "VCC_VCC") (pintype "power_in"))
      (node (ref "D339") (pin "VCC") (pinfunction "VCC_VCC") (pintype "power_in"))
      (node (ref "D34") (pin "VCC") (pinfunction "VCC_VCC") (pintype "power_in"))
      (node (ref "D340") (pin "VCC") (pinfunction "VCC_VCC") (pintype "power_in"))
      (node (ref "D341") (pin "VCC") (pinfunction "VCC_VCC") (pintype "power_in"))
      (node (ref "D342") (pin "VCC") (pinfunction "VCC_VCC") (pintype "power_in"))
      (node (ref "D343") (pin "VCC") (pinfunction "VCC_VCC") (pintype "power_in"))
      (node (ref "D344") (pin "VCC") (pinfunction "VCC_VCC") (pintype "power_in"))
      (node (ref "D345") (pin "VCC") (pinfunction "VCC_VCC") (pintype "power_in"))
      (node (ref "D346") (pin "VCC") (pinfunction "VCC_VCC") (pintype "power_in"))
      (node (ref "D347") (pin "VCC") (pinfunction "VCC_VCC") (pintype "power_in"))
      (node (ref "D348") (pin "VCC") (pinfunction "VCC_VCC") (pintype "power_in"))
      (node (ref "D349") (pin "VCC") (pinfunction "VCC_VCC") (pintype "power_in"))
      (node (ref "D35") (pin "VCC") (pinfunction "VCC_VCC") (pintype "power_in"))
      (node (ref "D350") (pin "VCC") (pinfunction "VCC_VCC") (pintype "power_in"))
      (node (ref "D351") (pin "VCC") (pinfunction "VCC_VCC") (pintype "power_in"))
      (node (ref "D352") (pin "VCC") (pinfunction "VCC_VCC") (pintype "power_in"))
      (node (ref "D353") (pin "VCC") (pinfunction "VCC_VCC") (pintype "power_in"))
      (node (ref "D354") (pin "VCC") (pinfunction "VCC_VCC") (pintype "power_in"))
      (node (ref "D355") (pin "VCC") (pinfunction "VCC_VCC") (pintype "power_in"))
      (node (ref "D356") (pin "VCC") (pinfunction "VCC_VCC") (pintype "power_in"))
      (node (ref "D357") (pin "VCC") (pinfunction "VCC_VCC") (pintype "power_in"))
      (node (ref "D358") (pin "VCC") (pinfunction "VCC_VCC") (pintype "power_in"))
      (node (ref "D359") (pin "VCC") (pinfunction "VCC_VCC") (pintype "power_in"))
      (node (ref "D36") (pin "VCC") (pinfunction "VCC_VCC") (pintype "power_in"))
      (node (ref "D360") (pin "VCC") (pinfunction "VCC_VCC") (pintype "power_in"))
      (node (ref "D361") (pin "VCC") (pinfunction "VCC_VCC") (pintype "power_in"))
      (node (ref "D362") (pin "VCC") (pinfunction "VCC_VCC") (pintype "power_in"))
      (node (ref "D363") (pin "VCC") (pinfunction "VCC_VCC") (pintype "power_in"))
      (node (ref "D364") (pin "VCC") (pinfunction "VCC_VCC") (pintype "power_in"))
      (node (ref "D365") (pin "VCC") (pinfunction "VCC_VCC") (pintype "power_in"))
      (node (ref "D366") (pin "VCC") (pinfunction "VCC_VCC") (pintype "power_in"))
      (node (ref "D367") (pin "VCC") (pinfunction "VCC_VCC") (pintype "power_in"))
      (node (ref "D368") (pin "VCC") (pinfunction "VCC_VCC") (pintype "power_in"))
      (node (ref "D369") (pin "VCC") (pinfunction "VCC_VCC") (pintype "power_in"))
      (node (ref "D37") (pin "VCC") (pinfunction "VCC_VCC") (pintype "power_in"))
      (node (ref "D370") (pin "VCC") (pinfunction "VCC_VCC") (pintype "power_in"))
      (node (ref "D371") (pin "VCC") (pinfunction "VCC_VCC") (pintype "power_in"))
      (node (ref "D372") (pin "VCC") (pinfunction "VCC_VCC") (pintype "power_in"))
      (node (ref "D373") (pin "VCC") (pinfunction "VCC_VCC") (pintype "power_in"))
      (node (ref "D374") (pin "VCC") (pinfunction "VCC_VCC") (pintype "power_in"))
      (node (ref "D375") (pin "VCC") (pinfunction "VCC_VCC") (pintype "power_in"))
      (node (ref "D376") (pin "VCC") (pinfunction "VCC_VCC") (pintype "power_in"))
      (node (ref "D377") (pin "VCC") (pinfunction "VCC_VCC") (pintype "power_in"))
      (node (ref "D378") (pin "VCC") (pinfunction "VCC_VCC") (pintype "power_in"))
      (node (ref "D379") (pin "VCC") (pinfunction "VCC_VCC") (pintype "power_in"))
      (node (ref "D38") (pin "VCC") (pinfunction "VCC_VCC") (pintype "power_in"))
      (node (ref "D380") (pin "VCC") (pinfunction "VCC_VCC") (pintype "power_in"))
      (node (ref "D381") (pin "VCC") (pinfunction "VCC_VCC") (pintype "power_in"))
      (node (ref "D382") (pin "VCC") (pinfunction "VCC_VCC") (pintype "power_in"))
      (node (ref "D383") (pin "VCC") (pinfunction "VCC_VCC") (pintype "power_in"))
      (node (ref "D384") (pin "VCC") (pinfunction "VCC_VCC") (pintype "power_in"))
      (node (ref "D385") (pin "VCC") (pinfunction "VCC_VCC") (pintype "power_in"))
      (node (ref "D386") (pin "VCC") (pinfunction "VCC_VCC") (pintype "power_in"))
      (node (ref "D387") (pin "VCC") (pinfunction "VCC_VCC") (pintype "power_in"))
      (node (ref "D388") (pin "VCC") (pinfunction "VCC_VCC") (pintype "power_in"))
      (node (ref "D389") (pin "VCC") (pinfunction "VCC_VCC") (pintype "power_in"))
      (node (ref "D39") (pin "VCC") (pinfunction "VCC_VCC") (pintype "power_in"))
      (node (ref "D390") (pin "VCC") (pinfunction "VCC_VCC") (pintype "power_in"))
      (node (ref "D391") (pin "VCC") (pinfunction "VCC_VCC") (pintype "power_in"))
      (node (ref "D392") (pin "VCC") (pinfunction "VCC_VCC") (pintype "power_in"))
      (node (ref "D393") (pin "VCC") (pinfunction "VCC_VCC") (pintype "power_in"))
      (node (ref "D394") (pin "VCC") (pinfunction "VCC_VCC") (pintype "power_in"))
      (node (ref "D395") (pin "VCC") (pinfunction "VCC_VCC") (pintype "power_in"))
      (node (ref "D396") (pin "VCC") (pinfunction "VCC_VCC") (pintype "power_in"))
      (node (ref "D397") (pin "VCC") (pinfunction "VCC_VCC") (pintype "power_in"))
      (node (ref "D398") (pin "VCC") (pinfunction "VCC_VCC") (pintype "power_in"))
      (node (ref "D399") (pin "VCC") (pinfunction "VCC_VCC") (pintype "power_in"))
      (node (ref "D4") (pin "VCC") (pinfunction "VCC_VCC") (pintype "power_in"))
      (node (ref "D40") (pin "VCC") (pinfunction "VCC_VCC") (pintype "power_in"))
      (node (ref "D400") (pin "VCC") (pinfunction "VCC_VCC") (pintype "power_in"))
      (node (ref "D401") (pin "VCC") (pinfunction "VCC_VCC") (pintype "power_in"))
      (node (ref "D402") (pin "VCC") (pinfunction "VCC_VCC") (pintype "power_in"))
      (node (ref "D403") (pin "VCC") (pinfunction "VCC_VCC") (pintype "power_in"))
      (node (ref "D404") (pin "VCC") (pinfunction "VCC_VCC") (pintype "power_in"))
      (node (ref "D405") (pin "VCC") (pinfunction "VCC_VCC") (pintype "power_in"))
      (node (ref "D41") (pin "VCC") (pinfunction "VCC_VCC") (pintype "power_in"))
      (node (ref "D42") (pin "VCC") (pinfunction "VCC_VCC") (pintype "power_in"))
      (node (ref "D43") (pin "VCC") (pinfunction "VCC_VCC") (pintype "power_in"))
      (node (ref "D44") (pin "VCC") (pinfunction "VCC_VCC") (pintype "power_in"))
      (node (ref "D45") (pin "VCC") (pinfunction "VCC_VCC") (pintype "power_in"))
      (node (ref "D46") (pin "VCC") (pinfunction "VCC_VCC") (pintype "power_in"))
      (node (ref "D47") (pin "VCC") (pinfunction "VCC_VCC") (pintype "power_in"))
      (node (ref "D48") (pin "VCC") (pinfunction "VCC_VCC") (pintype "power_in"))
      (node (ref "D49") (pin "VCC") (pinfunction "VCC_VCC") (pintype "power_in"))
      (node (ref "D5") (pin "VCC") (pinfunction "VCC_VCC") (pintype "power_in"))
      (node (ref "D50") (pin "VCC") (pinfunction "VCC_VCC") (pintype "power_in"))
      (node (ref "D51") (pin "VCC") (pinfunction "VCC_VCC") (pintype "power_in"))
      (node (ref "D52") (pin "VCC") (pinfunction "VCC_VCC") (pintype "power_in"))
      (node (ref "D53") (pin "VCC") (pinfunction "VCC_VCC") (pintype "power_in"))
      (node (ref "D54") (pin "VCC") (pinfunction "VCC_VCC") (pintype "power_in"))
      (node (ref "D55") (pin "VCC") (pinfunction "VCC_VCC") (pintype "power_in"))
      (node (ref "D56") (pin "VCC") (pinfunction "VCC_VCC") (pintype "power_in"))
      (node (ref "D57") (pin "VCC") (pinfunction "VCC_VCC") (pintype "power_in"))
      (node (ref "D58") (pin "VCC") (pinfunction "VCC_VCC") (pintype "power_in"))
      (node (ref "D59") (pin "VCC") (pinfunction "VCC_VCC") (pintype "power_in"))
      (node (ref "D6") (pin "VCC") (pinfunction "VCC_VCC") (pintype "power_in"))
      (node (ref "D60") (pin "VCC") (pinfunction "VCC_VCC") (pintype "power_in"))
      (node (ref "D61") (pin "VCC") (pinfunction "VCC_VCC") (pintype "power_in"))
      (node (ref "D62") (pin "VCC") (pinfunction "VCC_VCC") (pintype "power_in"))
      (node (ref "D63") (pin "VCC") (pinfunction "VCC_VCC") (pintype "power_in"))
      (node (ref "D64") (pin "VCC") (pinfunction "VCC_VCC") (pintype "power_in"))
      (node (ref "D65") (pin "VCC") (pinfunction "VCC_VCC") (pintype "power_in"))
      (node (ref "D66") (pin "VCC") (pinfunction "VCC_VCC") (pintype "power_in"))
      (node (ref "D67") (pin "VCC") (pinfunction "VCC_VCC") (pintype "power_in"))
      (node (ref "D68") (pin "VCC") (pinfunction "VCC_VCC") (pintype "power_in"))
      (node (ref "D69") (pin "VCC") (pinfunction "VCC_VCC") (pintype "power_in"))
      (node (ref "D7") (pin "VCC") (pinfunction "VCC_VCC") (pintype "power_in"))
      (node (ref "D70") (pin "VCC") (pinfunction "VCC_VCC") (pintype "power_in"))
      (node (ref "D71") (pin "VCC") (pinfunction "VCC_VCC") (pintype "power_in"))
      (node (ref "D72") (pin "VCC") (pinfunction "VCC_VCC") (pintype "power_in"))
      (node (ref "D73") (pin "VCC") (pinfunction "VCC_VCC") (pintype "power_in"))
      (node (ref "D74") (pin "VCC") (pinfunction "VCC_VCC") (pintype "power_in"))
      (node (ref "D75") (pin "VCC") (pinfunction "VCC_VCC") (pintype "power_in"))
      (node (ref "D76") (pin "VCC") (pinfunction "VCC_VCC") (pintype "power_in"))
      (node (ref "D77") (pin "VCC") (pinfunction "VCC_VCC") (pintype "power_in"))
      (node (ref "D78") (pin "VCC") (pinfunction "VCC_VCC") (pintype "power_in"))
      (node (ref "D79") (pin "VCC") (pinfunction "VCC_VCC") (pintype "power_in"))
      (node (ref "D8") (pin "VCC") (pinfunction "VCC_VCC") (pintype "power_in"))
      (node (ref "D80") (pin "VCC") (pinfunction "VCC_VCC") (pintype "power_in"))
      (node (ref "D81") (pin "VCC") (pinfunction "VCC_VCC") (pintype "power_in"))
      (node (ref "D82") (pin "VCC") (pinfunction "VCC_VCC") (pintype "power_in"))
      (node (ref "D83") (pin "VCC") (pinfunction "VCC_VCC") (pintype "power_in"))
      (node (ref "D84") (pin "VCC") (pinfunction "VCC_VCC") (pintype "power_in"))
      (node (ref "D85") (pin "VCC") (pinfunction "VCC_VCC") (pintype "power_in"))
      (node (ref "D86") (pin "VCC") (pinfunction "VCC_VCC") (pintype "power_in"))
      (node (ref "D87") (pin "VCC") (pinfunction "VCC_VCC") (pintype "power_in"))
      (node (ref "D88") (pin "VCC") (pinfunction "VCC_VCC") (pintype "power_in"))
      (node (ref "D89") (pin "VCC") (pinfunction "VCC_VCC") (pintype "power_in"))
      (node (ref "D9") (pin "VCC") (pinfunction "VCC_VCC") (pintype "power_in"))
      (node (ref "D90") (pin "VCC") (pinfunction "VCC_VCC") (pintype "power_in"))
      (node (ref "D91") (pin "VCC") (pinfunction "VCC_VCC") (pintype "power_in"))
      (node (ref "D92") (pin "VCC") (pinfunction "VCC_VCC") (pintype "power_in"))
      (node (ref "D93") (pin "VCC") (pinfunction "VCC_VCC") (pintype "power_in"))
      (node (ref "D94") (pin "VCC") (pinfunction "VCC_VCC") (pintype "power_in"))
      (node (ref "D95") (pin "VCC") (pinfunction "VCC_VCC") (pintype "power_in"))
      (node (ref "D96") (pin "VCC") (pinfunction "VCC_VCC") (pintype "power_in"))
      (node (ref "D97") (pin "VCC") (pinfunction "VCC_VCC") (pintype "power_in"))
      (node (ref "D98") (pin "VCC") (pinfunction "VCC_VCC") (pintype "power_in"))
      (node (ref "D99") (pin "VCC") (pinfunction "VCC_VCC") (pintype "power_in"))
      (node (ref "JP1") (pin "1") (pinfunction "1_1") (pintype "passive"))
      (node (ref "JP1") (pin "2") (pinfunction "2_2") (pintype "passive"))
      (node (ref "JP1") (pin "3") (pinfunction "3_3") (pintype "passive"))
      (node (ref "JP2") (pin "1") (pinfunction "1_1") (pintype "passive"))
      (node (ref "JP2") (pin "2") (pinfunction "2_2") (pintype "passive"))
      (node (ref "JP2") (pin "3") (pinfunction "3_3") (pintype "passive"))
      (node (ref "Z1") (pin "1") (pinfunction "1_1") (pintype "passive"))
    )
    (net (code "409") (name "unconnected-(D1-PadDO)") (class "Default")
      (node (ref "D1") (pin "DO") (pinfunction "DO_DO") (pintype "output"))
    )
    (net (code "410") (name "unconnected-(JP2-Pad4)") (class "Default")
      (node (ref "JP2") (pin "4") (pinfunction "4_4") (pintype "passive"))
    )
  )
)
